# ACB_Jr.net
KiCad netlist of a schematic drawn in EAGLE
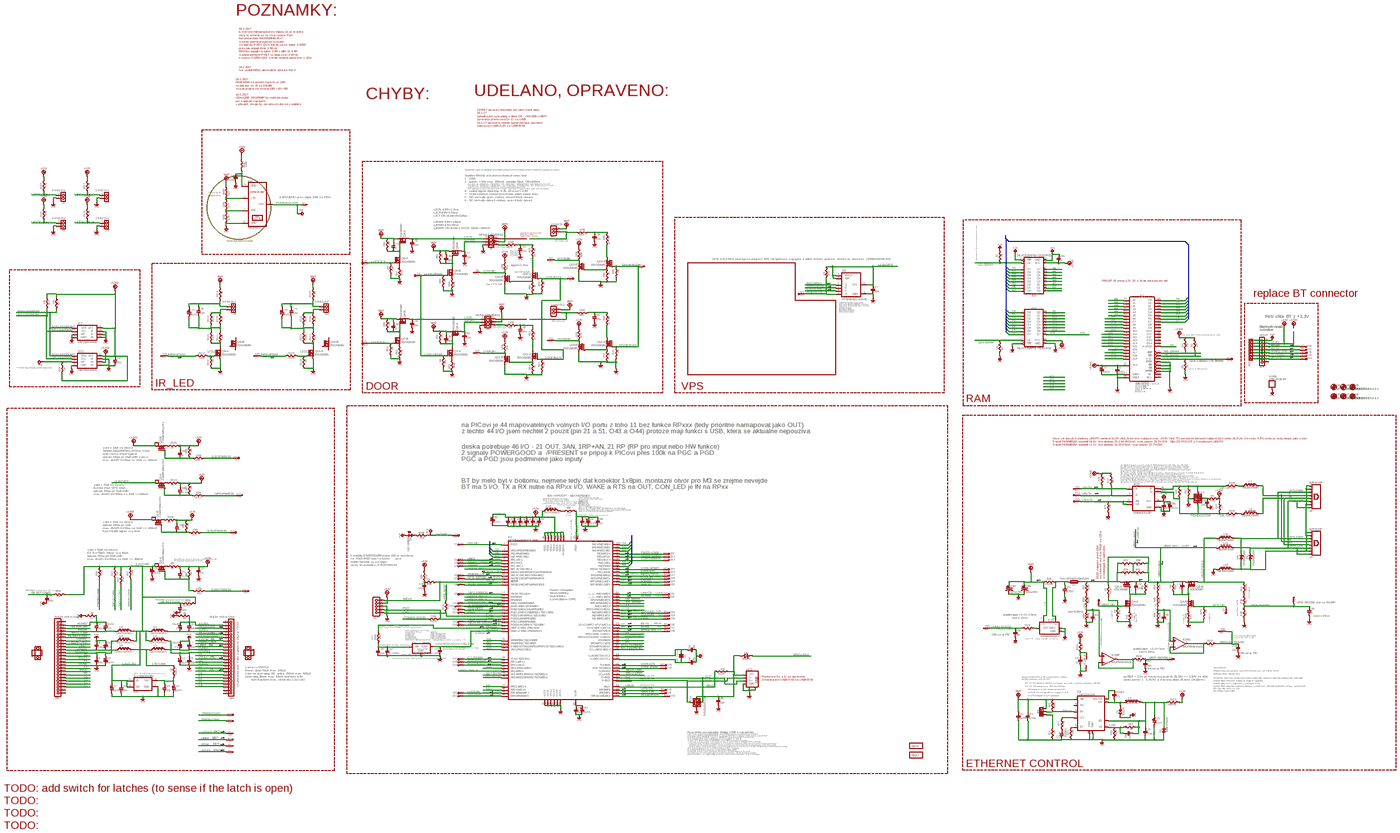
[diagram p0: schematic, sheet 1, overview]
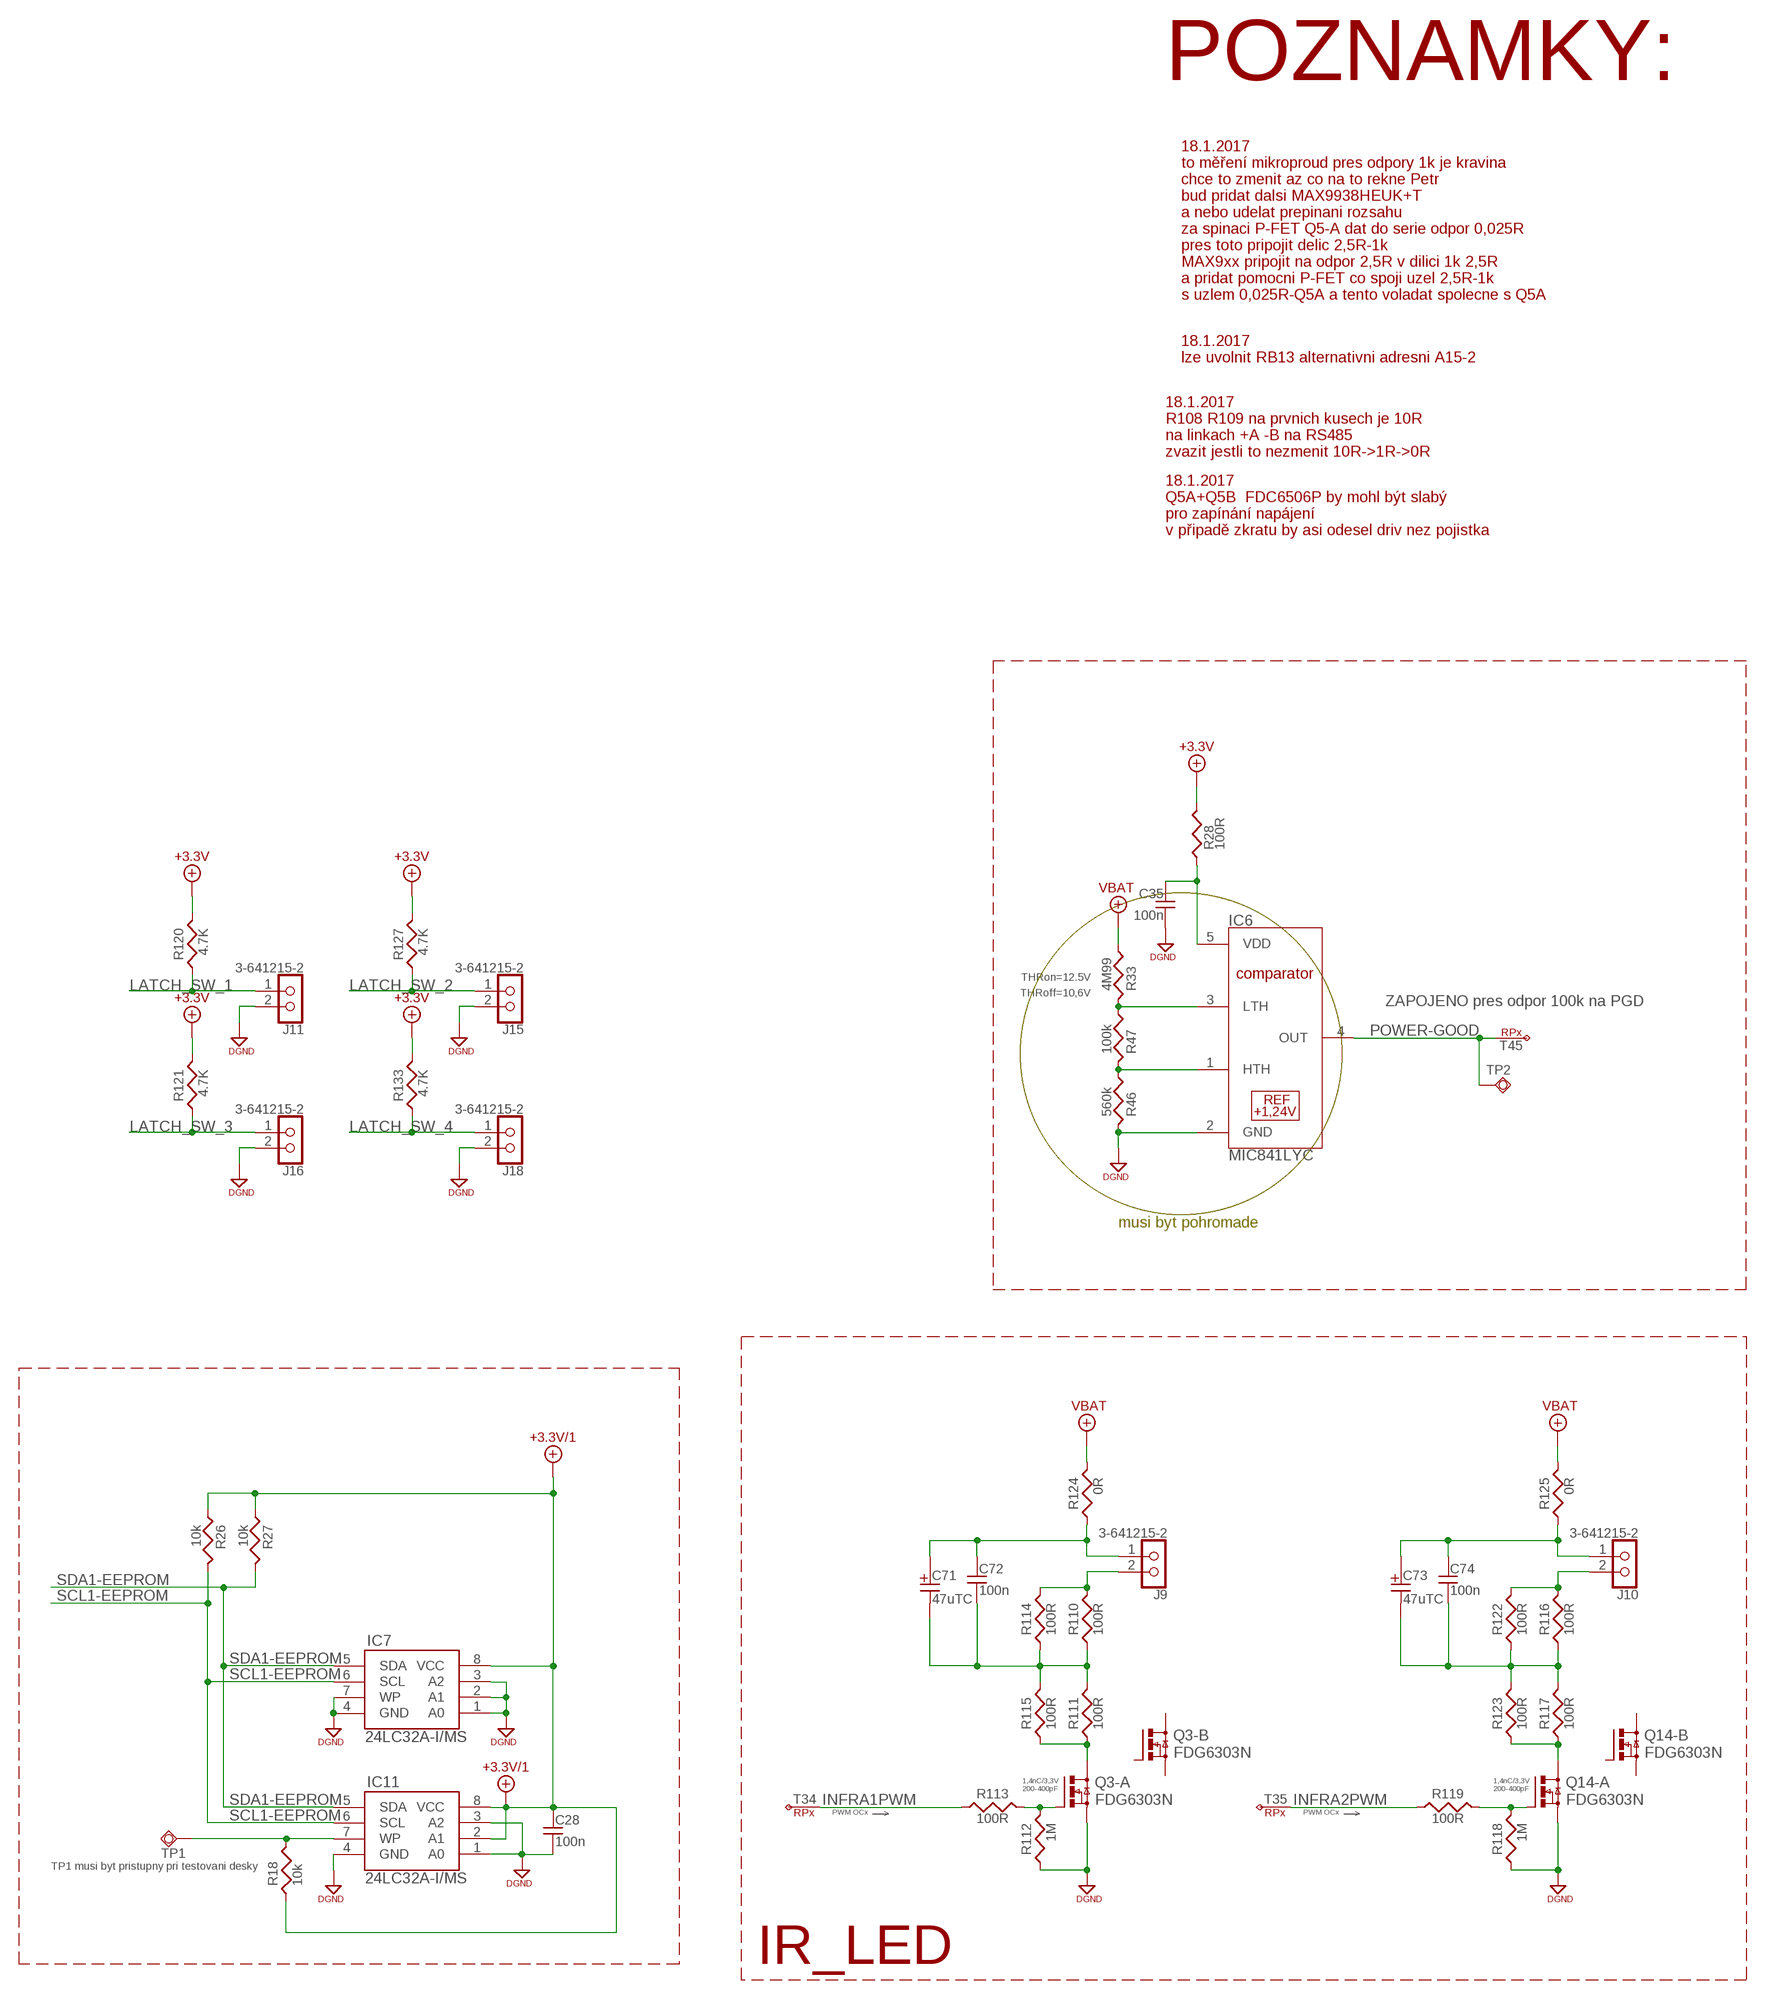
[diagram p1: schematic, sheet 1, part 1 of 5]
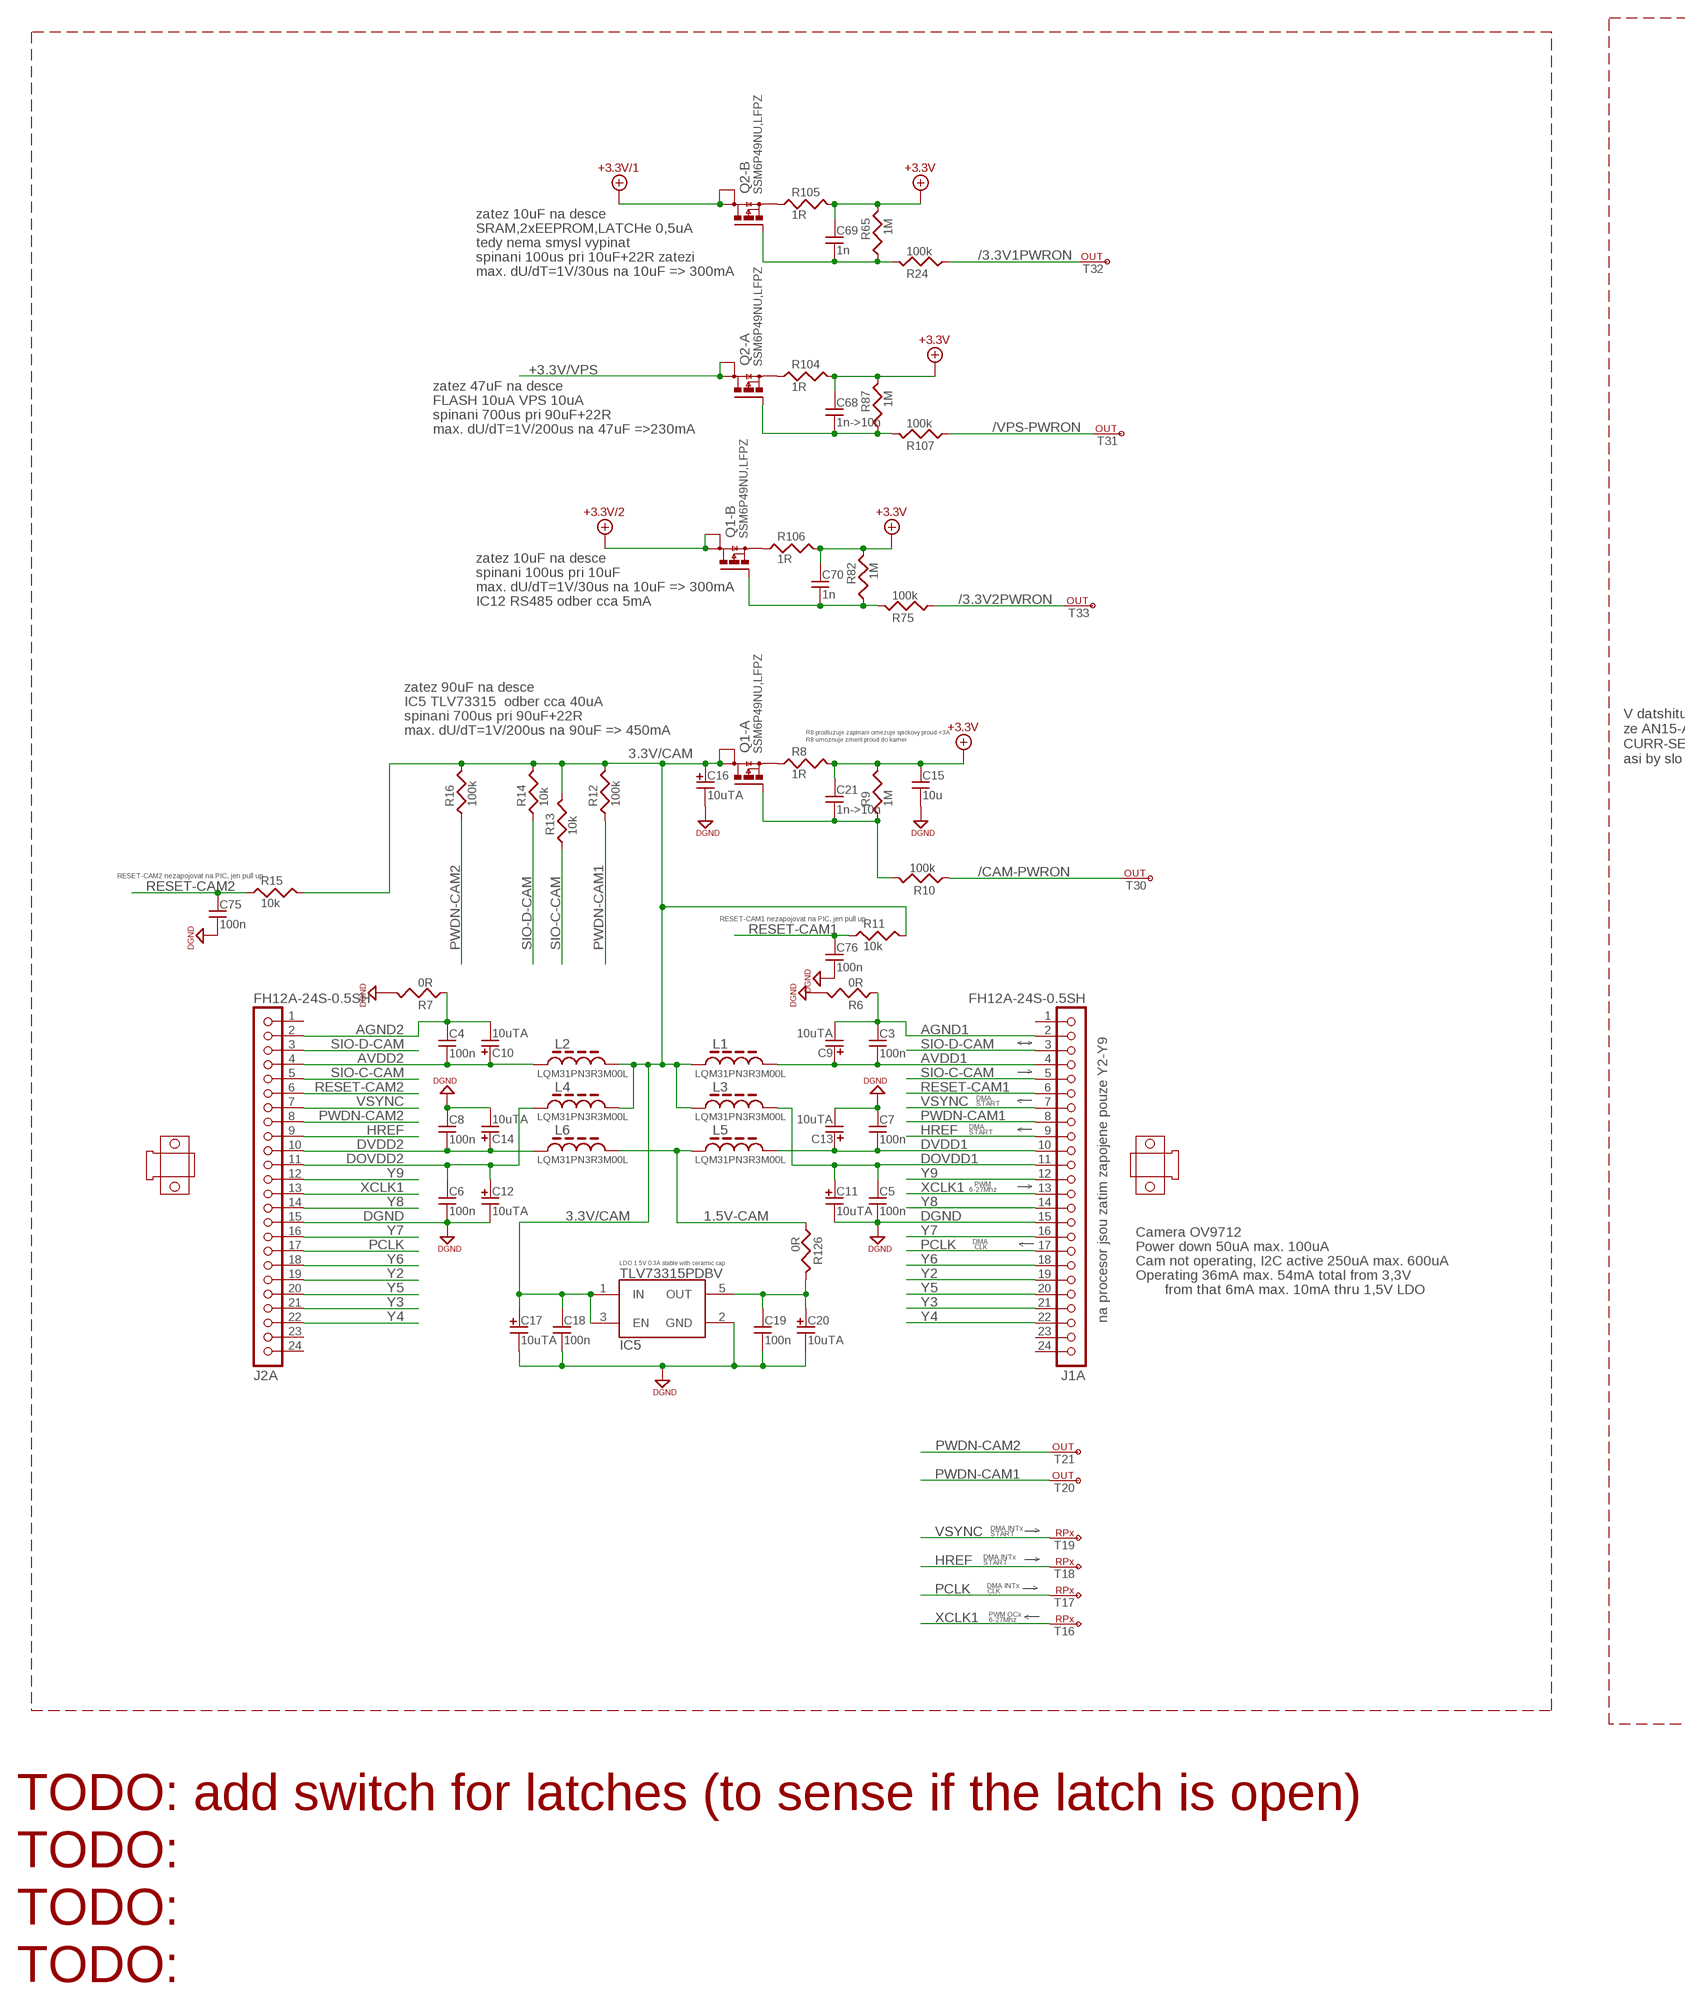
[diagram p2: schematic, sheet 1, part 2 of 5]
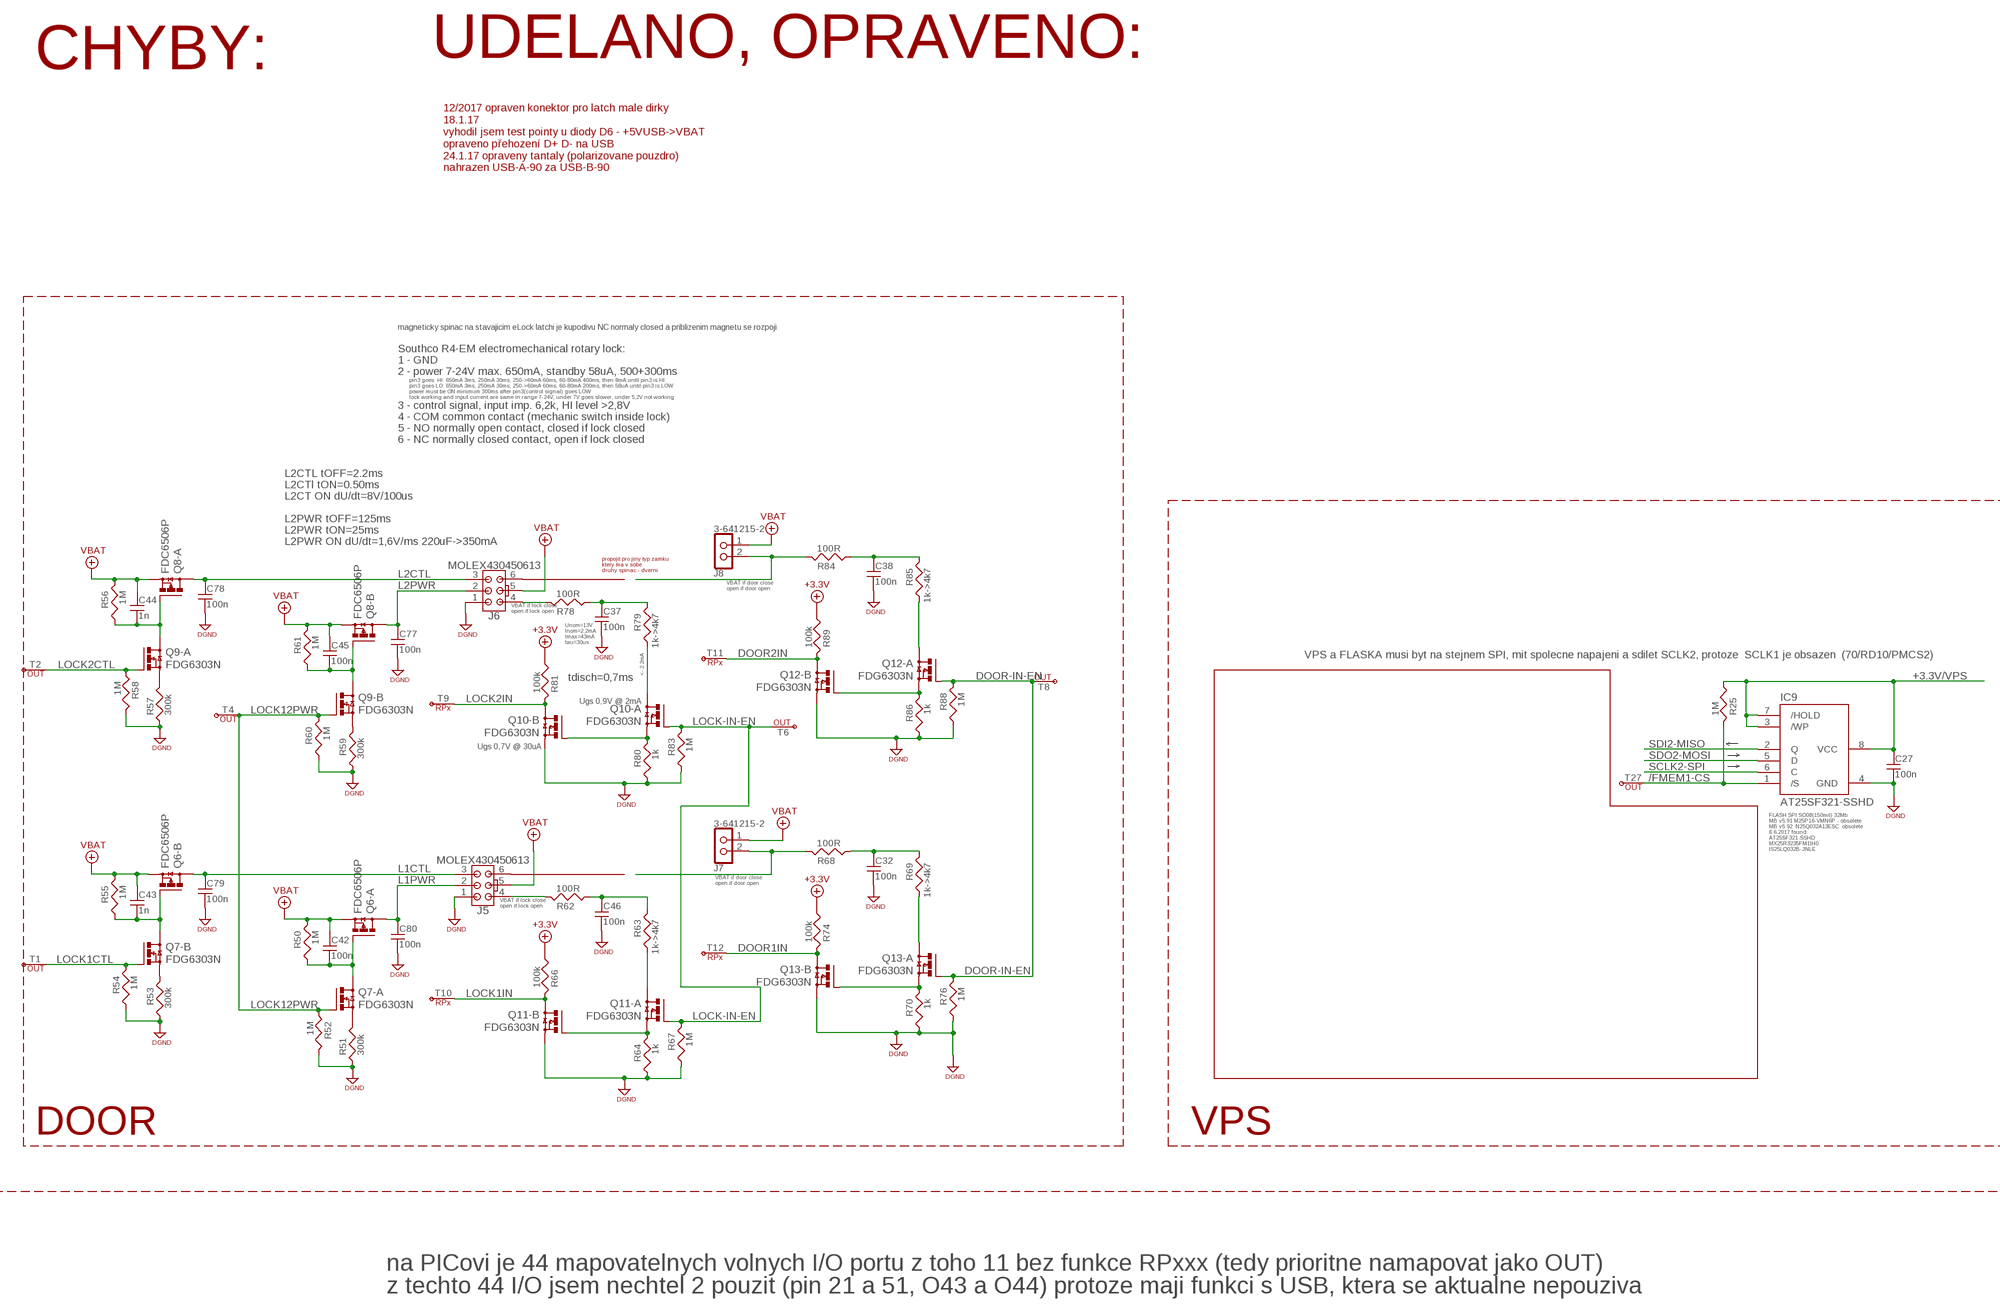
[diagram p3: schematic, sheet 1, part 3 of 5]
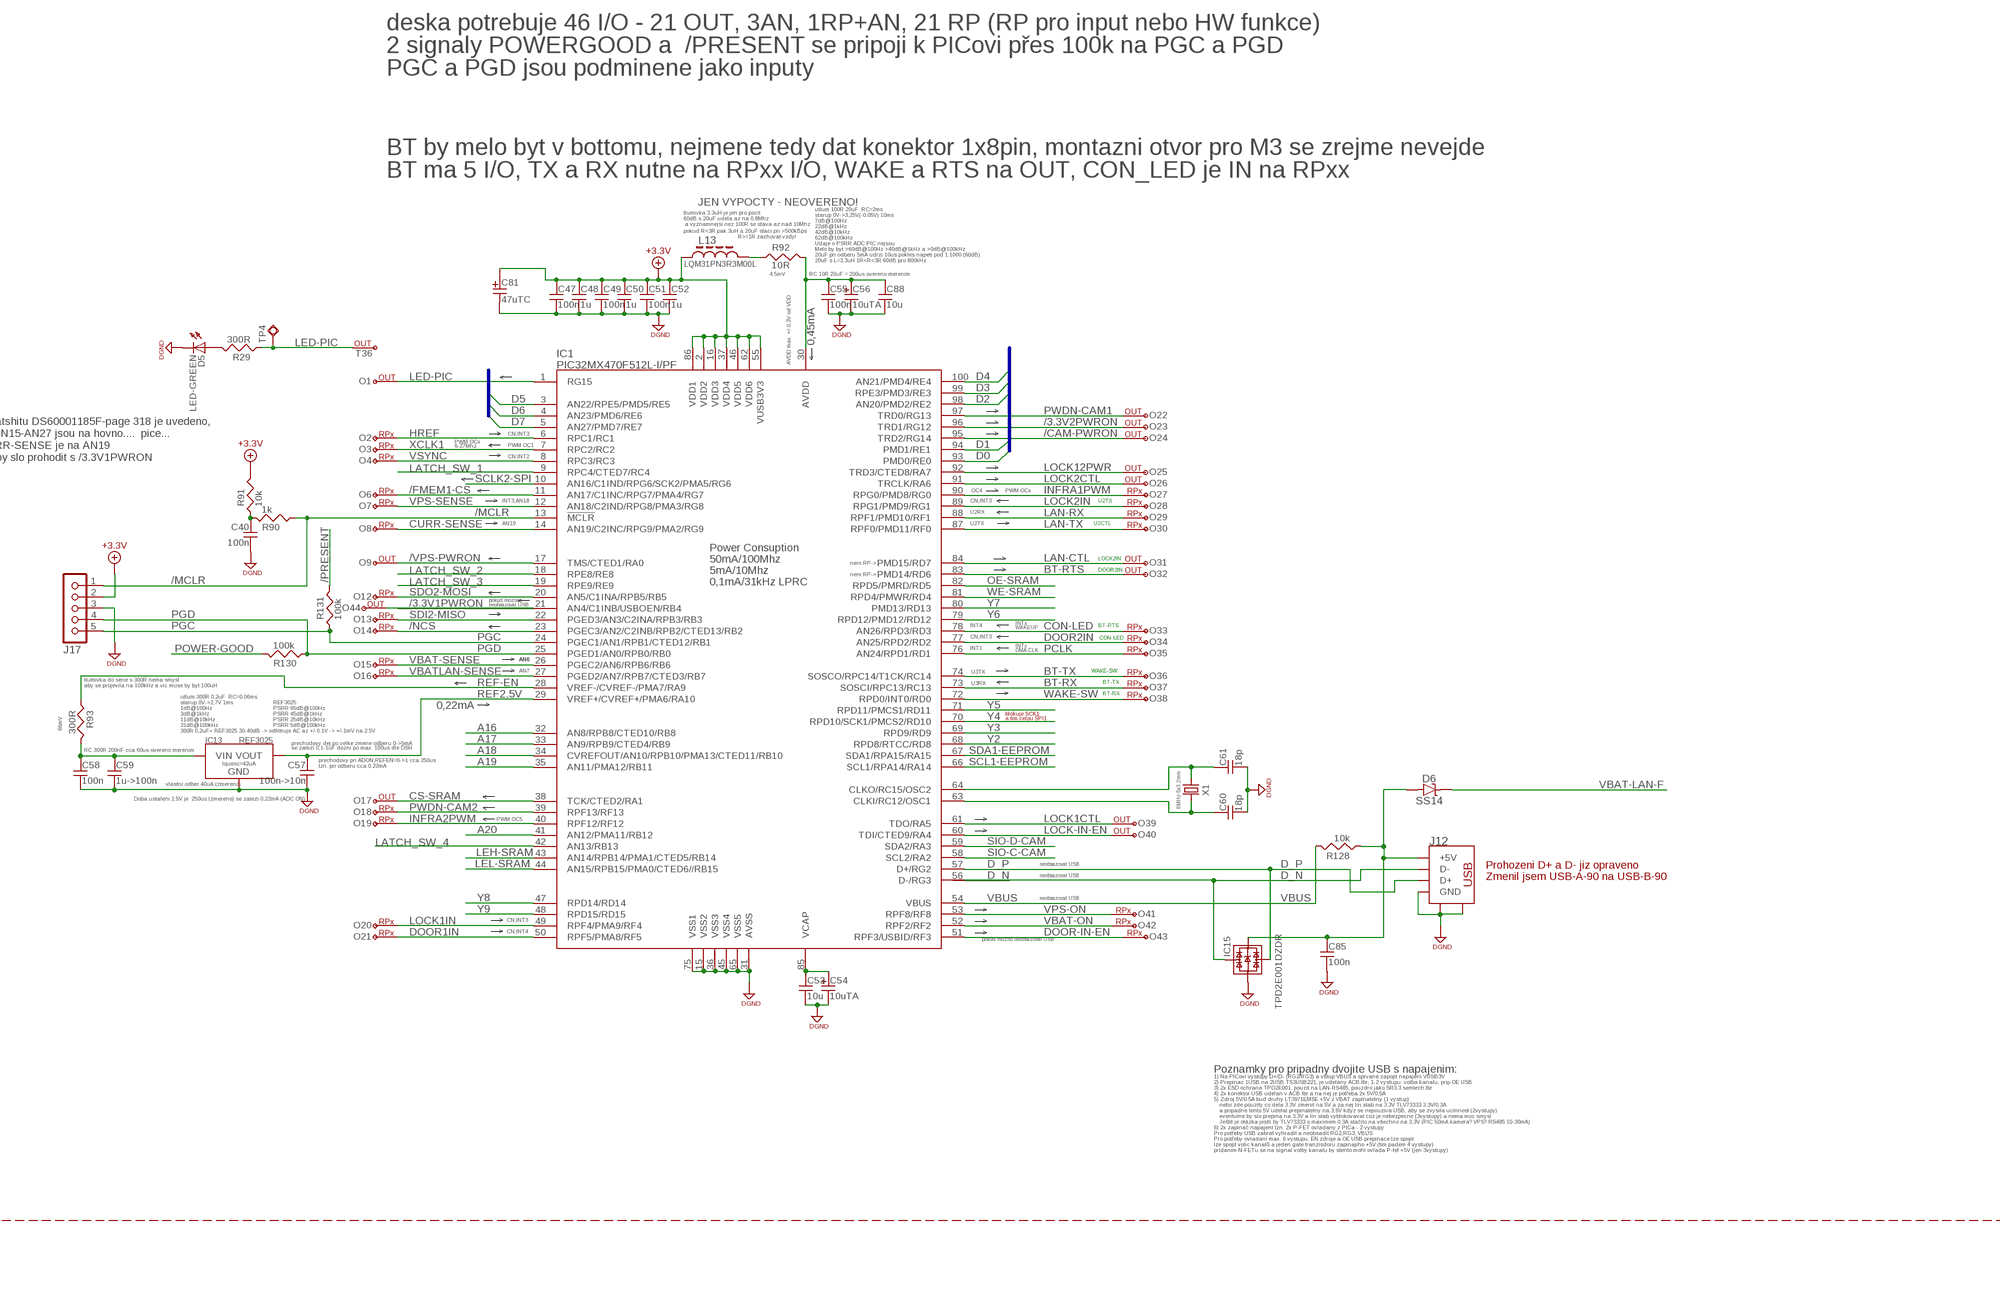
[diagram p4: schematic, sheet 1, part 4 of 5]
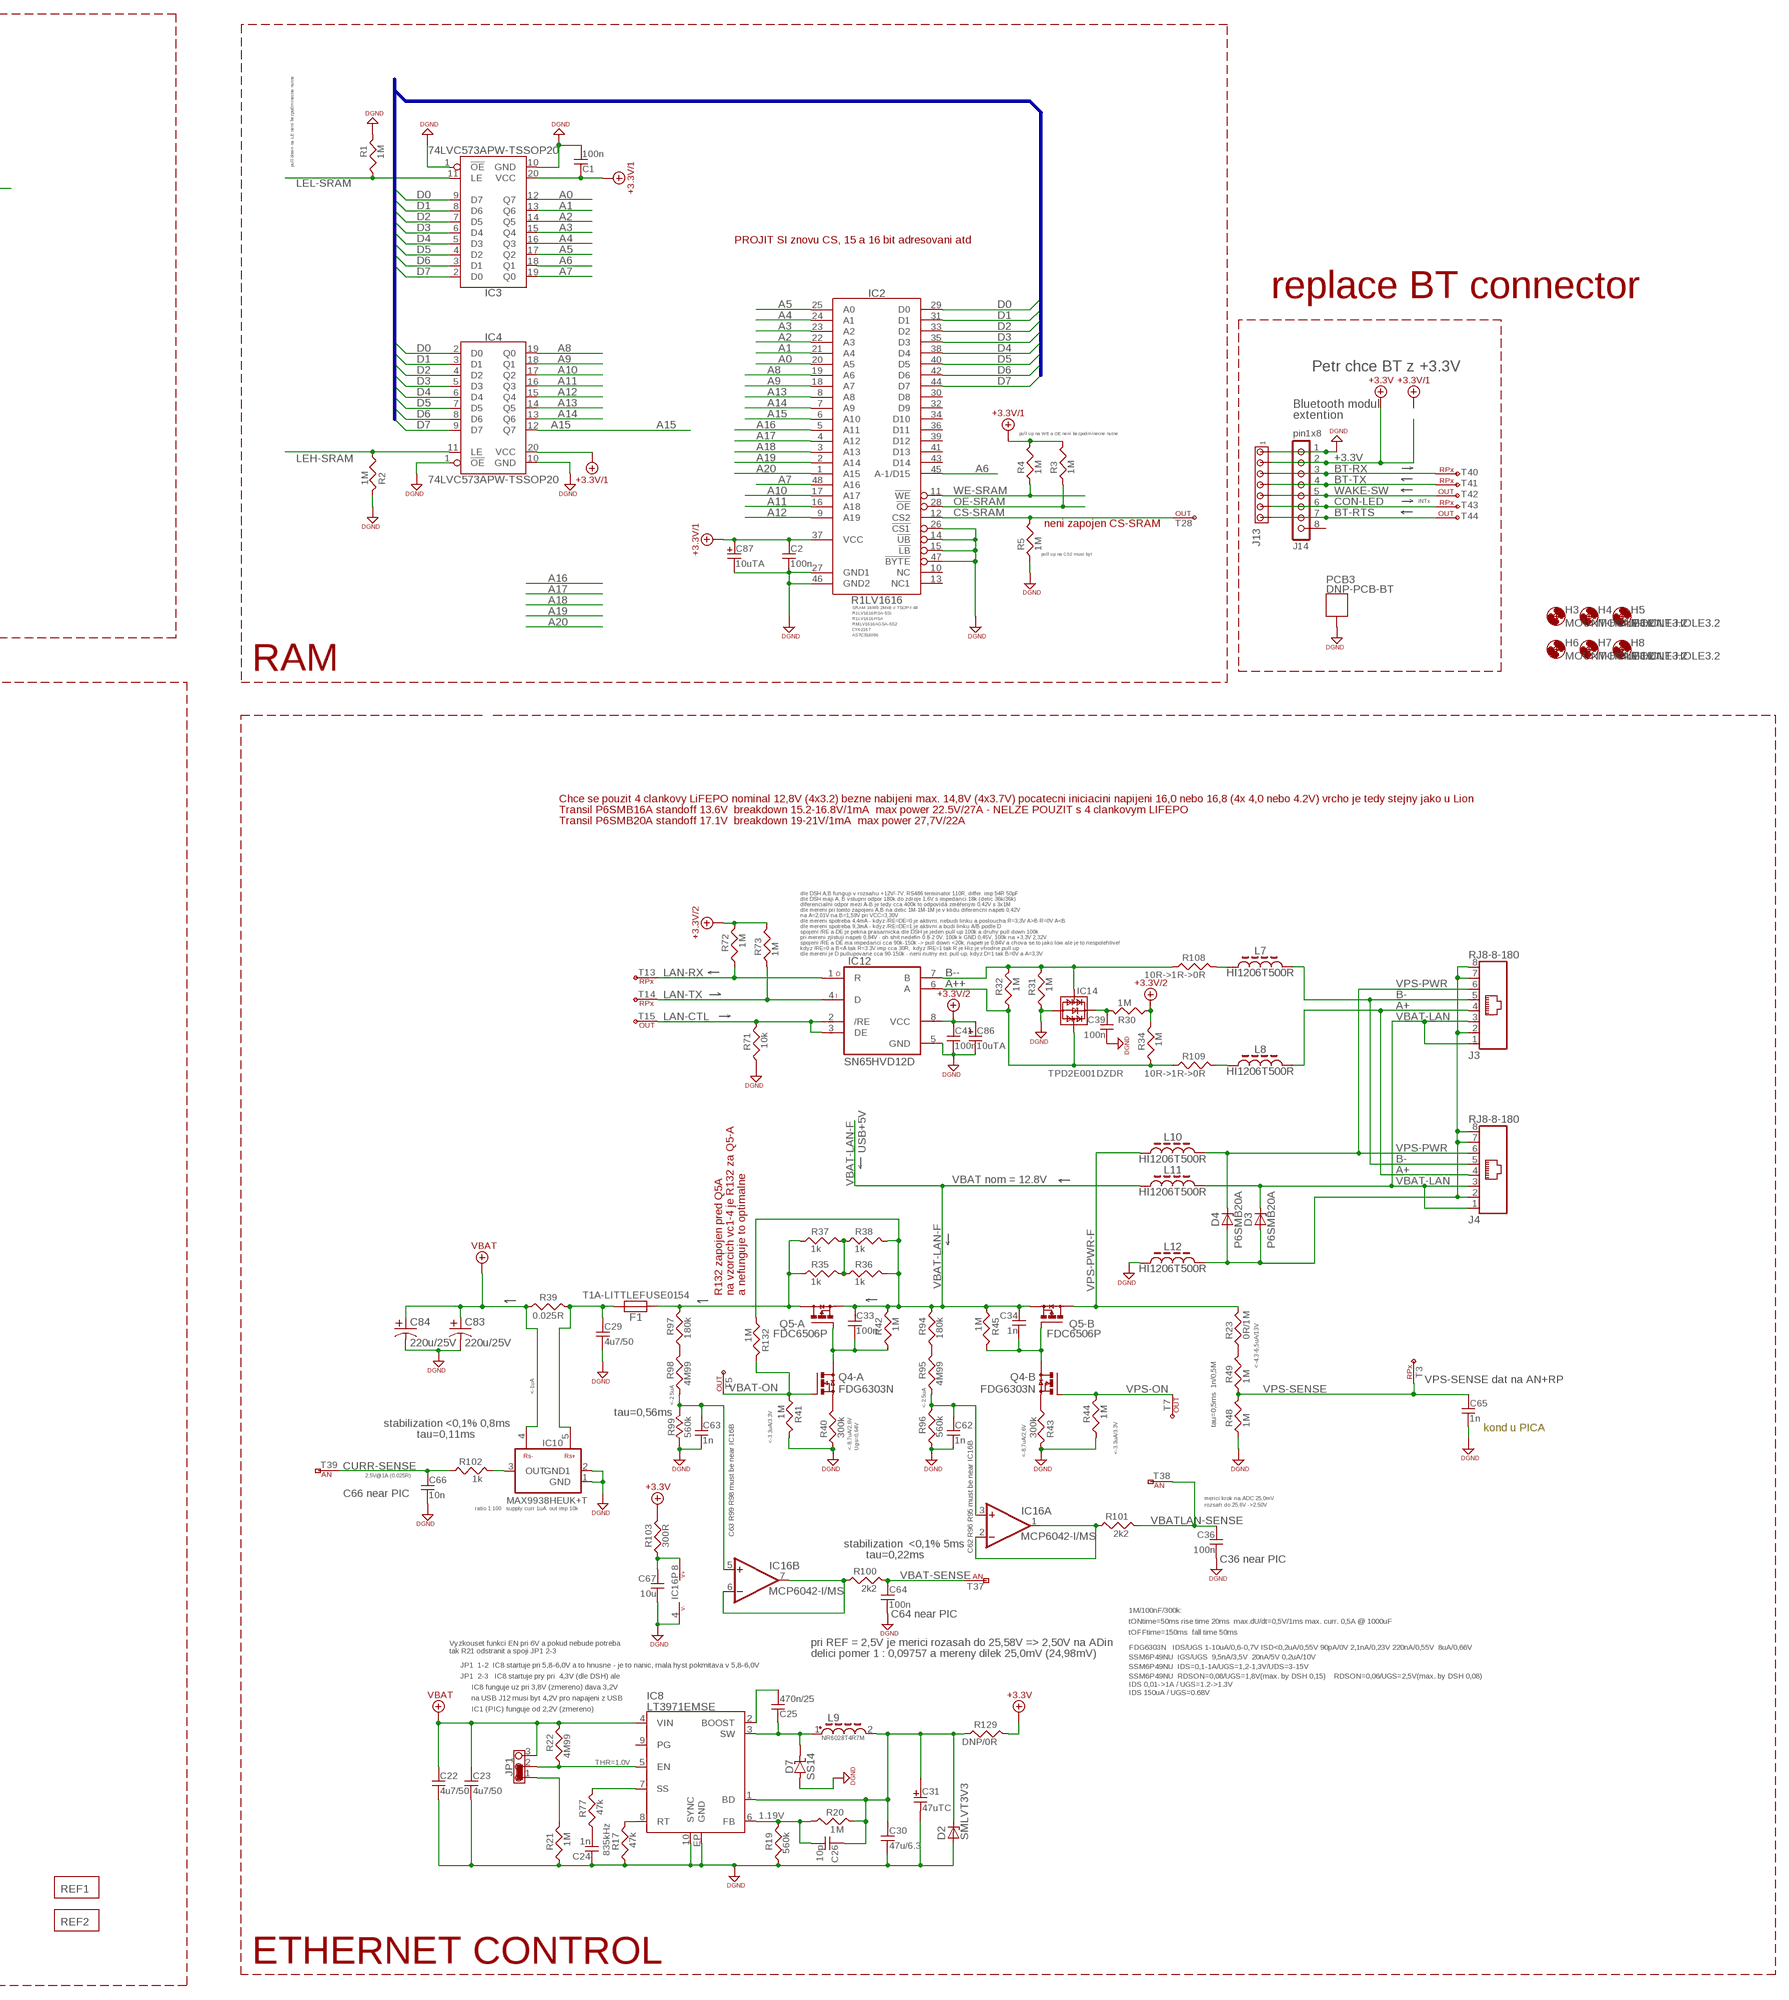
[diagram p5: schematic, sheet 1, part 5 of 5]

(export (version "E")
  (design (tool "Eeschema 10.0.6"))
  (components
    (comp (ref "C1")
      (value "100n")
      (footprint "eagle-import:0603")
      (libsource (lib "eagle-import") (part "C-0603"))
    )
    (comp (ref "C2")
      (value "100n")
      (footprint "eagle-import:0603")
      (libsource (lib "eagle-import") (part "DISCRETE_211_C-0603"))
    )
    (comp (ref "C3")
      (value "100n")
      (footprint "eagle-import:0603")
      (libsource (lib "eagle-import") (part "DISCRETE_211_C-0603"))
    )
    (comp (ref "C4")
      (value "100n")
      (footprint "eagle-import:0603")
      (libsource (lib "eagle-import") (part "DISCRETE_211_C-0603"))
    )
    (comp (ref "C5")
      (value "100n")
      (footprint "eagle-import:0603")
      (libsource (lib "eagle-import") (part "DISCRETE_211_C-0603"))
    )
    (comp (ref "C6")
      (value "100n")
      (footprint "eagle-import:0603")
      (libsource (lib "eagle-import") (part "DISCRETE_211_C-0603"))
    )
    (comp (ref "C7")
      (value "100n")
      (footprint "eagle-import:0603")
      (libsource (lib "eagle-import") (part "DISCRETE_211_C-0603"))
    )
    (comp (ref "C8")
      (value "100n")
      (footprint "eagle-import:0603")
      (libsource (lib "eagle-import") (part "DISCRETE_211_C-0603"))
    )
    (comp (ref "C9")
      (value "10uTA")
      (footprint "eagle-import:1206-POL-C")
      (libsource (lib "eagle-import") (part "CT-1206"))
    )
    (comp (ref "C10")
      (value "10uTA")
      (footprint "eagle-import:1206-POL-C")
      (libsource (lib "eagle-import") (part "CT-1206"))
    )
    (comp (ref "C11")
      (value "10uTA")
      (footprint "eagle-import:1206-POL-C")
      (libsource (lib "eagle-import") (part "CT-1206"))
    )
    (comp (ref "C12")
      (value "10uTA")
      (footprint "eagle-import:1206-POL-C")
      (libsource (lib "eagle-import") (part "CT-1206"))
    )
    (comp (ref "C13")
      (value "10uTA")
      (footprint "eagle-import:1206-POL-C")
      (libsource (lib "eagle-import") (part "CT-1206"))
    )
    (comp (ref "C14")
      (value "10uTA")
      (footprint "eagle-import:1206-POL-C")
      (libsource (lib "eagle-import") (part "CT-1206"))
    )
    (comp (ref "C15")
      (value "10u")
      (footprint "eagle-import:0603")
      (libsource (lib "eagle-import") (part "C-0603"))
    )
    (comp (ref "C16")
      (value "10uTA")
      (footprint "eagle-import:1206-POL-C")
      (libsource (lib "eagle-import") (part "CT-1206"))
    )
    (comp (ref "C17")
      (value "10uTA")
      (footprint "eagle-import:1206-POL-C")
      (libsource (lib "eagle-import") (part "CT-1206"))
    )
    (comp (ref "C18")
      (value "100n")
      (footprint "eagle-import:0603")
      (libsource (lib "eagle-import") (part "DISCRETE_211_C-0603"))
    )
    (comp (ref "C19")
      (value "100n")
      (footprint "eagle-import:0603")
      (libsource (lib "eagle-import") (part "DISCRETE_211_C-0603"))
    )
    (comp (ref "C20")
      (value "10uTA")
      (footprint "eagle-import:1206-POL-C")
      (libsource (lib "eagle-import") (part "CT-1206"))
    )
    (comp (ref "C21")
      (value "1n->10n")
      (footprint "eagle-import:0603")
      (libsource (lib "eagle-import") (part "DISCRETE_211_C-0603"))
    )
    (comp (ref "C22")
      (value "4u7/50")
      (footprint "eagle-import:1206")
      (libsource (lib "eagle-import") (part "C-1206"))
    )
    (comp (ref "C23")
      (value "4u7/50")
      (footprint "eagle-import:1206")
      (libsource (lib "eagle-import") (part "C-1206"))
    )
    (comp (ref "C24")
      (value "1n")
      (footprint "eagle-import:0603")
      (libsource (lib "eagle-import") (part "DISCRETE_211_C-0603"))
    )
    (comp (ref "C25")
      (value "470n/25")
      (footprint "eagle-import:0603")
      (libsource (lib "eagle-import") (part "DISCRETE_211_C-0603"))
    )
    (comp (ref "C26")
      (value "10p")
      (footprint "eagle-import:0603")
      (libsource (lib "eagle-import") (part "DISCRETE_211_C-0603"))
    )
    (comp (ref "C27")
      (value "100n")
      (footprint "eagle-import:0603")
      (libsource (lib "eagle-import") (part "DISCRETE_211_C-0603"))
    )
    (comp (ref "C28")
      (value "100n")
      (footprint "eagle-import:0603")
      (libsource (lib "eagle-import") (part "DISCRETE_211_C-0603"))
    )
    (comp (ref "C29")
      (value "4u7/50")
      (footprint "eagle-import:1206")
      (libsource (lib "eagle-import") (part "C-1206"))
    )
    (comp (ref "C30")
      (value "47u/6.3")
      (footprint "eagle-import:1206")
      (libsource (lib "eagle-import") (part "C-1206"))
    )
    (comp (ref "C31")
      (value "47uTC")
      (footprint "eagle-import:CT-C")
      (libsource (lib "eagle-import") (part "CT-C"))
    )
    (comp (ref "C32")
      (value "100n")
      (footprint "eagle-import:0603")
      (libsource (lib "eagle-import") (part "DISCRETE_211_C-0603"))
    )
    (comp (ref "C33")
      (value "100n")
      (footprint "eagle-import:0603")
      (libsource (lib "eagle-import") (part "DISCRETE_211_C-0603"))
    )
    (comp (ref "C34")
      (value "1n")
      (footprint "eagle-import:0603")
      (libsource (lib "eagle-import") (part "DISCRETE_211_C-0603"))
    )
    (comp (ref "C35")
      (value "100n")
      (footprint "eagle-import:0603")
      (libsource (lib "eagle-import") (part "DISCRETE_211_C-0603"))
    )
    (comp (ref "C36")
      (value "100n")
      (footprint "eagle-import:0603")
      (libsource (lib "eagle-import") (part "DISCRETE_211_C-0603"))
    )
    (comp (ref "C37")
      (value "100n")
      (footprint "eagle-import:0603")
      (libsource (lib "eagle-import") (part "DISCRETE_211_C-0603"))
    )
    (comp (ref "C38")
      (value "100n")
      (footprint "eagle-import:0603")
      (libsource (lib "eagle-import") (part "DISCRETE_211_C-0603"))
    )
    (comp (ref "C39")
      (value "100n")
      (footprint "eagle-import:0603")
      (libsource (lib "eagle-import") (part "DISCRETE_211_C-0603"))
    )
    (comp (ref "C40")
      (value "100n")
      (footprint "eagle-import:0603")
      (libsource (lib "eagle-import") (part "DISCRETE_211_C-0603"))
    )
    (comp (ref "C41")
      (value "100n")
      (footprint "eagle-import:0603")
      (libsource (lib "eagle-import") (part "DISCRETE_211_C-0603"))
    )
    (comp (ref "C42")
      (value "100n")
      (footprint "eagle-import:0603")
      (libsource (lib "eagle-import") (part "DISCRETE_211_C-0603"))
    )
    (comp (ref "C43")
      (value "1n")
      (footprint "eagle-import:0603")
      (libsource (lib "eagle-import") (part "DISCRETE_211_C-0603"))
    )
    (comp (ref "C44")
      (value "1n")
      (footprint "eagle-import:0603")
      (libsource (lib "eagle-import") (part "DISCRETE_211_C-0603"))
    )
    (comp (ref "C45")
      (value "100n")
      (footprint "eagle-import:0603")
      (libsource (lib "eagle-import") (part "DISCRETE_211_C-0603"))
    )
    (comp (ref "C46")
      (value "100n")
      (footprint "eagle-import:0603")
      (libsource (lib "eagle-import") (part "DISCRETE_211_C-0603"))
    )
    (comp (ref "C47")
      (value "100n")
      (footprint "eagle-import:0603")
      (libsource (lib "eagle-import") (part "DISCRETE_211_C-0603"))
    )
    (comp (ref "C48")
      (value "1u")
      (footprint "eagle-import:0603")
      (libsource (lib "eagle-import") (part "DISCRETE_211_C-0603"))
    )
    (comp (ref "C49")
      (value "100n")
      (footprint "eagle-import:0603")
      (libsource (lib "eagle-import") (part "DISCRETE_211_C-0603"))
    )
    (comp (ref "C50")
      (value "1u")
      (footprint "eagle-import:0603")
      (libsource (lib "eagle-import") (part "DISCRETE_211_C-0603"))
    )
    (comp (ref "C51")
      (value "100n")
      (footprint "eagle-import:0603")
      (libsource (lib "eagle-import") (part "DISCRETE_211_C-0603"))
    )
    (comp (ref "C52")
      (value "1u")
      (footprint "eagle-import:0603")
      (libsource (lib "eagle-import") (part "DISCRETE_211_C-0603"))
    )
    (comp (ref "C53")
      (value "10u")
      (footprint "eagle-import:0603")
      (libsource (lib "eagle-import") (part "DISCRETE_211_C-0603"))
    )
    (comp (ref "C54")
      (value "10uTA")
      (footprint "eagle-import:1206-POL-C")
      (libsource (lib "eagle-import") (part "CT-1206"))
    )
    (comp (ref "C55")
      (value "100n")
      (footprint "eagle-import:0603")
      (libsource (lib "eagle-import") (part "DISCRETE_211_C-0603"))
    )
    (comp (ref "C56")
      (value "10uTA")
      (footprint "eagle-import:1206-POL-C")
      (libsource (lib "eagle-import") (part "CT-1206"))
    )
    (comp (ref "C57")
      (value "100n->10n")
      (footprint "eagle-import:0603")
      (libsource (lib "eagle-import") (part "DISCRETE_211_C-0603"))
    )
    (comp (ref "C58")
      (value "100n")
      (footprint "eagle-import:0603")
      (libsource (lib "eagle-import") (part "DISCRETE_211_C-0603"))
    )
    (comp (ref "C59")
      (value "1u->100n")
      (footprint "eagle-import:0603")
      (libsource (lib "eagle-import") (part "DISCRETE_211_C-0603"))
    )
    (comp (ref "C60")
      (value "18p")
      (footprint "eagle-import:0603")
      (libsource (lib "eagle-import") (part "DISCRETE_211_C-0603"))
    )
    (comp (ref "C61")
      (value "18p")
      (footprint "eagle-import:0603")
      (libsource (lib "eagle-import") (part "DISCRETE_211_C-0603"))
    )
    (comp (ref "C62")
      (value "1n")
      (footprint "eagle-import:0603")
      (libsource (lib "eagle-import") (part "DISCRETE_211_C-0603"))
    )
    (comp (ref "C63")
      (value "1n")
      (footprint "eagle-import:0603")
      (libsource (lib "eagle-import") (part "DISCRETE_211_C-0603"))
    )
    (comp (ref "C64")
      (value "100n")
      (footprint "eagle-import:0603")
      (libsource (lib "eagle-import") (part "DISCRETE_211_C-0603"))
    )
    (comp (ref "C65")
      (value "1n")
      (footprint "eagle-import:0603")
      (libsource (lib "eagle-import") (part "DISCRETE_211_C-0603"))
    )
    (comp (ref "C66")
      (value "10n")
      (footprint "eagle-import:0603")
      (libsource (lib "eagle-import") (part "DISCRETE_211_C-0603"))
    )
    (comp (ref "C67")
      (value "10u")
      (footprint "eagle-import:0603")
      (libsource (lib "eagle-import") (part "DISCRETE_211_C-0603"))
    )
    (comp (ref "C68")
      (value "1n->10n")
      (footprint "eagle-import:0603")
      (libsource (lib "eagle-import") (part "DISCRETE_211_C-0603"))
    )
    (comp (ref "C69")
      (value "1n")
      (footprint "eagle-import:0603")
      (libsource (lib "eagle-import") (part "DISCRETE_211_C-0603"))
    )
    (comp (ref "C70")
      (value "1n")
      (footprint "eagle-import:0603")
      (libsource (lib "eagle-import") (part "DISCRETE_211_C-0603"))
    )
    (comp (ref "C71")
      (value "47uTC")
      (footprint "eagle-import:CT-C")
      (libsource (lib "eagle-import") (part "CT-C"))
    )
    (comp (ref "C72")
      (value "100n")
      (footprint "eagle-import:0603")
      (libsource (lib "eagle-import") (part "DISCRETE_211_C-0603"))
    )
    (comp (ref "C73")
      (value "47uTC")
      (footprint "eagle-import:CT-C")
      (libsource (lib "eagle-import") (part "CT-C"))
    )
    (comp (ref "C74")
      (value "100n")
      (footprint "eagle-import:0603")
      (libsource (lib "eagle-import") (part "DISCRETE_211_C-0603"))
    )
    (comp (ref "C75")
      (value "100n")
      (footprint "eagle-import:0603")
      (libsource (lib "eagle-import") (part "DISCRETE_211_C-0603"))
    )
    (comp (ref "C76")
      (value "100n")
      (footprint "eagle-import:0603")
      (libsource (lib "eagle-import") (part "DISCRETE_211_C-0603"))
    )
    (comp (ref "C77")
      (value "100n")
      (footprint "eagle-import:0603")
      (libsource (lib "eagle-import") (part "DISCRETE_211_C-0603"))
    )
    (comp (ref "C78")
      (value "100n")
      (footprint "eagle-import:0603")
      (libsource (lib "eagle-import") (part "DISCRETE_211_C-0603"))
    )
    (comp (ref "C79")
      (value "100n")
      (footprint "eagle-import:0603")
      (libsource (lib "eagle-import") (part "DISCRETE_211_C-0603"))
    )
    (comp (ref "C80")
      (value "100n")
      (footprint "eagle-import:0603")
      (libsource (lib "eagle-import") (part "DISCRETE_211_C-0603"))
    )
    (comp (ref "C81")
      (value "47uTC")
      (footprint "eagle-import:CT-C")
      (libsource (lib "eagle-import") (part "CT-C"))
    )
    (comp (ref "C83")
      (value "220u/25V")
      (footprint "eagle-import:CAP_8MM_DIA_SMT")
      (libsource (lib "eagle-import") (part "CAP-ELEC-SMD-8MM"))
    )
    (comp (ref "C84")
      (value "220u/25V")
      (footprint "eagle-import:CAP_8MM_DIA_SMT")
      (libsource (lib "eagle-import") (part "CAP-ELEC-SMD-8MM"))
    )
    (comp (ref "C85")
      (value "100n")
      (footprint "eagle-import:0603")
      (libsource (lib "eagle-import") (part "DISCRETE_211_C-0603"))
    )
    (comp (ref "C86")
      (value "10uTA")
      (footprint "eagle-import:1206-POL-C")
      (libsource (lib "eagle-import") (part "CT-1206"))
    )
    (comp (ref "C87")
      (value "10uTA")
      (footprint "eagle-import:1206-POL-C")
      (libsource (lib "eagle-import") (part "CT-1206"))
    )
    (comp (ref "C88")
      (value "10u")
      (footprint "eagle-import:0603")
      (libsource (lib "eagle-import") (part "DISCRETE_211_C-0603"))
    )
    (comp (ref "D2")
      (value "SMLVT3V3")
      (footprint "eagle-import:SMA")
      (libsource (lib "eagle-import") (part "SMLVT3V3"))
    )
    (comp (ref "D3")
      (value "P6SMB20A")
      (footprint "eagle-import:SMB")
      (libsource (lib "eagle-import") (part "P6SMB"))
    )
    (comp (ref "D4")
      (value "P6SMB20A")
      (footprint "eagle-import:SMB")
      (libsource (lib "eagle-import") (part "P6SMB"))
    )
    (comp (ref "D5")
      (value "LED-GREEN")
      (footprint "eagle-import:0805-POL-D")
      (libsource (lib "eagle-import") (part "LED-0805"))
    )
    (comp (ref "D6")
      (value "SS14")
      (footprint "eagle-import:SMA")
      (libsource (lib "eagle-import") (part "DS-SMA"))
    )
    (comp (ref "D7")
      (value "SS14")
      (footprint "eagle-import:SMA")
      (libsource (lib "eagle-import") (part "DS-SMA"))
    )
    (comp (ref "F1")
      (value "T1A-LITTLEFUSE0154")
      (footprint "eagle-import:LITTLEFUSE0154")
      (libsource (lib "eagle-import") (part "POJISTKA-LITTLEFUSE0154"))
    )
    (comp (ref "H1")
      (value "CAM-HOLDER")
      (footprint "eagle-import:CAM-HOLDER")
      (libsource (lib "eagle-import") (part "CAM-HOLDER"))
    )
    (comp (ref "H2")
      (value "CAM-HOLDER")
      (footprint "eagle-import:CAM-HOLDER")
      (libsource (lib "eagle-import") (part "CAM-HOLDER"))
    )
    (comp (ref "H3")
      (value "MOUNT-HOLE3.2")
      (footprint "eagle-import:3,2")
      (libsource (lib "eagle-import") (part "MOUNT-HOLE3.2"))
    )
    (comp (ref "H4")
      (value "MOUNT-HOLE3.2")
      (footprint "eagle-import:3,2")
      (libsource (lib "eagle-import") (part "MOUNT-HOLE3.2"))
    )
    (comp (ref "H5")
      (value "MOUNT-HOLE3.2")
      (footprint "eagle-import:3,2")
      (libsource (lib "eagle-import") (part "MOUNT-HOLE3.2"))
    )
    (comp (ref "H6")
      (value "MOUNT-HOLE3.2")
      (footprint "eagle-import:3,2")
      (libsource (lib "eagle-import") (part "MOUNT-HOLE3.2"))
    )
    (comp (ref "H7")
      (value "MOUNT-HOLE3.2")
      (footprint "eagle-import:3,2")
      (libsource (lib "eagle-import") (part "MOUNT-HOLE3.2"))
    )
    (comp (ref "H8")
      (value "MOUNT-HOLE3.2")
      (footprint "eagle-import:3,2")
      (libsource (lib "eagle-import") (part "MOUNT-HOLE3.2"))
    )
    (comp (ref "IC1")
      (value "PIC32MX470F512L-I/PF")
      (footprint "eagle-import:TQFP100_14X14_0,5MM")
      (libsource (lib "eagle-import") (part "PIC32MX470F512L-I/PF"))
    )
    (comp (ref "IC2")
      (value "R1LV1616")
      (footprint "eagle-import:48-TSOP-I")
      (libsource (lib "eagle-import") (part "R1LV1616HSA"))
    )
    (comp (ref "IC3")
      (value "74LVC573APW-TSSOP20")
      (footprint "eagle-import:TSSOP20")
      (libsource (lib "eagle-import") (part "74LVC573APW-TSSOP20"))
    )
    (comp (ref "IC4")
      (value "74LVC573APW-TSSOP20")
      (footprint "eagle-import:TSSOP20")
      (libsource (lib "eagle-import") (part "74LVC573APW-TSSOP20"))
    )
    (comp (ref "IC5")
      (value "TLV73315PDBV")
      (footprint "eagle-import:SOT23-5")
      (libsource (lib "eagle-import") (part "TLV73315PDBV"))
    )
    (comp (ref "IC6")
      (value "MIC841LYC")
      (footprint "eagle-import:SC-70-5")
      (libsource (lib "eagle-import") (part "MIC841LYC"))
    )
    (comp (ref "IC7")
      (value "24LC32A-I/MS")
      (footprint "eagle-import:MSOP-08")
      (libsource (lib "eagle-import") (part "24-I/MS"))
    )
    (comp (ref "IC8")
      (value "LT3971EMSE")
      (footprint "eagle-import:MSOP10EXP")
      (libsource (lib "eagle-import") (part "LT3971EMSE"))
    )
    (comp (ref "IC9")
      (value "AT25SF321-SSHD")
      (footprint "eagle-import:SO-08")
      (libsource (lib "eagle-import") (part "M25P16-VMN6P"))
    )
    (comp (ref "IC10")
      (value "MAX9938HEUK+T")
      (footprint "eagle-import:SOT23-5")
      (libsource (lib "eagle-import") (part "TSM9938HEUK+T"))
    )
    (comp (ref "IC11")
      (value "24LC32A-I/MS")
      (footprint "eagle-import:MSOP-08")
      (libsource (lib "eagle-import") (part "24-I/MS"))
    )
    (comp (ref "IC12")
      (value "SN65HVD12D")
      (footprint "eagle-import:SO08")
      (libsource (lib "eagle-import") (part "SN65HVD3082ED"))
    )
    (comp (ref "IC13")
      (value "REF3025")
      (footprint "eagle-import:SOT23")
      (libsource (lib "eagle-import") (part "REF3025"))
    )
    (comp (ref "IC14")
      (value "TPD2E001DZDR")
      (footprint "eagle-import:SOT-143")
      (libsource (lib "eagle-import") (part "SR05.TCT"))
    )
    (comp (ref "IC15")
      (value "TPD2E001DZDR")
      (footprint "eagle-import:SOT-143")
      (libsource (lib "eagle-import") (part "SR05.TCT"))
    )
    (comp (ref "IC16")
      (value "MCP6042-I/MS")
      (footprint "eagle-import:MSOP-08")
      (libsource (lib "eagle-import") (part "MCP6042-I/MS"))
    )
    (comp (ref "J1")
      (value "FH12A-24S-0.5SH")
      (footprint "eagle-import:FH12A-24S-05SH")
      (libsource (lib "eagle-import") (part "FH12A-24S-0.5SH"))
    )
    (comp (ref "J2")
      (value "FH12A-24S-0.5SH")
      (footprint "eagle-import:FH12A-24S-05SH")
      (libsource (lib "eagle-import") (part "FH12A-24S-0.5SH"))
    )
    (comp (ref "J3")
      (value "RJ8-8-180")
      (footprint "eagle-import:RJ8-8-180")
      (libsource (lib "eagle-import") (part "RJ8-8-180"))
    )
    (comp (ref "J4")
      (value "RJ8-8-180")
      (footprint "eagle-import:RJ8-8-180")
      (libsource (lib "eagle-import") (part "RJ8-8-180"))
    )
    (comp (ref "J5")
      (value "MOLEX430450613")
      (footprint "eagle-import:MOLEX430450613")
      (libsource (lib "eagle-import") (part "MOLEX430450613"))
    )
    (comp (ref "J6")
      (value "MOLEX430450613")
      (footprint "eagle-import:MOLEX430450613")
      (libsource (lib "eagle-import") (part "MOLEX430450613"))
    )
    (comp (ref "J7")
      (value "3-641215-2")
      (footprint "eagle-import:3-641215-2")
      (libsource (lib "eagle-import") (part "3-641215-2"))
    )
    (comp (ref "J8")
      (value "3-641215-2")
      (footprint "eagle-import:3-641215-2")
      (libsource (lib "eagle-import") (part "3-641215-2"))
    )
    (comp (ref "J9")
      (value "3-641215-2")
      (footprint "eagle-import:3-641215-2")
      (libsource (lib "eagle-import") (part "3-641215-2"))
    )
    (comp (ref "J10")
      (value "3-641215-2")
      (footprint "eagle-import:3-641215-2")
      (libsource (lib "eagle-import") (part "3-641215-2"))
    )
    (comp (ref "J11")
      (value "3-641215-2")
      (footprint "eagle-import:3-641215-2")
      (libsource (lib "eagle-import") (part "3-641215-2"))
    )
    (comp (ref "J12")
      (value "USB_A_180")
      (footprint "eagle-import:USB_B_180")
      (libsource (lib "eagle-import") (part "USB_B_180"))
    )
    (comp (ref "J13")
      (value "MTA07-156")
      (footprint "eagle-import:1X7MTA")
      (libsource (lib "eagle-import") (part "MTA07-156"))
    )
    (comp (ref "J14")
      (value "pin1x8")
      (footprint "eagle-import:MA08-1-MALE")
      (libsource (lib "eagle-import") (part "MA08-1-M"))
    )
    (comp (ref "J15")
      (value "3-641215-2")
      (footprint "eagle-import:3-641215-2")
      (libsource (lib "eagle-import") (part "3-641215-2"))
    )
    (comp (ref "J16")
      (value "3-641215-2")
      (footprint "eagle-import:3-641215-2")
      (libsource (lib "eagle-import") (part "3-641215-2"))
    )
    (comp (ref "J17")
      (value "DNP-open-hole")
      (footprint "eagle-import:MA05-1")
      (libsource (lib "eagle-import") (part "MA05-1"))
    )
    (comp (ref "J18")
      (value "3-641215-2")
      (footprint "eagle-import:3-641215-2")
      (libsource (lib "eagle-import") (part "3-641215-2"))
    )
    (comp (ref "JP1")
      (value "JP3CLOSE12")
      (footprint "eagle-import:JP3CLOSE12")
      (libsource (lib "eagle-import") (part "JP3CLOSE12"))
    )
    (comp (ref "L1")
      (value "LQM31PN3R3M00L")
      (footprint "eagle-import:1206@1")
      (libsource (lib "eagle-import") (part "L-1206"))
    )
    (comp (ref "L2")
      (value "LQM31PN3R3M00L")
      (footprint "eagle-import:1206@1")
      (libsource (lib "eagle-import") (part "L-1206"))
    )
    (comp (ref "L3")
      (value "LQM31PN3R3M00L")
      (footprint "eagle-import:1206@1")
      (libsource (lib "eagle-import") (part "L-1206"))
    )
    (comp (ref "L4")
      (value "LQM31PN3R3M00L")
      (footprint "eagle-import:1206@1")
      (libsource (lib "eagle-import") (part "L-1206"))
    )
    (comp (ref "L5")
      (value "LQM31PN3R3M00L")
      (footprint "eagle-import:1206@1")
      (libsource (lib "eagle-import") (part "L-1206"))
    )
    (comp (ref "L6")
      (value "LQM31PN3R3M00L")
      (footprint "eagle-import:1206@1")
      (libsource (lib "eagle-import") (part "L-1206"))
    )
    (comp (ref "L7")
      (value "HI1206T500R")
      (footprint "eagle-import:1206@1")
      (libsource (lib "eagle-import") (part "L-1206"))
    )
    (comp (ref "L8")
      (value "HI1206T500R")
      (footprint "eagle-import:1206@1")
      (libsource (lib "eagle-import") (part "L-1206"))
    )
    (comp (ref "L9")
      (value "NR6028T4R7M")
      (footprint "eagle-import:NR6028")
      (libsource (lib "eagle-import") (part "NR6028"))
    )
    (comp (ref "L10")
      (value "HI1206T500R")
      (footprint "eagle-import:1206@1")
      (libsource (lib "eagle-import") (part "L-1206"))
    )
    (comp (ref "L11")
      (value "HI1206T500R")
      (footprint "eagle-import:1206@1")
      (libsource (lib "eagle-import") (part "L-1206"))
    )
    (comp (ref "L12")
      (value "HI1206T500R")
      (footprint "eagle-import:1206@1")
      (libsource (lib "eagle-import") (part "L-1206"))
    )
    (comp (ref "L13")
      (value "LQM31PN3R3M00L")
      (footprint "eagle-import:1206@1")
      (libsource (lib "eagle-import") (part "L-1206"))
    )
    (comp (ref "O1")
      (value "PIC-OUT")
      (footprint "eagle-import:TEMP-PAD")
      (libsource (lib "eagle-import") (part "PIC-OUT"))
    )
    (comp (ref "O2")
      (value "PIC-RPX")
      (footprint "eagle-import:TEMP-PAD")
      (libsource (lib "eagle-import") (part "PIC-RPX"))
    )
    (comp (ref "O3")
      (value "PIC-RPX")
      (footprint "eagle-import:TEMP-PAD")
      (libsource (lib "eagle-import") (part "PIC-RPX"))
    )
    (comp (ref "O4")
      (value "PIC-RPX")
      (footprint "eagle-import:TEMP-PAD")
      (libsource (lib "eagle-import") (part "PIC-RPX"))
    )
    (comp (ref "O6")
      (value "PIC-RPX")
      (footprint "eagle-import:TEMP-PAD")
      (libsource (lib "eagle-import") (part "PIC-RPX"))
    )
    (comp (ref "O7")
      (value "PIC-RPX")
      (footprint "eagle-import:TEMP-PAD")
      (libsource (lib "eagle-import") (part "PIC-RPX"))
    )
    (comp (ref "O8")
      (value "PIC-RPX")
      (footprint "eagle-import:TEMP-PAD")
      (libsource (lib "eagle-import") (part "PIC-RPX"))
    )
    (comp (ref "O9")
      (value "PIC-OUT")
      (footprint "eagle-import:TEMP-PAD")
      (libsource (lib "eagle-import") (part "PIC-OUT"))
    )
    (comp (ref "O12")
      (value "PIC-RPX")
      (footprint "eagle-import:TEMP-PAD")
      (libsource (lib "eagle-import") (part "PIC-RPX"))
    )
    (comp (ref "O13")
      (value "PIC-RPX")
      (footprint "eagle-import:TEMP-PAD")
      (libsource (lib "eagle-import") (part "PIC-RPX"))
    )
    (comp (ref "O14")
      (value "PIC-RPX")
      (footprint "eagle-import:TEMP-PAD")
      (libsource (lib "eagle-import") (part "PIC-RPX"))
    )
    (comp (ref "O15")
      (value "PIC-RPX")
      (footprint "eagle-import:TEMP-PAD")
      (libsource (lib "eagle-import") (part "PIC-RPX"))
    )
    (comp (ref "O16")
      (value "PIC-RPX")
      (footprint "eagle-import:TEMP-PAD")
      (libsource (lib "eagle-import") (part "PIC-RPX"))
    )
    (comp (ref "O17")
      (value "PIC-OUT")
      (footprint "eagle-import:TEMP-PAD")
      (libsource (lib "eagle-import") (part "PIC-OUT"))
    )
    (comp (ref "O18")
      (value "PIC-RPX")
      (footprint "eagle-import:TEMP-PAD")
      (libsource (lib "eagle-import") (part "PIC-RPX"))
    )
    (comp (ref "O19")
      (value "PIC-RPX")
      (footprint "eagle-import:TEMP-PAD")
      (libsource (lib "eagle-import") (part "PIC-RPX"))
    )
    (comp (ref "O20")
      (value "PIC-RPX")
      (footprint "eagle-import:TEMP-PAD")
      (libsource (lib "eagle-import") (part "PIC-RPX"))
    )
    (comp (ref "O21")
      (value "PIC-RPX")
      (footprint "eagle-import:TEMP-PAD")
      (libsource (lib "eagle-import") (part "PIC-RPX"))
    )
    (comp (ref "O22")
      (value "PIC-OUT")
      (footprint "eagle-import:TEMP-PAD")
      (libsource (lib "eagle-import") (part "PIC-OUT"))
    )
    (comp (ref "O23")
      (value "PIC-OUT")
      (footprint "eagle-import:TEMP-PAD")
      (libsource (lib "eagle-import") (part "PIC-OUT"))
    )
    (comp (ref "O24")
      (value "PIC-OUT")
      (footprint "eagle-import:TEMP-PAD")
      (libsource (lib "eagle-import") (part "PIC-OUT"))
    )
    (comp (ref "O25")
      (value "PIC-OUT")
      (footprint "eagle-import:TEMP-PAD")
      (libsource (lib "eagle-import") (part "PIC-OUT"))
    )
    (comp (ref "O26")
      (value "PIC-OUT")
      (footprint "eagle-import:TEMP-PAD")
      (libsource (lib "eagle-import") (part "PIC-OUT"))
    )
    (comp (ref "O27")
      (value "PIC-RPX")
      (footprint "eagle-import:TEMP-PAD")
      (libsource (lib "eagle-import") (part "PIC-RPX"))
    )
    (comp (ref "O28")
      (value "PIC-RPX")
      (footprint "eagle-import:TEMP-PAD")
      (libsource (lib "eagle-import") (part "PIC-RPX"))
    )
    (comp (ref "O29")
      (value "PIC-RPX")
      (footprint "eagle-import:TEMP-PAD")
      (libsource (lib "eagle-import") (part "PIC-RPX"))
    )
    (comp (ref "O30")
      (value "PIC-RPX")
      (footprint "eagle-import:TEMP-PAD")
      (libsource (lib "eagle-import") (part "PIC-RPX"))
    )
    (comp (ref "O31")
      (value "PIC-OUT")
      (footprint "eagle-import:TEMP-PAD")
      (libsource (lib "eagle-import") (part "PIC-OUT"))
    )
    (comp (ref "O32")
      (value "PIC-OUT")
      (footprint "eagle-import:TEMP-PAD")
      (libsource (lib "eagle-import") (part "PIC-OUT"))
    )
    (comp (ref "O33")
      (value "PIC-RPX")
      (footprint "eagle-import:TEMP-PAD")
      (libsource (lib "eagle-import") (part "PIC-RPX"))
    )
    (comp (ref "O34")
      (value "PIC-RPX")
      (footprint "eagle-import:TEMP-PAD")
      (libsource (lib "eagle-import") (part "PIC-RPX"))
    )
    (comp (ref "O35")
      (value "PIC-RPX")
      (footprint "eagle-import:TEMP-PAD")
      (libsource (lib "eagle-import") (part "PIC-RPX"))
    )
    (comp (ref "O36")
      (value "PIC-RPX")
      (footprint "eagle-import:TEMP-PAD")
      (libsource (lib "eagle-import") (part "PIC-RPX"))
    )
    (comp (ref "O37")
      (value "PIC-RPX")
      (footprint "eagle-import:TEMP-PAD")
      (libsource (lib "eagle-import") (part "PIC-RPX"))
    )
    (comp (ref "O38")
      (value "PIC-RPX")
      (footprint "eagle-import:TEMP-PAD")
      (libsource (lib "eagle-import") (part "PIC-RPX"))
    )
    (comp (ref "O39")
      (value "PIC-OUT")
      (footprint "eagle-import:TEMP-PAD")
      (libsource (lib "eagle-import") (part "PIC-OUT"))
    )
    (comp (ref "O40")
      (value "PIC-OUT")
      (footprint "eagle-import:TEMP-PAD")
      (libsource (lib "eagle-import") (part "PIC-OUT"))
    )
    (comp (ref "O41")
      (value "PIC-RPX")
      (footprint "eagle-import:TEMP-PAD")
      (libsource (lib "eagle-import") (part "PIC-RPX"))
    )
    (comp (ref "O42")
      (value "PIC-RPX")
      (footprint "eagle-import:TEMP-PAD")
      (libsource (lib "eagle-import") (part "PIC-RPX"))
    )
    (comp (ref "O43")
      (value "PIC-RPX")
      (footprint "eagle-import:TEMP-PAD")
      (libsource (lib "eagle-import") (part "PIC-RPX"))
    )
    (comp (ref "O44")
      (value "PIC-OUT")
      (footprint "eagle-import:TEMP-PAD")
      (libsource (lib "eagle-import") (part "PIC-OUT"))
    )
    (comp (ref "PCB3")
      (value "DNP-PCB-BT")
      (footprint "eagle-import:BT_MODULE_BRD")
      (libsource (lib "eagle-import") (part "BT_PCBBRD"))
    )
    (comp (ref "Q1")
      (value "SSM6P49NU,LFPZ")
      (footprint "eagle-import:MICRO_FET")
      (libsource (lib "eagle-import") (part "SSM6P49PZNU,LF"))
    )
    (comp (ref "Q2")
      (value "SSM6P49NU,LFPZ")
      (footprint "eagle-import:MICRO_FET")
      (libsource (lib "eagle-import") (part "SSM6P49PZNU,LF"))
    )
    (comp (ref "Q3")
      (value "FDG6303N")
      (footprint "eagle-import:SC70-6")
      (libsource (lib "eagle-import") (part "FDG6303N"))
    )
    (comp (ref "Q4")
      (value "FDG6303N")
      (footprint "eagle-import:SC70-6")
      (libsource (lib "eagle-import") (part "FDG6303N"))
    )
    (comp (ref "Q5")
      (value "FDC6506P")
      (footprint "eagle-import:SSOT-6")
      (libsource (lib "eagle-import") (part "FDC6506D"))
    )
    (comp (ref "Q6")
      (value "FDC6506P")
      (footprint "eagle-import:SSOT-6")
      (libsource (lib "eagle-import") (part "FDC6506D"))
    )
    (comp (ref "Q7")
      (value "FDG6303N")
      (footprint "eagle-import:SC70-6")
      (libsource (lib "eagle-import") (part "FDG6303N"))
    )
    (comp (ref "Q8")
      (value "FDC6506P")
      (footprint "eagle-import:SSOT-6")
      (libsource (lib "eagle-import") (part "FDC6506D"))
    )
    (comp (ref "Q9")
      (value "FDG6303N")
      (footprint "eagle-import:SC70-6")
      (libsource (lib "eagle-import") (part "FDG6303N"))
    )
    (comp (ref "Q10")
      (value "FDG6303N")
      (footprint "eagle-import:SC70-6")
      (libsource (lib "eagle-import") (part "FDG6303N"))
    )
    (comp (ref "Q11")
      (value "FDG6303N")
      (footprint "eagle-import:SC70-6")
      (libsource (lib "eagle-import") (part "FDG6303N"))
    )
    (comp (ref "Q12")
      (value "FDG6303N")
      (footprint "eagle-import:SC70-6")
      (libsource (lib "eagle-import") (part "FDG6303N"))
    )
    (comp (ref "Q13")
      (value "FDG6303N")
      (footprint "eagle-import:SC70-6")
      (libsource (lib "eagle-import") (part "FDG6303N"))
    )
    (comp (ref "Q14")
      (value "FDG6303N")
      (footprint "eagle-import:SC70-6")
      (libsource (lib "eagle-import") (part "FDG6303N"))
    )
    (comp (ref "R1")
      (value "1M")
      (footprint "eagle-import:0603")
      (libsource (lib "eagle-import") (part "DISCRETE_211_R-0603"))
    )
    (comp (ref "R2")
      (value "1M")
      (footprint "eagle-import:0603")
      (libsource (lib "eagle-import") (part "DISCRETE_211_R-0603"))
    )
    (comp (ref "R3")
      (value "1M")
      (footprint "eagle-import:0603")
      (libsource (lib "eagle-import") (part "DISCRETE_211_R-0603"))
    )
    (comp (ref "R4")
      (value "1M")
      (footprint "eagle-import:0603")
      (libsource (lib "eagle-import") (part "DISCRETE_211_R-0603"))
    )
    (comp (ref "R5")
      (value "1M")
      (footprint "eagle-import:0603")
      (libsource (lib "eagle-import") (part "DISCRETE_211_R-0603"))
    )
    (comp (ref "R6")
      (value "0R")
      (footprint "eagle-import:0603")
      (libsource (lib "eagle-import") (part "DISCRETE_211_R-0603"))
    )
    (comp (ref "R7")
      (value "0R")
      (footprint "eagle-import:0603")
      (libsource (lib "eagle-import") (part "DISCRETE_211_R-0603"))
    )
    (comp (ref "R8")
      (value "1R")
      (footprint "eagle-import:0805")
      (libsource (lib "eagle-import") (part "R-0805"))
    )
    (comp (ref "R9")
      (value "1M")
      (footprint "eagle-import:0603")
      (libsource (lib "eagle-import") (part "DISCRETE_211_R-0603"))
    )
    (comp (ref "R10")
      (value "100k")
      (footprint "eagle-import:0603")
      (libsource (lib "eagle-import") (part "DISCRETE_211_R-0603"))
    )
    (comp (ref "R11")
      (value "10k")
      (footprint "eagle-import:0603")
      (libsource (lib "eagle-import") (part "DISCRETE_211_R-0603"))
    )
    (comp (ref "R12")
      (value "100k")
      (footprint "eagle-import:0603")
      (libsource (lib "eagle-import") (part "DISCRETE_211_R-0603"))
    )
    (comp (ref "R13")
      (value "10k")
      (footprint "eagle-import:0603")
      (libsource (lib "eagle-import") (part "DISCRETE_211_R-0603"))
    )
    (comp (ref "R14")
      (value "10k")
      (footprint "eagle-import:0603")
      (libsource (lib "eagle-import") (part "DISCRETE_211_R-0603"))
    )
    (comp (ref "R15")
      (value "10k")
      (footprint "eagle-import:0603")
      (libsource (lib "eagle-import") (part "DISCRETE_211_R-0603"))
    )
    (comp (ref "R16")
      (value "100k")
      (footprint "eagle-import:0603")
      (libsource (lib "eagle-import") (part "DISCRETE_211_R-0603"))
    )
    (comp (ref "R17")
      (value "47k")
      (footprint "eagle-import:0603")
      (libsource (lib "eagle-import") (part "DISCRETE_211_R-0603"))
    )
    (comp (ref "R18")
      (value "10k")
      (footprint "eagle-import:0603")
      (libsource (lib "eagle-import") (part "DISCRETE_211_R-0603"))
    )
    (comp (ref "R19")
      (value "560k")
      (footprint "eagle-import:0603")
      (libsource (lib "eagle-import") (part "DISCRETE_211_R-0603"))
    )
    (comp (ref "R20")
      (value "1M")
      (footprint "eagle-import:0603")
      (libsource (lib "eagle-import") (part "DISCRETE_211_R-0603"))
    )
    (comp (ref "R21")
      (value "1M")
      (footprint "eagle-import:0603")
      (libsource (lib "eagle-import") (part "DISCRETE_211_R-0603"))
    )
    (comp (ref "R22")
      (value "4M99")
      (footprint "eagle-import:0603")
      (libsource (lib "eagle-import") (part "DISCRETE_211_R-0603"))
    )
    (comp (ref "R23")
      (value "0R/1M")
      (footprint "eagle-import:0603")
      (libsource (lib "eagle-import") (part "DISCRETE_211_R-0603"))
    )
    (comp (ref "R24")
      (value "100k")
      (footprint "eagle-import:0603")
      (libsource (lib "eagle-import") (part "DISCRETE_211_R-0603"))
    )
    (comp (ref "R25")
      (value "1M")
      (footprint "eagle-import:0603")
      (libsource (lib "eagle-import") (part "DISCRETE_211_R-0603"))
    )
    (comp (ref "R26")
      (value "10k")
      (footprint "eagle-import:0603")
      (libsource (lib "eagle-import") (part "DISCRETE_211_R-0603"))
    )
    (comp (ref "R27")
      (value "10k")
      (footprint "eagle-import:0603")
      (libsource (lib "eagle-import") (part "DISCRETE_211_R-0603"))
    )
    (comp (ref "R28")
      (value "100R")
      (footprint "eagle-import:0603")
      (libsource (lib "eagle-import") (part "DISCRETE_211_R-0603"))
    )
    (comp (ref "R29")
      (value "300R")
      (footprint "eagle-import:0603")
      (libsource (lib "eagle-import") (part "DISCRETE_211_R-0603"))
    )
    (comp (ref "R30")
      (value "1M")
      (footprint "eagle-import:0603")
      (libsource (lib "eagle-import") (part "DISCRETE_211_R-0603"))
    )
    (comp (ref "R31")
      (value "1M")
      (footprint "eagle-import:0603")
      (libsource (lib "eagle-import") (part "DISCRETE_211_R-0603"))
    )
    (comp (ref "R32")
      (value "1M")
      (footprint "eagle-import:0603")
      (libsource (lib "eagle-import") (part "DISCRETE_211_R-0603"))
    )
    (comp (ref "R33")
      (value "4M99")
      (footprint "eagle-import:0603")
      (libsource (lib "eagle-import") (part "DISCRETE_211_R-0603"))
    )
    (comp (ref "R34")
      (value "1M")
      (footprint "eagle-import:0603")
      (libsource (lib "eagle-import") (part "DISCRETE_211_R-0603"))
    )
    (comp (ref "R35")
      (value "1k")
      (footprint "eagle-import:0805")
      (libsource (lib "eagle-import") (part "R-0805"))
    )
    (comp (ref "R36")
      (value "1k")
      (footprint "eagle-import:0805")
      (libsource (lib "eagle-import") (part "R-0805"))
    )
    (comp (ref "R37")
      (value "1k")
      (footprint "eagle-import:0805")
      (libsource (lib "eagle-import") (part "R-0805"))
    )
    (comp (ref "R38")
      (value "1k")
      (footprint "eagle-import:0805")
      (libsource (lib "eagle-import") (part "R-0805"))
    )
    (comp (ref "R39")
      (value "0.025R")
      (footprint "eagle-import:0805")
      (libsource (lib "eagle-import") (part "R-0805"))
    )
    (comp (ref "R40")
      (value "300k")
      (footprint "eagle-import:0603")
      (libsource (lib "eagle-import") (part "DISCRETE_211_R-0603"))
    )
    (comp (ref "R41")
      (value "1M")
      (footprint "eagle-import:0603")
      (libsource (lib "eagle-import") (part "DISCRETE_211_R-0603"))
    )
    (comp (ref "R42")
      (value "1M")
      (footprint "eagle-import:0603")
      (libsource (lib "eagle-import") (part "DISCRETE_211_R-0603"))
    )
    (comp (ref "R43")
      (value "300k")
      (footprint "eagle-import:0603")
      (libsource (lib "eagle-import") (part "DISCRETE_211_R-0603"))
    )
    (comp (ref "R44")
      (value "1M")
      (footprint "eagle-import:0603")
      (libsource (lib "eagle-import") (part "DISCRETE_211_R-0603"))
    )
    (comp (ref "R45")
      (value "1M")
      (footprint "eagle-import:0603")
      (libsource (lib "eagle-import") (part "DISCRETE_211_R-0603"))
    )
    (comp (ref "R46")
      (value "560k")
      (footprint "eagle-import:0603")
      (libsource (lib "eagle-import") (part "DISCRETE_211_R-0603"))
    )
    (comp (ref "R47")
      (value "100k")
      (footprint "eagle-import:0603")
      (libsource (lib "eagle-import") (part "DISCRETE_211_R-0603"))
    )
    (comp (ref "R48")
      (value "1M")
      (footprint "eagle-import:0603")
      (libsource (lib "eagle-import") (part "DISCRETE_211_R-0603"))
    )
    (comp (ref "R49")
      (value "1M")
      (footprint "eagle-import:0603")
      (libsource (lib "eagle-import") (part "DISCRETE_211_R-0603"))
    )
    (comp (ref "R50")
      (value "1M")
      (footprint "eagle-import:0603")
      (libsource (lib "eagle-import") (part "DISCRETE_211_R-0603"))
    )
    (comp (ref "R51")
      (value "300k")
      (footprint "eagle-import:0603")
      (libsource (lib "eagle-import") (part "DISCRETE_211_R-0603"))
    )
    (comp (ref "R52")
      (value "1M")
      (footprint "eagle-import:0603")
      (libsource (lib "eagle-import") (part "DISCRETE_211_R-0603"))
    )
    (comp (ref "R53")
      (value "300k")
      (footprint "eagle-import:0603")
      (libsource (lib "eagle-import") (part "DISCRETE_211_R-0603"))
    )
    (comp (ref "R54")
      (value "1M")
      (footprint "eagle-import:0603")
      (libsource (lib "eagle-import") (part "DISCRETE_211_R-0603"))
    )
    (comp (ref "R55")
      (value "1M")
      (footprint "eagle-import:0603")
      (libsource (lib "eagle-import") (part "DISCRETE_211_R-0603"))
    )
    (comp (ref "R56")
      (value "1M")
      (footprint "eagle-import:0603")
      (libsource (lib "eagle-import") (part "DISCRETE_211_R-0603"))
    )
    (comp (ref "R57")
      (value "300k")
      (footprint "eagle-import:0603")
      (libsource (lib "eagle-import") (part "DISCRETE_211_R-0603"))
    )
    (comp (ref "R58")
      (value "1M")
      (footprint "eagle-import:0603")
      (libsource (lib "eagle-import") (part "DISCRETE_211_R-0603"))
    )
    (comp (ref "R59")
      (value "300k")
      (footprint "eagle-import:0603")
      (libsource (lib "eagle-import") (part "DISCRETE_211_R-0603"))
    )
    (comp (ref "R60")
      (value "1M")
      (footprint "eagle-import:0603")
      (libsource (lib "eagle-import") (part "DISCRETE_211_R-0603"))
    )
    (comp (ref "R61")
      (value "1M")
      (footprint "eagle-import:0603")
      (libsource (lib "eagle-import") (part "DISCRETE_211_R-0603"))
    )
    (comp (ref "R62")
      (value "100R")
      (footprint "eagle-import:0603")
      (libsource (lib "eagle-import") (part "DISCRETE_211_R-0603"))
    )
    (comp (ref "R63")
      (value "1k->4k7")
      (footprint "eagle-import:0603")
      (libsource (lib "eagle-import") (part "DISCRETE_211_R-0603"))
    )
    (comp (ref "R64")
      (value "1k")
      (footprint "eagle-import:0603")
      (libsource (lib "eagle-import") (part "DISCRETE_211_R-0603"))
    )
    (comp (ref "R65")
      (value "1M")
      (footprint "eagle-import:0603")
      (libsource (lib "eagle-import") (part "DISCRETE_211_R-0603"))
    )
    (comp (ref "R66")
      (value "100k")
      (footprint "eagle-import:0603")
      (libsource (lib "eagle-import") (part "DISCRETE_211_R-0603"))
    )
    (comp (ref "R67")
      (value "1M")
      (footprint "eagle-import:0603")
      (libsource (lib "eagle-import") (part "DISCRETE_211_R-0603"))
    )
    (comp (ref "R68")
      (value "100R")
      (footprint "eagle-import:0603")
      (libsource (lib "eagle-import") (part "DISCRETE_211_R-0603"))
    )
    (comp (ref "R69")
      (value "1k->4k7")
      (footprint "eagle-import:0603")
      (libsource (lib "eagle-import") (part "DISCRETE_211_R-0603"))
    )
    (comp (ref "R70")
      (value "1k")
      (footprint "eagle-import:0603")
      (libsource (lib "eagle-import") (part "DISCRETE_211_R-0603"))
    )
    (comp (ref "R71")
      (value "10k")
      (footprint "eagle-import:0603")
      (libsource (lib "eagle-import") (part "DISCRETE_211_R-0603"))
    )
    (comp (ref "R72")
      (value "1M")
      (footprint "eagle-import:0603")
      (libsource (lib "eagle-import") (part "DISCRETE_211_R-0603"))
    )
    (comp (ref "R73")
      (value "1M")
      (footprint "eagle-import:0603")
      (libsource (lib "eagle-import") (part "DISCRETE_211_R-0603"))
    )
    (comp (ref "R74")
      (value "100k")
      (footprint "eagle-import:0603")
      (libsource (lib "eagle-import") (part "DISCRETE_211_R-0603"))
    )
    (comp (ref "R75")
      (value "100k")
      (footprint "eagle-import:0603")
      (libsource (lib "eagle-import") (part "DISCRETE_211_R-0603"))
    )
    (comp (ref "R76")
      (value "1M")
      (footprint "eagle-import:0603")
      (libsource (lib "eagle-import") (part "DISCRETE_211_R-0603"))
    )
    (comp (ref "R77")
      (value "47k")
      (footprint "eagle-import:0603")
      (libsource (lib "eagle-import") (part "DISCRETE_211_R-0603"))
    )
    (comp (ref "R78")
      (value "100R")
      (footprint "eagle-import:0603")
      (libsource (lib "eagle-import") (part "DISCRETE_211_R-0603"))
    )
    (comp (ref "R79")
      (value "1k->4k7")
      (footprint "eagle-import:0603")
      (libsource (lib "eagle-import") (part "DISCRETE_211_R-0603"))
    )
    (comp (ref "R80")
      (value "1k")
      (footprint "eagle-import:0603")
      (libsource (lib "eagle-import") (part "DISCRETE_211_R-0603"))
    )
    (comp (ref "R81")
      (value "100k")
      (footprint "eagle-import:0603")
      (libsource (lib "eagle-import") (part "DISCRETE_211_R-0603"))
    )
    (comp (ref "R82")
      (value "1M")
      (footprint "eagle-import:0603")
      (libsource (lib "eagle-import") (part "DISCRETE_211_R-0603"))
    )
    (comp (ref "R83")
      (value "1M")
      (footprint "eagle-import:0603")
      (libsource (lib "eagle-import") (part "DISCRETE_211_R-0603"))
    )
    (comp (ref "R84")
      (value "100R")
      (footprint "eagle-import:0603")
      (libsource (lib "eagle-import") (part "DISCRETE_211_R-0603"))
    )
    (comp (ref "R85")
      (value "1k->4k7")
      (footprint "eagle-import:0603")
      (libsource (lib "eagle-import") (part "DISCRETE_211_R-0603"))
    )
    (comp (ref "R86")
      (value "1k")
      (footprint "eagle-import:0603")
      (libsource (lib "eagle-import") (part "DISCRETE_211_R-0603"))
    )
    (comp (ref "R87")
      (value "1M")
      (footprint "eagle-import:0603")
      (libsource (lib "eagle-import") (part "DISCRETE_211_R-0603"))
    )
    (comp (ref "R88")
      (value "1M")
      (footprint "eagle-import:0603")
      (libsource (lib "eagle-import") (part "DISCRETE_211_R-0603"))
    )
    (comp (ref "R89")
      (value "100k")
      (footprint "eagle-import:0603")
      (libsource (lib "eagle-import") (part "DISCRETE_211_R-0603"))
    )
    (comp (ref "R90")
      (value "1k")
      (footprint "eagle-import:0603")
      (libsource (lib "eagle-import") (part "DISCRETE_211_R-0603"))
    )
    (comp (ref "R91")
      (value "10k")
      (footprint "eagle-import:0603")
      (libsource (lib "eagle-import") (part "DISCRETE_211_R-0603"))
    )
    (comp (ref "R92")
      (value "10R")
      (footprint "eagle-import:0603")
      (libsource (lib "eagle-import") (part "DISCRETE_211_R-0603"))
    )
    (comp (ref "R93")
      (value "300R")
      (footprint "eagle-import:0603")
      (libsource (lib "eagle-import") (part "DISCRETE_211_R-0603"))
    )
    (comp (ref "R94")
      (value "180k")
      (footprint "eagle-import:0603")
      (libsource (lib "eagle-import") (part "DISCRETE_211_R-0603"))
    )
    (comp (ref "R95")
      (value "4M99")
      (footprint "eagle-import:0603")
      (libsource (lib "eagle-import") (part "DISCRETE_211_R-0603"))
    )
    (comp (ref "R96")
      (value "560k")
      (footprint "eagle-import:0603")
      (libsource (lib "eagle-import") (part "DISCRETE_211_R-0603"))
    )
    (comp (ref "R97")
      (value "180k")
      (footprint "eagle-import:0603")
      (libsource (lib "eagle-import") (part "DISCRETE_211_R-0603"))
    )
    (comp (ref "R98")
      (value "4M99")
      (footprint "eagle-import:0603")
      (libsource (lib "eagle-import") (part "DISCRETE_211_R-0603"))
    )
    (comp (ref "R99")
      (value "560k")
      (footprint "eagle-import:0603")
      (libsource (lib "eagle-import") (part "R-0603"))
    )
    (comp (ref "R100")
      (value "2k2")
      (footprint "eagle-import:0603")
      (libsource (lib "eagle-import") (part "DISCRETE_211_R-0603"))
    )
    (comp (ref "R101")
      (value "2k2")
      (footprint "eagle-import:0603")
      (libsource (lib "eagle-import") (part "DISCRETE_211_R-0603"))
    )
    (comp (ref "R102")
      (value "1k")
      (footprint "eagle-import:0603")
      (libsource (lib "eagle-import") (part "DISCRETE_211_R-0603"))
    )
    (comp (ref "R103")
      (value "300R")
      (footprint "eagle-import:0603")
      (libsource (lib "eagle-import") (part "DISCRETE_211_R-0603"))
    )
    (comp (ref "R104")
      (value "1R")
      (footprint "eagle-import:0805")
      (libsource (lib "eagle-import") (part "R-0805"))
    )
    (comp (ref "R105")
      (value "1R")
      (footprint "eagle-import:0805")
      (libsource (lib "eagle-import") (part "R-0805"))
    )
    (comp (ref "R106")
      (value "1R")
      (footprint "eagle-import:0805")
      (libsource (lib "eagle-import") (part "R-0805"))
    )
    (comp (ref "R107")
      (value "100k")
      (footprint "eagle-import:0603")
      (libsource (lib "eagle-import") (part "DISCRETE_211_R-0603"))
    )
    (comp (ref "R108")
      (value "10R->1R->0R")
      (footprint "eagle-import:0603")
      (libsource (lib "eagle-import") (part "DISCRETE_211_R-0603"))
    )
    (comp (ref "R109")
      (value "10R->1R->0R")
      (footprint "eagle-import:0603")
      (libsource (lib "eagle-import") (part "DISCRETE_211_R-0603"))
    )
    (comp (ref "R110")
      (value "100R")
      (footprint "eagle-import:0603")
      (libsource (lib "eagle-import") (part "DISCRETE_211_R-0603"))
    )
    (comp (ref "R111")
      (value "100R")
      (footprint "eagle-import:0603")
      (libsource (lib "eagle-import") (part "DISCRETE_211_R-0603"))
    )
    (comp (ref "R112")
      (value "1M")
      (footprint "eagle-import:0603")
      (libsource (lib "eagle-import") (part "DISCRETE_211_R-0603"))
    )
    (comp (ref "R113")
      (value "100R")
      (footprint "eagle-import:0603")
      (libsource (lib "eagle-import") (part "DISCRETE_211_R-0603"))
    )
    (comp (ref "R114")
      (value "100R")
      (footprint "eagle-import:0603")
      (libsource (lib "eagle-import") (part "DISCRETE_211_R-0603"))
    )
    (comp (ref "R115")
      (value "100R")
      (footprint "eagle-import:0603")
      (libsource (lib "eagle-import") (part "DISCRETE_211_R-0603"))
    )
    (comp (ref "R116")
      (value "100R")
      (footprint "eagle-import:0603")
      (libsource (lib "eagle-import") (part "DISCRETE_211_R-0603"))
    )
    (comp (ref "R117")
      (value "100R")
      (footprint "eagle-import:0603")
      (libsource (lib "eagle-import") (part "DISCRETE_211_R-0603"))
    )
    (comp (ref "R118")
      (value "1M")
      (footprint "eagle-import:0603")
      (libsource (lib "eagle-import") (part "DISCRETE_211_R-0603"))
    )
    (comp (ref "R119")
      (value "100R")
      (footprint "eagle-import:0603")
      (libsource (lib "eagle-import") (part "DISCRETE_211_R-0603"))
    )
    (comp (ref "R120")
      (value "4.7K")
      (footprint "eagle-import:0603")
      (libsource (lib "eagle-import") (part "DISCRETE_211_R-0603"))
    )
    (comp (ref "R121")
      (value "4.7K")
      (footprint "eagle-import:0603")
      (libsource (lib "eagle-import") (part "DISCRETE_211_R-0603"))
    )
    (comp (ref "R122")
      (value "100R")
      (footprint "eagle-import:0603")
      (libsource (lib "eagle-import") (part "DISCRETE_211_R-0603"))
    )
    (comp (ref "R123")
      (value "100R")
      (footprint "eagle-import:0603")
      (libsource (lib "eagle-import") (part "DISCRETE_211_R-0603"))
    )
    (comp (ref "R124")
      (value "0R")
      (footprint "eagle-import:0603")
      (libsource (lib "eagle-import") (part "DISCRETE_211_R-0603"))
    )
    (comp (ref "R125")
      (value "0R")
      (footprint "eagle-import:0603")
      (libsource (lib "eagle-import") (part "DISCRETE_211_R-0603"))
    )
    (comp (ref "R126")
      (value "0R")
      (footprint "eagle-import:0603")
      (libsource (lib "eagle-import") (part "DISCRETE_211_R-0603"))
    )
    (comp (ref "R127")
      (value "4.7K")
      (footprint "eagle-import:0603")
      (libsource (lib "eagle-import") (part "DISCRETE_211_R-0603"))
    )
    (comp (ref "R128")
      (value "10k")
      (footprint "eagle-import:0603")
      (libsource (lib "eagle-import") (part "DISCRETE_211_R-0603"))
    )
    (comp (ref "R129")
      (value "DNP/0R")
      (footprint "eagle-import:0603")
      (libsource (lib "eagle-import") (part "DISCRETE_211_R-0603"))
    )
    (comp (ref "R130")
      (value "100k")
      (footprint "eagle-import:0603")
      (libsource (lib "eagle-import") (part "DISCRETE_211_R-0603"))
    )
    (comp (ref "R131")
      (value "100k")
      (footprint "eagle-import:0603")
      (libsource (lib "eagle-import") (part "DISCRETE_211_R-0603"))
    )
    (comp (ref "R132")
      (value "1M")
      (footprint "eagle-import:0603")
      (libsource (lib "eagle-import") (part "DISCRETE_211_R-0603"))
    )
    (comp (ref "R133")
      (value "4.7K")
      (footprint "eagle-import:0603")
      (libsource (lib "eagle-import") (part "DISCRETE_211_R-0603"))
    )
    (comp (ref "REF1")
      (value "REF")
      (footprint "eagle-import:REF")
      (libsource (lib "eagle-import") (part "REF"))
    )
    (comp (ref "REF2")
      (value "REF")
      (footprint "eagle-import:REF")
      (libsource (lib "eagle-import") (part "REF"))
    )
    (comp (ref "T1")
      (value "PIC-OUT")
      (footprint "eagle-import:TEMP-PAD")
      (libsource (lib "eagle-import") (part "PIC-OUT"))
    )
    (comp (ref "T2")
      (value "PIC-OUT")
      (footprint "eagle-import:TEMP-PAD")
      (libsource (lib "eagle-import") (part "PIC-OUT"))
    )
    (comp (ref "T3")
      (value "PIC-RPX")
      (footprint "eagle-import:TEMP-PAD")
      (libsource (lib "eagle-import") (part "PIC-RPX"))
    )
    (comp (ref "T4")
      (value "PIC-OUT")
      (footprint "eagle-import:TEMP-PAD")
      (libsource (lib "eagle-import") (part "PIC-OUT"))
    )
    (comp (ref "T5")
      (value "PIC-OUT")
      (footprint "eagle-import:TEMP-PAD")
      (libsource (lib "eagle-import") (part "PIC-OUT"))
    )
    (comp (ref "T6")
      (value "PIC-OUT")
      (footprint "eagle-import:TEMP-PAD")
      (libsource (lib "eagle-import") (part "PIC-OUT"))
    )
    (comp (ref "T7")
      (value "PIC-OUT")
      (footprint "eagle-import:TEMP-PAD")
      (libsource (lib "eagle-import") (part "PIC-OUT"))
    )
    (comp (ref "T8")
      (value "PIC-OUT")
      (footprint "eagle-import:TEMP-PAD")
      (libsource (lib "eagle-import") (part "PIC-OUT"))
    )
    (comp (ref "T9")
      (value "PIC-RPX")
      (footprint "eagle-import:TEMP-PAD")
      (libsource (lib "eagle-import") (part "PIC-RPX"))
    )
    (comp (ref "T10")
      (value "PIC-RPX")
      (footprint "eagle-import:TEMP-PAD")
      (libsource (lib "eagle-import") (part "PIC-RPX"))
    )
    (comp (ref "T11")
      (value "PIC-RPX")
      (footprint "eagle-import:TEMP-PAD")
      (libsource (lib "eagle-import") (part "PIC-RPX"))
    )
    (comp (ref "T12")
      (value "PIC-RPX")
      (footprint "eagle-import:TEMP-PAD")
      (libsource (lib "eagle-import") (part "PIC-RPX"))
    )
    (comp (ref "T13")
      (value "PIC-RPX")
      (footprint "eagle-import:TEMP-PAD")
      (libsource (lib "eagle-import") (part "PIC-RPX"))
    )
    (comp (ref "T14")
      (value "PIC-RPX")
      (footprint "eagle-import:TEMP-PAD")
      (libsource (lib "eagle-import") (part "PIC-RPX"))
    )
    (comp (ref "T15")
      (value "PIC-OUT")
      (footprint "eagle-import:TEMP-PAD")
      (libsource (lib "eagle-import") (part "PIC-OUT"))
    )
    (comp (ref "T16")
      (value "PIC-RPX")
      (footprint "eagle-import:TEMP-PAD")
      (libsource (lib "eagle-import") (part "PIC-RPX"))
    )
    (comp (ref "T17")
      (value "PIC-RPX")
      (footprint "eagle-import:TEMP-PAD")
      (libsource (lib "eagle-import") (part "PIC-RPX"))
    )
    (comp (ref "T18")
      (value "PIC-RPX")
      (footprint "eagle-import:TEMP-PAD")
      (libsource (lib "eagle-import") (part "PIC-RPX"))
    )
    (comp (ref "T19")
      (value "PIC-RPX")
      (footprint "eagle-import:TEMP-PAD")
      (libsource (lib "eagle-import") (part "PIC-RPX"))
    )
    (comp (ref "T20")
      (value "PIC-OUT")
      (footprint "eagle-import:TEMP-PAD")
      (libsource (lib "eagle-import") (part "PIC-OUT"))
    )
    (comp (ref "T21")
      (value "PIC-OUT")
      (footprint "eagle-import:TEMP-PAD")
      (libsource (lib "eagle-import") (part "PIC-OUT"))
    )
    (comp (ref "T27")
      (value "PIC-OUT")
      (footprint "eagle-import:TEMP-PAD")
      (libsource (lib "eagle-import") (part "PIC-OUT"))
    )
    (comp (ref "T28")
      (value "PIC-OUT")
      (footprint "eagle-import:TEMP-PAD")
      (libsource (lib "eagle-import") (part "PIC-OUT"))
    )
    (comp (ref "T30")
      (value "PIC-OUT")
      (footprint "eagle-import:TEMP-PAD")
      (libsource (lib "eagle-import") (part "PIC-OUT"))
    )
    (comp (ref "T31")
      (value "PIC-OUT")
      (footprint "eagle-import:TEMP-PAD")
      (libsource (lib "eagle-import") (part "PIC-OUT"))
    )
    (comp (ref "T32")
      (value "PIC-OUT")
      (footprint "eagle-import:TEMP-PAD")
      (libsource (lib "eagle-import") (part "PIC-OUT"))
    )
    (comp (ref "T33")
      (value "PIC-OUT")
      (footprint "eagle-import:TEMP-PAD")
      (libsource (lib "eagle-import") (part "PIC-OUT"))
    )
    (comp (ref "T34")
      (value "PIC-RPX")
      (footprint "eagle-import:TEMP-PAD")
      (libsource (lib "eagle-import") (part "PIC-RPX"))
    )
    (comp (ref "T35")
      (value "PIC-RPX")
      (footprint "eagle-import:TEMP-PAD")
      (libsource (lib "eagle-import") (part "PIC-RPX"))
    )
    (comp (ref "T36")
      (value "PIC-OUT")
      (footprint "eagle-import:TEMP-PAD")
      (libsource (lib "eagle-import") (part "PIC-OUT"))
    )
    (comp (ref "T37")
      (value "PIN-AN")
      (footprint "eagle-import:TEMP-PAD")
      (libsource (lib "eagle-import") (part "PIN-AN"))
    )
    (comp (ref "T38")
      (value "PIN-AN")
      (footprint "eagle-import:TEMP-PAD")
      (libsource (lib "eagle-import") (part "PIN-AN"))
    )
    (comp (ref "T39")
      (value "PIN-AN")
      (footprint "eagle-import:TEMP-PAD")
      (libsource (lib "eagle-import") (part "PIN-AN"))
    )
    (comp (ref "T40")
      (value "PIC-RPX")
      (footprint "eagle-import:TEMP-PAD")
      (libsource (lib "eagle-import") (part "PIC-RPX"))
    )
    (comp (ref "T41")
      (value "PIC-RPX")
      (footprint "eagle-import:TEMP-PAD")
      (libsource (lib "eagle-import") (part "PIC-RPX"))
    )
    (comp (ref "T42")
      (value "PIC-OUT")
      (footprint "eagle-import:TEMP-PAD")
      (libsource (lib "eagle-import") (part "PIC-OUT"))
    )
    (comp (ref "T43")
      (value "PIC-RPX")
      (footprint "eagle-import:TEMP-PAD")
      (libsource (lib "eagle-import") (part "PIC-RPX"))
    )
    (comp (ref "T44")
      (value "PIC-OUT")
      (footprint "eagle-import:TEMP-PAD")
      (libsource (lib "eagle-import") (part "PIC-OUT"))
    )
    (comp (ref "T45")
      (value "PIC-RPX")
      (footprint "eagle-import:TEMP-PAD")
      (libsource (lib "eagle-import") (part "PIC-RPX"))
    )
    (comp (ref "TP1")
      (value "DNP-TestPoint")
      (footprint "eagle-import:SMD_ROUND_1MM")
      (libsource (lib "eagle-import") (part "ROUND_SMD1MM"))
    )
    (comp (ref "TP2")
      (value "DNP-TestPoint")
      (footprint "eagle-import:TH_ROUND_14MM08MM")
      (libsource (lib "eagle-import") (part "ROUND_SMDTH1.4MM"))
    )
    (comp (ref "TP4")
      (value "DNP-TestPoint")
      (footprint "eagle-import:TH_ROUND_14MM08MM")
      (libsource (lib "eagle-import") (part "ROUND_SMDTH1.4MM"))
    )
    (comp (ref "X1")
      (value "8MHz-5x3.2mm")
      (footprint "eagle-import:7B")
      (libsource (lib "eagle-import") (part "XTAL-7B"))
    )
  )
  (nets
    (net (code "1") (name "+3.3V") (class "Default")
      (node (ref "C15") (pin "1") (pinfunction "1_1") (pintype "passive"))
      (node (ref "C21") (pin "1") (pinfunction "1_1") (pintype "passive"))
      (node (ref "C47") (pin "1") (pinfunction "1_1") (pintype "passive"))
      (node (ref "C48") (pin "1") (pinfunction "1_1") (pintype "passive"))
      (node (ref "C49") (pin "1") (pinfunction "1_1") (pintype "passive"))
      (node (ref "C50") (pin "1") (pinfunction "1_1") (pintype "passive"))
      (node (ref "C51") (pin "1") (pinfunction "1_1") (pintype "passive"))
      (node (ref "C52") (pin "1") (pinfunction "1_1") (pintype "passive"))
      (node (ref "C68") (pin "1") (pinfunction "1_1") (pintype "passive"))
      (node (ref "C69") (pin "1") (pinfunction "1_1") (pintype "passive"))
      (node (ref "C70") (pin "1") (pinfunction "1_1") (pintype "passive"))
      (node (ref "C81") (pin "+") (pinfunction "+_+") (pintype "passive"))
      (node (ref "IC1") (pin "16") (pinfunction "VDD3_16") (pintype "input"))
      (node (ref "IC1") (pin "2") (pinfunction "VDD2_2") (pintype "input"))
      (node (ref "IC1") (pin "37") (pinfunction "VDD4_37") (pintype "input"))
      (node (ref "IC1") (pin "46") (pinfunction "VDD5_46") (pintype "input"))
      (node (ref "IC1") (pin "55") (pinfunction "VUSB3V3_55") (pintype "input"))
      (node (ref "IC1") (pin "62") (pinfunction "VDD6_62") (pintype "input"))
      (node (ref "IC1") (pin "86") (pinfunction "VDD1_86") (pintype "input"))
      (node (ref "J13") (pin "2") (pinfunction "2_2") (pintype "passive"))
      (node (ref "J14") (pin "2") (pinfunction "2_2") (pintype "passive"))
      (node (ref "J17") (pin "2") (pinfunction "2_2") (pintype "passive"))
      (node (ref "L13") (pin "1") (pinfunction "1_1") (pintype "passive"))
      (node (ref "R103") (pin "2") (pinfunction "2_2") (pintype "passive"))
      (node (ref "R104") (pin "2") (pinfunction "2_2") (pintype "passive"))
      (node (ref "R105") (pin "2") (pinfunction "2_2") (pintype "passive"))
      (node (ref "R106") (pin "2") (pinfunction "2_2") (pintype "passive"))
      (node (ref "R120") (pin "1") (pinfunction "1_1") (pintype "passive"))
      (node (ref "R121") (pin "1") (pinfunction "1_1") (pintype "passive"))
      (node (ref "R127") (pin "1") (pinfunction "1_1") (pintype "passive"))
      (node (ref "R129") (pin "1") (pinfunction "1_1") (pintype "passive"))
      (node (ref "R133") (pin "1") (pinfunction "1_1") (pintype "passive"))
      (node (ref "R28") (pin "2") (pinfunction "2_2") (pintype "passive"))
      (node (ref "R65") (pin "1") (pinfunction "1_1") (pintype "passive"))
      (node (ref "R66") (pin "2") (pinfunction "2_2") (pintype "passive"))
      (node (ref "R74") (pin "2") (pinfunction "2_2") (pintype "passive"))
      (node (ref "R8") (pin "2") (pinfunction "2_2") (pintype "passive"))
      (node (ref "R81") (pin "2") (pinfunction "2_2") (pintype "passive"))
      (node (ref "R82") (pin "1") (pinfunction "1_1") (pintype "passive"))
      (node (ref "R87") (pin "1") (pinfunction "1_1") (pintype "passive"))
      (node (ref "R89") (pin "2") (pinfunction "2_2") (pintype "passive"))
      (node (ref "R9") (pin "2") (pinfunction "2_2") (pintype "passive"))
      (node (ref "R91") (pin "2") (pinfunction "2_2") (pintype "passive"))
    )
    (net (code "2") (name "+3.3V{slash}1") (class "Default")
      (node (ref "C1") (pin "1") (pinfunction "1_1") (pintype "passive"))
      (node (ref "C2") (pin "1") (pinfunction "1_1") (pintype "passive"))
      (node (ref "C28") (pin "1") (pinfunction "1_1") (pintype "passive"))
      (node (ref "C87") (pin "+") (pinfunction "+_+") (pintype "passive"))
      (node (ref "IC11") (pin "2") (pinfunction "A1_2") (pintype "input"))
      (node (ref "IC11") (pin "8") (pinfunction "VCC_8") (pintype "input"))
      (node (ref "IC2") (pin "37") (pinfunction "VCC_37") (pintype "input"))
      (node (ref "IC3") (pin "20") (pinfunction "VCC_20") (pintype "bidirectional"))
      (node (ref "IC4") (pin "20") (pinfunction "VCC_20") (pintype "bidirectional"))
      (node (ref "IC7") (pin "8") (pinfunction "VCC_8") (pintype "input"))
      (node (ref "Q2") (pin "3") (pinfunction "D_3") (pintype "passive"))
      (node (ref "Q2") (pin "P2") (pinfunction "D1_P2") (pintype "passive"))
      (node (ref "R18") (pin "1") (pinfunction "1_1") (pintype "passive"))
      (node (ref "R26") (pin "1") (pinfunction "1_1") (pintype "passive"))
      (node (ref "R27") (pin "1") (pinfunction "1_1") (pintype "passive"))
      (node (ref "R3") (pin "2") (pinfunction "2_2") (pintype "passive"))
      (node (ref "R4") (pin "2") (pinfunction "2_2") (pintype "passive"))
    )
    (net (code "3") (name "+3.3V{slash}2") (class "Default")
      (node (ref "C41") (pin "1") (pinfunction "1_1") (pintype "passive"))
      (node (ref "C86") (pin "+") (pinfunction "+_+") (pintype "passive"))
      (node (ref "IC12") (pin "8") (pinfunction "VCC_8") (pintype "input"))
      (node (ref "Q1") (pin "3") (pinfunction "D_3") (pintype "passive"))
      (node (ref "Q1") (pin "P2") (pinfunction "D1_P2") (pintype "passive"))
      (node (ref "R30") (pin "2") (pinfunction "2_2") (pintype "passive"))
      (node (ref "R34") (pin "1") (pinfunction "1_1") (pintype "passive"))
      (node (ref "R72") (pin "1") (pinfunction "1_1") (pintype "passive"))
      (node (ref "R73") (pin "2") (pinfunction "2_2") (pintype "passive"))
    )
    (net (code "4") (name "/+3.3V{slash}VPS") (class "Default")
      (node (ref "C27") (pin "1") (pinfunction "1_1") (pintype "passive"))
      (node (ref "IC9") (pin "3") (pinfunction "/WP_3") (pintype "input"))
      (node (ref "IC9") (pin "7") (pinfunction "/HOLD_7") (pintype "input"))
      (node (ref "IC9") (pin "8") (pinfunction "VCC_8") (pintype "input"))
      (node (ref "Q2") (pin "6") (pinfunction "D_6") (pintype "passive"))
      (node (ref "Q2") (pin "P1") (pinfunction "D1_P1") (pintype "passive"))
      (node (ref "R25") (pin "2") (pinfunction "2_2") (pintype "passive"))
    )
    (net (code "5") (name "/1.5V-CAM") (class "Default")
      (node (ref "L5") (pin "1") (pinfunction "1_1") (pintype "passive"))
      (node (ref "L6") (pin "2") (pinfunction "2_2") (pintype "passive"))
      (node (ref "R126") (pin "1") (pinfunction "1_1") (pintype "passive"))
    )
    (net (code "6") (name "/3.3V{slash}CAM") (class "Default")
      (node (ref "C16") (pin "+") (pinfunction "+_+") (pintype "passive"))
      (node (ref "C17") (pin "+") (pinfunction "+_+") (pintype "passive"))
      (node (ref "C18") (pin "1") (pinfunction "1_1") (pintype "passive"))
      (node (ref "IC5") (pin "1") (pinfunction "IN_1") (pintype "input"))
      (node (ref "IC5") (pin "3") (pinfunction "EN_3") (pintype "input"))
      (node (ref "L1") (pin "1") (pinfunction "1_1") (pintype "passive"))
      (node (ref "L2") (pin "2") (pinfunction "2_2") (pintype "passive"))
      (node (ref "L3") (pin "1") (pinfunction "1_1") (pintype "passive"))
      (node (ref "L4") (pin "2") (pinfunction "2_2") (pintype "passive"))
      (node (ref "Q1") (pin "6") (pinfunction "D_6") (pintype "passive"))
      (node (ref "Q1") (pin "P1") (pinfunction "D1_P1") (pintype "passive"))
      (node (ref "R11") (pin "2") (pinfunction "2_2") (pintype "passive"))
      (node (ref "R12") (pin "2") (pinfunction "2_2") (pintype "passive"))
      (node (ref "R13") (pin "2") (pinfunction "2_2") (pintype "passive"))
      (node (ref "R14") (pin "2") (pinfunction "2_2") (pintype "passive"))
      (node (ref "R15") (pin "2") (pinfunction "2_2") (pintype "passive"))
      (node (ref "R16") (pin "2") (pinfunction "2_2") (pintype "passive"))
    )
    (net (code "7") (name "/A+") (class "Default")
      (node (ref "J3") (pin "4") (pinfunction "4_4") (pintype "passive"))
      (node (ref "J4") (pin "4") (pinfunction "4_4") (pintype "passive"))
      (node (ref "L8") (pin "2") (pinfunction "2_2") (pintype "passive"))
    )
    (net (code "8") (name "/A++") (class "Default")
      (node (ref "IC12") (pin "6") (pinfunction "A_6") (pintype "bidirectional"))
      (node (ref "IC14") (pin "3") (pinfunction "3_3") (pintype "passive"))
      (node (ref "R109") (pin "2") (pinfunction "2_2") (pintype "passive"))
      (node (ref "R32") (pin "2") (pinfunction "2_2") (pintype "passive"))
      (node (ref "R34") (pin "2") (pinfunction "2_2") (pintype "passive"))
    )
    (net (code "9") (name "/A0") (class "Default")
      (node (ref "IC2") (pin "20") (pinfunction "A5_20") (pintype "input"))
      (node (ref "IC3") (pin "12") (pinfunction "Q7_12") (pintype "tri_state"))
    )
    (net (code "10") (name "/A1") (class "Default")
      (node (ref "IC2") (pin "21") (pinfunction "A4_21") (pintype "input"))
      (node (ref "IC3") (pin "13") (pinfunction "Q6_13") (pintype "tri_state"))
    )
    (net (code "11") (name "/A2") (class "Default")
      (node (ref "IC2") (pin "22") (pinfunction "A3_22") (pintype "input"))
      (node (ref "IC3") (pin "14") (pinfunction "Q5_14") (pintype "tri_state"))
    )
    (net (code "12") (name "/A3") (class "Default")
      (node (ref "IC2") (pin "23") (pinfunction "A2_23") (pintype "input"))
      (node (ref "IC3") (pin "15") (pinfunction "Q4_15") (pintype "tri_state"))
    )
    (net (code "13") (name "/A4") (class "Default")
      (node (ref "IC2") (pin "24") (pinfunction "A1_24") (pintype "input"))
      (node (ref "IC3") (pin "16") (pinfunction "Q3_16") (pintype "tri_state"))
    )
    (net (code "14") (name "/A5") (class "Default")
      (node (ref "IC2") (pin "25") (pinfunction "A0_25") (pintype "input"))
      (node (ref "IC3") (pin "17") (pinfunction "Q2_17") (pintype "tri_state"))
    )
    (net (code "15") (name "/A6") (class "Default")
      (node (ref "IC2") (pin "45") (pinfunction "A-1/D15_45") (pintype "tri_state"))
      (node (ref "IC3") (pin "18") (pinfunction "Q1_18") (pintype "tri_state"))
    )
    (net (code "16") (name "/A7") (class "Default")
      (node (ref "IC2") (pin "48") (pinfunction "A16_48") (pintype "input"))
      (node (ref "IC3") (pin "19") (pinfunction "Q0_19") (pintype "tri_state"))
    )
    (net (code "17") (name "/A8") (class "Default")
      (node (ref "IC2") (pin "19") (pinfunction "A6_19") (pintype "input"))
      (node (ref "IC4") (pin "19") (pinfunction "Q0_19") (pintype "tri_state"))
    )
    (net (code "18") (name "/A9") (class "Default")
      (node (ref "IC2") (pin "18") (pinfunction "A7_18") (pintype "input"))
      (node (ref "IC4") (pin "18") (pinfunction "Q1_18") (pintype "tri_state"))
    )
    (net (code "19") (name "/A10") (class "Default")
      (node (ref "IC2") (pin "17") (pinfunction "A17_17") (pintype "input"))
      (node (ref "IC4") (pin "17") (pinfunction "Q2_17") (pintype "tri_state"))
    )
    (net (code "20") (name "/A11") (class "Default")
      (node (ref "IC2") (pin "16") (pinfunction "A18_16") (pintype "input"))
      (node (ref "IC4") (pin "16") (pinfunction "Q3_16") (pintype "tri_state"))
    )
    (net (code "21") (name "/A12") (class "Default")
      (node (ref "IC2") (pin "9") (pinfunction "A19_9") (pintype "input"))
      (node (ref "IC4") (pin "15") (pinfunction "Q4_15") (pintype "tri_state"))
    )
    (net (code "22") (name "/A13") (class "Default")
      (node (ref "IC2") (pin "8") (pinfunction "A8_8") (pintype "input"))
      (node (ref "IC4") (pin "14") (pinfunction "Q5_14") (pintype "tri_state"))
    )
    (net (code "23") (name "/A14") (class "Default")
      (node (ref "IC2") (pin "7") (pinfunction "A9_7") (pintype "input"))
      (node (ref "IC4") (pin "13") (pinfunction "Q6_13") (pintype "tri_state"))
    )
    (net (code "24") (name "/A15") (class "Default")
      (node (ref "IC2") (pin "6") (pinfunction "A10_6") (pintype "input"))
      (node (ref "IC4") (pin "12") (pinfunction "Q7_12") (pintype "tri_state"))
    )
    (net (code "25") (name "/A16") (class "Default")
      (node (ref "IC1") (pin "32") (pinfunction "AN8/RPB8/CTED10/RB8_32") (pintype "bidirectional"))
      (node (ref "IC2") (pin "5") (pinfunction "A11_5") (pintype "input"))
    )
    (net (code "26") (name "/A17") (class "Default")
      (node (ref "IC1") (pin "33") (pinfunction "AN9/RPB9/CTED4/RB9_33") (pintype "bidirectional"))
      (node (ref "IC2") (pin "4") (pinfunction "A12_4") (pintype "input"))
    )
    (net (code "27") (name "/A18") (class "Default")
      (node (ref "IC1") (pin "34") (pinfunction "CVREFOUT/AN10/RPB10/PMA13/CTED11/RB10_34") (pintype "bidirectional"))
      (node (ref "IC2") (pin "3") (pinfunction "A13_3") (pintype "input"))
    )
    (net (code "28") (name "/A19") (class "Default")
      (node (ref "IC1") (pin "35") (pinfunction "AN11/PMA12/RB11_35") (pintype "bidirectional"))
      (node (ref "IC2") (pin "2") (pinfunction "A14_2") (pintype "input"))
    )
    (net (code "29") (name "/A20") (class "Default")
      (node (ref "IC1") (pin "41") (pinfunction "AN12/PMA11/RB12_41") (pintype "bidirectional"))
      (node (ref "IC2") (pin "1") (pinfunction "A15_1") (pintype "input"))
    )
    (net (code "30") (name "/AGND1") (class "Default")
      (node (ref "C3") (pin "1") (pinfunction "1_1") (pintype "passive"))
      (node (ref "C9") (pin "-") (pinfunction "-_-") (pintype "passive"))
      (node (ref "J1") (pin "2") (pinfunction "2_2") (pintype "passive"))
      (node (ref "R6") (pin "1") (pinfunction "1_1") (pintype "passive"))
    )
    (net (code "31") (name "/AGND2") (class "Default")
      (node (ref "C10") (pin "-") (pinfunction "-_-") (pintype "passive"))
      (node (ref "C4") (pin "1") (pinfunction "1_1") (pintype "passive"))
      (node (ref "J2") (pin "2") (pinfunction "2_2") (pintype "passive"))
      (node (ref "R7") (pin "1") (pinfunction "1_1") (pintype "passive"))
    )
    (net (code "32") (name "/AVDD1") (class "Default")
      (node (ref "C3") (pin "2") (pinfunction "2_2") (pintype "passive"))
      (node (ref "C9") (pin "+") (pinfunction "+_+") (pintype "passive"))
      (node (ref "J1") (pin "4") (pinfunction "4_4") (pintype "passive"))
      (node (ref "L1") (pin "2") (pinfunction "2_2") (pintype "passive"))
    )
    (net (code "33") (name "/AVDD2") (class "Default")
      (node (ref "C10") (pin "+") (pinfunction "+_+") (pintype "passive"))
      (node (ref "C4") (pin "2") (pinfunction "2_2") (pintype "passive"))
      (node (ref "J2") (pin "4") (pinfunction "4_4") (pintype "passive"))
      (node (ref "L2") (pin "1") (pinfunction "1_1") (pintype "passive"))
    )
    (net (code "34") (name "/B-") (class "Default")
      (node (ref "J3") (pin "5") (pinfunction "5_5") (pintype "passive"))
      (node (ref "J4") (pin "5") (pinfunction "5_5") (pintype "passive"))
      (node (ref "L7") (pin "2") (pinfunction "2_2") (pintype "passive"))
    )
    (net (code "35") (name "/B--") (class "Default")
      (node (ref "IC12") (pin "7") (pinfunction "B_7") (pintype "bidirectional"))
      (node (ref "IC14") (pin "2") (pinfunction "2_2") (pintype "passive"))
      (node (ref "R108") (pin "2") (pinfunction "2_2") (pintype "passive"))
      (node (ref "R31") (pin "1") (pinfunction "1_1") (pintype "passive"))
      (node (ref "R32") (pin "1") (pinfunction "1_1") (pintype "passive"))
    )
    (net (code "36") (name "/BT-RTS") (class "Default")
      (node (ref "IC1") (pin "83") (pinfunction "PMD14/RD6_83") (pintype "bidirectional"))
      (node (ref "J13") (pin "7") (pinfunction "7_7") (pintype "passive"))
      (node (ref "J14") (pin "7") (pinfunction "7_7") (pintype "passive"))
      (node (ref "O32") (pin "P$1") (pinfunction "TP_P$1") (pintype "passive"))
      (node (ref "T44") (pin "P$1") (pinfunction "TP_P$1") (pintype "passive"))
    )
    (net (code "37") (name "/BT-RX") (class "Default")
      (node (ref "IC1") (pin "73") (pinfunction "SOSCI/RPC13/RC13_73") (pintype "bidirectional"))
      (node (ref "J13") (pin "3") (pinfunction "3_3") (pintype "passive"))
      (node (ref "J14") (pin "3") (pinfunction "3_3") (pintype "passive"))
      (node (ref "O37") (pin "P$1") (pinfunction "TP_P$1") (pintype "passive"))
      (node (ref "T40") (pin "P$1") (pinfunction "TP_P$1") (pintype "passive"))
    )
    (net (code "38") (name "/BT-TX") (class "Default")
      (node (ref "IC1") (pin "74") (pinfunction "SOSCO/RPC14/T1CK/RC14_74") (pintype "bidirectional"))
      (node (ref "J13") (pin "4") (pinfunction "4_4") (pintype "passive"))
      (node (ref "J14") (pin "4") (pinfunction "4_4") (pintype "passive"))
      (node (ref "O36") (pin "P$1") (pinfunction "TP_P$1") (pintype "passive"))
      (node (ref "T41") (pin "P$1") (pinfunction "TP_P$1") (pintype "passive"))
    )
    (net (code "39") (name "/CON-LED") (class "Default")
      (node (ref "IC1") (pin "78") (pinfunction "AN26/RPD3/RD3_78") (pintype "bidirectional"))
      (node (ref "J13") (pin "6") (pinfunction "6_6") (pintype "passive"))
      (node (ref "J14") (pin "6") (pinfunction "6_6") (pintype "passive"))
      (node (ref "O33") (pin "P$1") (pinfunction "TP_P$1") (pintype "passive"))
      (node (ref "T43") (pin "P$1") (pinfunction "TP_P$1") (pintype "passive"))
    )
    (net (code "40") (name "/CS-SRAM") (class "Default")
      (node (ref "IC1") (pin "38") (pinfunction "TCK/CTED2/RA1_38") (pintype "bidirectional"))
      (node (ref "IC2") (pin "12") (pinfunction "CS2_12") (pintype "input"))
      (node (ref "O17") (pin "P$1") (pinfunction "TP_P$1") (pintype "passive"))
      (node (ref "R5") (pin "2") (pinfunction "2_2") (pintype "passive"))
      (node (ref "T28") (pin "P$1") (pinfunction "TP_P$1") (pintype "passive"))
    )
    (net (code "41") (name "/CURR-SENSE") (class "Default")
      (node (ref "C66") (pin "1") (pinfunction "1_1") (pintype "passive"))
      (node (ref "IC1") (pin "14") (pinfunction "AN19/C2INC/RPG9/PMA2/RG9_14") (pintype "bidirectional"))
      (node (ref "O8") (pin "P$1") (pinfunction "TP_P$1") (pintype "passive"))
      (node (ref "R102") (pin "2") (pinfunction "2_2") (pintype "passive"))
      (node (ref "T39") (pin "P$1") (pinfunction "TP_P$1") (pintype "passive"))
    )
    (net (code "42") (name "/D0") (class "Default")
      (node (ref "IC1") (pin "93") (pinfunction "PMD0/RE0_93") (pintype "bidirectional"))
      (node (ref "IC2") (pin "29") (pinfunction "D0_29") (pintype "tri_state"))
      (node (ref "IC3") (pin "9") (pinfunction "D7_9") (pintype "input"))
      (node (ref "IC4") (pin "2") (pinfunction "D0_2") (pintype "input"))
    )
    (net (code "43") (name "/D1") (class "Default")
      (node (ref "IC1") (pin "94") (pinfunction "PMD1/RE1_94") (pintype "bidirectional"))
      (node (ref "IC2") (pin "31") (pinfunction "D1_31") (pintype "tri_state"))
      (node (ref "IC3") (pin "8") (pinfunction "D6_8") (pintype "input"))
      (node (ref "IC4") (pin "3") (pinfunction "D1_3") (pintype "input"))
    )
    (net (code "44") (name "/D2") (class "Default")
      (node (ref "IC1") (pin "98") (pinfunction "AN20/PMD2/RE2_98") (pintype "bidirectional"))
      (node (ref "IC2") (pin "33") (pinfunction "D2_33") (pintype "tri_state"))
      (node (ref "IC3") (pin "7") (pinfunction "D5_7") (pintype "input"))
      (node (ref "IC4") (pin "4") (pinfunction "D2_4") (pintype "input"))
    )
    (net (code "45") (name "/D3") (class "Default")
      (node (ref "IC1") (pin "99") (pinfunction "RPE3/PMD3/RE3_99") (pintype "bidirectional"))
      (node (ref "IC2") (pin "35") (pinfunction "D3_35") (pintype "tri_state"))
      (node (ref "IC3") (pin "6") (pinfunction "D4_6") (pintype "input"))
      (node (ref "IC4") (pin "5") (pinfunction "D3_5") (pintype "input"))
    )
    (net (code "46") (name "/D4") (class "Default")
      (node (ref "IC1") (pin "100") (pinfunction "AN21/PMD4/RE4_100") (pintype "bidirectional"))
      (node (ref "IC2") (pin "38") (pinfunction "D4_38") (pintype "tri_state"))
      (node (ref "IC3") (pin "5") (pinfunction "D3_5") (pintype "input"))
      (node (ref "IC4") (pin "6") (pinfunction "D4_6") (pintype "input"))
    )
    (net (code "47") (name "/D5") (class "Default")
      (node (ref "IC1") (pin "3") (pinfunction "AN22/RPE5/PMD5/RE5_3") (pintype "bidirectional"))
      (node (ref "IC2") (pin "40") (pinfunction "D5_40") (pintype "tri_state"))
      (node (ref "IC3") (pin "4") (pinfunction "D2_4") (pintype "input"))
      (node (ref "IC4") (pin "7") (pinfunction "D5_7") (pintype "input"))
    )
    (net (code "48") (name "/D6") (class "Default")
      (node (ref "IC1") (pin "4") (pinfunction "AN23/PMD6/RE6_4") (pintype "bidirectional"))
      (node (ref "IC2") (pin "42") (pinfunction "D6_42") (pintype "tri_state"))
      (node (ref "IC3") (pin "3") (pinfunction "D1_3") (pintype "input"))
      (node (ref "IC4") (pin "8") (pinfunction "D6_8") (pintype "input"))
    )
    (net (code "49") (name "/D7") (class "Default")
      (node (ref "IC1") (pin "5") (pinfunction "AN27/PMD7/RE7_5") (pintype "bidirectional"))
      (node (ref "IC2") (pin "44") (pinfunction "D7_44") (pintype "tri_state"))
      (node (ref "IC3") (pin "2") (pinfunction "D0_2") (pintype "input"))
      (node (ref "IC4") (pin "9") (pinfunction "D7_9") (pintype "input"))
    )
    (net (code "50") (name "/DOOR-IN-EN") (class "Default")
      (node (ref "IC1") (pin "51") (pinfunction "RPF3/USBID/RF3_51") (pintype "bidirectional"))
      (node (ref "O43") (pin "P$1") (pinfunction "TP_P$1") (pintype "passive"))
      (node (ref "Q12") (pin "2") (pinfunction "G_2") (pintype "passive"))
      (node (ref "Q13") (pin "2") (pinfunction "G_2") (pintype "passive"))
      (node (ref "R76") (pin "1") (pinfunction "1_1") (pintype "passive"))
      (node (ref "R88") (pin "1") (pinfunction "1_1") (pintype "passive"))
      (node (ref "T8") (pin "P$1") (pinfunction "TP_P$1") (pintype "passive"))
    )
    (net (code "51") (name "/DOOR1IN") (class "Default")
      (node (ref "IC1") (pin "50") (pinfunction "RPF5/PMA8/RF5_50") (pintype "bidirectional"))
      (node (ref "O21") (pin "P$1") (pinfunction "TP_P$1") (pintype "passive"))
      (node (ref "Q13") (pin "3") (pinfunction "D_3") (pintype "passive"))
      (node (ref "R74") (pin "1") (pinfunction "1_1") (pintype "passive"))
      (node (ref "T12") (pin "P$1") (pinfunction "TP_P$1") (pintype "passive"))
    )
    (net (code "52") (name "/DOOR2IN") (class "Default")
      (node (ref "IC1") (pin "77") (pinfunction "AN25/RPD2/RD2_77") (pintype "bidirectional"))
      (node (ref "O34") (pin "P$1") (pinfunction "TP_P$1") (pintype "passive"))
      (node (ref "Q12") (pin "3") (pinfunction "D_3") (pintype "passive"))
      (node (ref "R89") (pin "1") (pinfunction "1_1") (pintype "passive"))
      (node (ref "T11") (pin "P$1") (pinfunction "TP_P$1") (pintype "passive"))
    )
    (net (code "53") (name "/DOVDD1") (class "Default")
      (node (ref "C11") (pin "+") (pinfunction "+_+") (pintype "passive"))
      (node (ref "C5") (pin "1") (pinfunction "1_1") (pintype "passive"))
      (node (ref "J1") (pin "11") (pinfunction "11_11") (pintype "passive"))
      (node (ref "L3") (pin "2") (pinfunction "2_2") (pintype "passive"))
    )
    (net (code "54") (name "/DOVDD2") (class "Default")
      (node (ref "C12") (pin "+") (pinfunction "+_+") (pintype "passive"))
      (node (ref "C6") (pin "1") (pinfunction "1_1") (pintype "passive"))
      (node (ref "J2") (pin "11") (pinfunction "11_11") (pintype "passive"))
      (node (ref "L4") (pin "1") (pinfunction "1_1") (pintype "passive"))
    )
    (net (code "55") (name "/DVDD1") (class "Default")
      (node (ref "C13") (pin "+") (pinfunction "+_+") (pintype "passive"))
      (node (ref "C7") (pin "2") (pinfunction "2_2") (pintype "passive"))
      (node (ref "J1") (pin "10") (pinfunction "10_10") (pintype "passive"))
      (node (ref "L5") (pin "2") (pinfunction "2_2") (pintype "passive"))
    )
    (net (code "56") (name "/DVDD2") (class "Default")
      (node (ref "C14") (pin "+") (pinfunction "+_+") (pintype "passive"))
      (node (ref "C8") (pin "2") (pinfunction "2_2") (pintype "passive"))
      (node (ref "J2") (pin "10") (pinfunction "10_10") (pintype "passive"))
      (node (ref "L6") (pin "1") (pinfunction "1_1") (pintype "passive"))
    )
    (net (code "57") (name "/D_N") (class "Default")
      (node (ref "IC1") (pin "56") (pinfunction "D-/RG3_56") (pintype "bidirectional"))
      (node (ref "IC15") (pin "2") (pinfunction "2_2") (pintype "passive"))
      (node (ref "J12") (pin "2_D-") (pinfunction "D-_2_D-") (pintype "bidirectional"))
    )
    (net (code "58") (name "/D_P") (class "Default")
      (node (ref "IC1") (pin "57") (pinfunction "D+/RG2_57") (pintype "bidirectional"))
      (node (ref "IC15") (pin "3") (pinfunction "3_3") (pintype "passive"))
      (node (ref "J12") (pin "3_D+") (pinfunction "D+_3_D+") (pintype "bidirectional"))
    )
    (net (code "59") (name "/HREF") (class "Default")
      (node (ref "IC1") (pin "6") (pinfunction "RPC1/RC1_6") (pintype "bidirectional"))
      (node (ref "J1") (pin "9") (pinfunction "9_9") (pintype "passive"))
      (node (ref "J2") (pin "9") (pinfunction "9_9") (pintype "passive"))
      (node (ref "O2") (pin "P$1") (pinfunction "TP_P$1") (pintype "passive"))
      (node (ref "T18") (pin "P$1") (pinfunction "TP_P$1") (pintype "passive"))
    )
    (net (code "60") (name "/INFRA1PWM") (class "Default")
      (node (ref "IC1") (pin "90") (pinfunction "RPG0/PMD8/RG0_90") (pintype "bidirectional"))
      (node (ref "O27") (pin "P$1") (pinfunction "TP_P$1") (pintype "passive"))
      (node (ref "R113") (pin "2") (pinfunction "2_2") (pintype "passive"))
      (node (ref "T34") (pin "P$1") (pinfunction "TP_P$1") (pintype "passive"))
    )
    (net (code "61") (name "/INFRA2PWM") (class "Default")
      (node (ref "IC1") (pin "40") (pinfunction "RPF12/RF12_40") (pintype "bidirectional"))
      (node (ref "O19") (pin "P$1") (pinfunction "TP_P$1") (pintype "passive"))
      (node (ref "R119") (pin "2") (pinfunction "2_2") (pintype "passive"))
      (node (ref "T35") (pin "P$1") (pinfunction "TP_P$1") (pintype "passive"))
    )
    (net (code "62") (name "/L1CTL") (class "Default")
      (node (ref "C79") (pin "1") (pinfunction "1_1") (pintype "passive"))
      (node (ref "J5") (pin "3") (pinfunction "3_3") (pintype "bidirectional"))
      (node (ref "Q6") (pin "4") (pinfunction "D_4") (pintype "passive"))
    )
    (net (code "63") (name "/L1PWR") (class "Default")
      (node (ref "C80") (pin "1") (pinfunction "1_1") (pintype "passive"))
      (node (ref "J5") (pin "2") (pinfunction "2_2") (pintype "bidirectional"))
      (node (ref "Q6") (pin "6") (pinfunction "D_6") (pintype "passive"))
    )
    (net (code "64") (name "/L2CTL") (class "Default")
      (node (ref "C78") (pin "1") (pinfunction "1_1") (pintype "passive"))
      (node (ref "J6") (pin "3") (pinfunction "3_3") (pintype "bidirectional"))
      (node (ref "Q8") (pin "6") (pinfunction "D_6") (pintype "passive"))
    )
    (net (code "65") (name "/L2PWR") (class "Default")
      (node (ref "C77") (pin "1") (pinfunction "1_1") (pintype "passive"))
      (node (ref "J6") (pin "2") (pinfunction "2_2") (pintype "bidirectional"))
      (node (ref "Q8") (pin "4") (pinfunction "D_4") (pintype "passive"))
    )
    (net (code "66") (name "/LAN-CTL") (class "Default")
      (node (ref "IC1") (pin "84") (pinfunction "PMD15/RD7_84") (pintype "bidirectional"))
      (node (ref "IC12") (pin "2") (pinfunction "/RE_2") (pintype "input"))
      (node (ref "IC12") (pin "3") (pinfunction "DE_3") (pintype "input"))
      (node (ref "O31") (pin "P$1") (pinfunction "TP_P$1") (pintype "passive"))
      (node (ref "R71") (pin "1") (pinfunction "1_1") (pintype "passive"))
      (node (ref "T15") (pin "P$1") (pinfunction "TP_P$1") (pintype "passive"))
    )
    (net (code "67") (name "/LAN-RX") (class "Default")
      (node (ref "IC1") (pin "88") (pinfunction "RPF1/PMD10/RF1_88") (pintype "bidirectional"))
      (node (ref "IC12") (pin "1") (pinfunction "R_1") (pintype "output"))
      (node (ref "O29") (pin "P$1") (pinfunction "TP_P$1") (pintype "passive"))
      (node (ref "R72") (pin "2") (pinfunction "2_2") (pintype "passive"))
      (node (ref "T13") (pin "P$1") (pinfunction "TP_P$1") (pintype "passive"))
    )
    (net (code "68") (name "/LAN-TX") (class "Default")
      (node (ref "IC1") (pin "87") (pinfunction "RPF0/PMD11/RF0_87") (pintype "bidirectional"))
      (node (ref "IC12") (pin "4") (pinfunction "D_4") (pintype "input"))
      (node (ref "O30") (pin "P$1") (pinfunction "TP_P$1") (pintype "passive"))
      (node (ref "R73") (pin "1") (pinfunction "1_1") (pintype "passive"))
      (node (ref "T14") (pin "P$1") (pinfunction "TP_P$1") (pintype "passive"))
    )
    (net (code "69") (name "/LATCH_SW_1") (class "Default")
      (node (ref "IC1") (pin "9") (pinfunction "RPC4/CTED7/RC4_9") (pintype "bidirectional"))
      (node (ref "J11") (pin "1") (pinfunction "1_1") (pintype "passive"))
      (node (ref "R120") (pin "2") (pinfunction "2_2") (pintype "passive"))
    )
    (net (code "70") (name "/LATCH_SW_2") (class "Default")
      (node (ref "IC1") (pin "18") (pinfunction "RPE8/RE8_18") (pintype "bidirectional"))
      (node (ref "J15") (pin "1") (pinfunction "1_1") (pintype "passive"))
      (node (ref "R127") (pin "2") (pinfunction "2_2") (pintype "passive"))
    )
    (net (code "71") (name "/LATCH_SW_3") (class "Default")
      (node (ref "IC1") (pin "19") (pinfunction "RPE9/RE9_19") (pintype "bidirectional"))
      (node (ref "J16") (pin "1") (pinfunction "1_1") (pintype "passive"))
      (node (ref "R121") (pin "2") (pinfunction "2_2") (pintype "passive"))
    )
    (net (code "72") (name "/LATCH_SW_4") (class "Default")
      (node (ref "IC1") (pin "42") (pinfunction "AN13/RB13_42") (pintype "bidirectional"))
      (node (ref "J18") (pin "1") (pinfunction "1_1") (pintype "passive"))
      (node (ref "R133") (pin "2") (pinfunction "2_2") (pintype "passive"))
    )
    (net (code "73") (name "/LED-PIC") (class "Default")
      (node (ref "IC1") (pin "1") (pinfunction "RG15_1") (pintype "bidirectional"))
      (node (ref "O1") (pin "P$1") (pinfunction "TP_P$1") (pintype "passive"))
      (node (ref "R29") (pin "1") (pinfunction "1_1") (pintype "passive"))
      (node (ref "T36") (pin "P$1") (pinfunction "TP_P$1") (pintype "passive"))
      (node (ref "TP4") (pin "P$1") (pinfunction "TP_P$1") (pintype "passive"))
    )
    (net (code "74") (name "/LEH-SRAM") (class "Default")
      (node (ref "IC1") (pin "43") (pinfunction "AN14/RPB14/PMA1/CTED5/RB14_43") (pintype "bidirectional"))
      (node (ref "IC4") (pin "11") (pinfunction "LE_11") (pintype "input"))
      (node (ref "R2") (pin "2") (pinfunction "2_2") (pintype "passive"))
    )
    (net (code "75") (name "/LEL-SRAM") (class "Default")
      (node (ref "IC1") (pin "44") (pinfunction "AN15/RPB15/PMA0/CTED6//RB15_44") (pintype "bidirectional"))
      (node (ref "IC3") (pin "11") (pinfunction "LE_11") (pintype "input"))
      (node (ref "R1") (pin "2") (pinfunction "2_2") (pintype "passive"))
    )
    (net (code "76") (name "/LOCK-IN-EN") (class "Default")
      (node (ref "IC1") (pin "60") (pinfunction "TDI/CTED9/RA4_60") (pintype "bidirectional"))
      (node (ref "O40") (pin "P$1") (pinfunction "TP_P$1") (pintype "passive"))
      (node (ref "Q10") (pin "2") (pinfunction "G_2") (pintype "passive"))
      (node (ref "Q11") (pin "2") (pinfunction "G_2") (pintype "passive"))
      (node (ref "R67") (pin "1") (pinfunction "1_1") (pintype "passive"))
      (node (ref "R83") (pin "1") (pinfunction "1_1") (pintype "passive"))
      (node (ref "T6") (pin "P$1") (pinfunction "TP_P$1") (pintype "passive"))
    )
    (net (code "77") (name "/LOCK1CTL") (class "Default")
      (node (ref "IC1") (pin "61") (pinfunction "TDO/RA5_61") (pintype "bidirectional"))
      (node (ref "O39") (pin "P$1") (pinfunction "TP_P$1") (pintype "passive"))
      (node (ref "Q7") (pin "5") (pinfunction "G_5") (pintype "passive"))
      (node (ref "R54") (pin "1") (pinfunction "1_1") (pintype "passive"))
      (node (ref "T1") (pin "P$1") (pinfunction "TP_P$1") (pintype "passive"))
    )
    (net (code "78") (name "/LOCK1IN") (class "Default")
      (node (ref "IC1") (pin "49") (pinfunction "RPF4/PMA9/RF4_49") (pintype "bidirectional"))
      (node (ref "O20") (pin "P$1") (pinfunction "TP_P$1") (pintype "passive"))
      (node (ref "Q11") (pin "3") (pinfunction "D_3") (pintype "passive"))
      (node (ref "R66") (pin "1") (pinfunction "1_1") (pintype "passive"))
      (node (ref "T10") (pin "P$1") (pinfunction "TP_P$1") (pintype "passive"))
    )
    (net (code "79") (name "/LOCK2CTL") (class "Default")
      (node (ref "IC1") (pin "91") (pinfunction "TRCLK/RA6_91") (pintype "bidirectional"))
      (node (ref "O26") (pin "P$1") (pinfunction "TP_P$1") (pintype "passive"))
      (node (ref "Q9") (pin "2") (pinfunction "G_2") (pintype "passive"))
      (node (ref "R58") (pin "1") (pinfunction "1_1") (pintype "passive"))
      (node (ref "T2") (pin "P$1") (pinfunction "TP_P$1") (pintype "passive"))
    )
    (net (code "80") (name "/LOCK2IN") (class "Default")
      (node (ref "IC1") (pin "89") (pinfunction "RPG1/PMD9/RG1_89") (pintype "bidirectional"))
      (node (ref "O28") (pin "P$1") (pinfunction "TP_P$1") (pintype "passive"))
      (node (ref "Q10") (pin "3") (pinfunction "D_3") (pintype "passive"))
      (node (ref "R81") (pin "1") (pinfunction "1_1") (pintype "passive"))
      (node (ref "T9") (pin "P$1") (pinfunction "TP_P$1") (pintype "passive"))
    )
    (net (code "81") (name "/LOCK12PWR") (class "Default")
      (node (ref "IC1") (pin "92") (pinfunction "TRD3/CTED8/RA7_92") (pintype "bidirectional"))
      (node (ref "O25") (pin "P$1") (pinfunction "TP_P$1") (pintype "passive"))
      (node (ref "Q7") (pin "2") (pinfunction "G_2") (pintype "passive"))
      (node (ref "Q9") (pin "5") (pinfunction "G_5") (pintype "passive"))
      (node (ref "R52") (pin "1") (pinfunction "1_1") (pintype "passive"))
      (node (ref "R60") (pin "1") (pinfunction "1_1") (pintype "passive"))
      (node (ref "T4") (pin "P$1") (pinfunction "TP_P$1") (pintype "passive"))
    )
    (net (code "82") (name "/OE-SRAM") (class "Default")
      (node (ref "IC1") (pin "82") (pinfunction "RPD5/PMRD/RD5_82") (pintype "bidirectional"))
      (node (ref "IC2") (pin "28") (pinfunction "~{OE}_28") (pintype "input"))
      (node (ref "R3") (pin "1") (pinfunction "1_1") (pintype "passive"))
    )
    (net (code "83") (name "/PCLK") (class "Default")
      (node (ref "IC1") (pin "76") (pinfunction "AN24/RPD1/RD1_76") (pintype "bidirectional"))
      (node (ref "J1") (pin "17") (pinfunction "17_17") (pintype "passive"))
      (node (ref "J2") (pin "17") (pinfunction "17_17") (pintype "passive"))
      (node (ref "O35") (pin "P$1") (pinfunction "TP_P$1") (pintype "passive"))
      (node (ref "T17") (pin "P$1") (pinfunction "TP_P$1") (pintype "passive"))
    )
    (net (code "84") (name "/PGC") (class "Default")
      (node (ref "IC1") (pin "24") (pinfunction "PGEC1/AN1/RPB1/CTED12/RB1_24") (pintype "bidirectional"))
      (node (ref "J17") (pin "5") (pinfunction "5_5") (pintype "passive"))
      (node (ref "R131") (pin "1") (pinfunction "1_1") (pintype "passive"))
    )
    (net (code "85") (name "/PGD") (class "Default")
      (node (ref "IC1") (pin "25") (pinfunction "PGED1/AN0/RPB0/RB0_25") (pintype "bidirectional"))
      (node (ref "J17") (pin "4") (pinfunction "4_4") (pintype "passive"))
      (node (ref "R130") (pin "2") (pinfunction "2_2") (pintype "passive"))
    )
    (net (code "86") (name "/POWER-GOOD") (class "Default")
      (node (ref "IC6") (pin "4") (pinfunction "OUT_4") (pintype "output"))
      (node (ref "R130") (pin "1") (pinfunction "1_1") (pintype "passive"))
      (node (ref "T45") (pin "P$1") (pinfunction "TP_P$1") (pintype "passive"))
      (node (ref "TP2") (pin "P$1") (pinfunction "TP_P$1") (pintype "passive"))
    )
    (net (code "87") (name "/PWDN-CAM1") (class "Default")
      (node (ref "IC1") (pin "97") (pinfunction "TRD0/RG13_97") (pintype "bidirectional"))
      (node (ref "J1") (pin "8") (pinfunction "8_8") (pintype "passive"))
      (node (ref "O22") (pin "P$1") (pinfunction "TP_P$1") (pintype "passive"))
      (node (ref "R12") (pin "1") (pinfunction "1_1") (pintype "passive"))
      (node (ref "T20") (pin "P$1") (pinfunction "TP_P$1") (pintype "passive"))
    )
    (net (code "88") (name "/PWDN-CAM2") (class "Default")
      (node (ref "IC1") (pin "39") (pinfunction "RPF13/RF13_39") (pintype "bidirectional"))
      (node (ref "J2") (pin "8") (pinfunction "8_8") (pintype "passive"))
      (node (ref "O18") (pin "P$1") (pinfunction "TP_P$1") (pintype "passive"))
      (node (ref "R16") (pin "1") (pinfunction "1_1") (pintype "passive"))
      (node (ref "T21") (pin "P$1") (pinfunction "TP_P$1") (pintype "passive"))
    )
    (net (code "89") (name "/REF-EN") (class "Default")
      (node (ref "IC1") (pin "28") (pinfunction "VREF-/CVREF-/PMA7/RA9_28") (pintype "bidirectional"))
      (node (ref "R93") (pin "1") (pinfunction "1_1") (pintype "passive"))
    )
    (net (code "90") (name "/REF2,5V") (class "Default")
      (node (ref "C57") (pin "1") (pinfunction "1_1") (pintype "passive"))
      (node (ref "IC1") (pin "29") (pinfunction "VREF+/CVREF+/PMA6/RA10_29") (pintype "bidirectional"))
      (node (ref "IC13") (pin "2") (pinfunction "VOUT_2") (pintype "bidirectional"))
    )
    (net (code "91") (name "/RESET-CAM1") (class "Default")
      (node (ref "C76") (pin "1") (pinfunction "1_1") (pintype "passive"))
      (node (ref "J1") (pin "6") (pinfunction "6_6") (pintype "passive"))
      (node (ref "R11") (pin "1") (pinfunction "1_1") (pintype "passive"))
    )
    (net (code "92") (name "/RESET-CAM2") (class "Default")
      (node (ref "C75") (pin "1") (pinfunction "1_1") (pintype "passive"))
      (node (ref "J2") (pin "6") (pinfunction "6_6") (pintype "passive"))
      (node (ref "R15") (pin "1") (pinfunction "1_1") (pintype "passive"))
    )
    (net (code "93") (name "/SCL1-EEPROM") (class "Default")
      (node (ref "IC1") (pin "66") (pinfunction "SCL1/RPA14/RA14_66") (pintype "bidirectional"))
      (node (ref "IC11") (pin "6") (pinfunction "SCL_6") (pintype "input"))
      (node (ref "IC7") (pin "6") (pinfunction "SCL_6") (pintype "input"))
      (node (ref "R26") (pin "2") (pinfunction "2_2") (pintype "passive"))
    )
    (net (code "94") (name "/SCLK2-SPI") (class "Default")
      (node (ref "IC1") (pin "10") (pinfunction "AN16/C1IND/RPG6/SCK2/PMA5/RG6_10") (pintype "bidirectional"))
      (node (ref "IC9") (pin "6") (pinfunction "C_6") (pintype "input"))
    )
    (net (code "95") (name "/SDA1-EEPROM") (class "Default")
      (node (ref "IC1") (pin "67") (pinfunction "SDA1/RPA15/RA15_67") (pintype "bidirectional"))
      (node (ref "IC11") (pin "5") (pinfunction "SDA_5") (pintype "bidirectional"))
      (node (ref "IC7") (pin "5") (pinfunction "SDA_5") (pintype "bidirectional"))
      (node (ref "R27") (pin "2") (pinfunction "2_2") (pintype "passive"))
    )
    (net (code "96") (name "/SDI2-MISO") (class "Default")
      (node (ref "IC1") (pin "22") (pinfunction "PGED3/AN3/C2INA/RPB3/RB3_22") (pintype "bidirectional"))
      (node (ref "IC9") (pin "2") (pinfunction "Q_2") (pintype "bidirectional"))
      (node (ref "O13") (pin "P$1") (pinfunction "TP_P$1") (pintype "passive"))
    )
    (net (code "97") (name "/SDO2-MOSI") (class "Default")
      (node (ref "IC1") (pin "20") (pinfunction "AN5/C1INA/RPB5/RB5_20") (pintype "bidirectional"))
      (node (ref "IC9") (pin "5") (pinfunction "D_5") (pintype "input"))
      (node (ref "O12") (pin "P$1") (pinfunction "TP_P$1") (pintype "passive"))
    )
    (net (code "98") (name "/SIO-C-CAM") (class "Default")
      (node (ref "IC1") (pin "58") (pinfunction "SCL2/RA2_58") (pintype "bidirectional"))
      (node (ref "J1") (pin "5") (pinfunction "5_5") (pintype "passive"))
      (node (ref "J2") (pin "5") (pinfunction "5_5") (pintype "passive"))
      (node (ref "R13") (pin "1") (pinfunction "1_1") (pintype "passive"))
    )
    (net (code "99") (name "/SIO-D-CAM") (class "Default")
      (node (ref "IC1") (pin "59") (pinfunction "SDA2/RA3_59") (pintype "bidirectional"))
      (node (ref "J1") (pin "3") (pinfunction "3_3") (pintype "passive"))
      (node (ref "J2") (pin "3") (pinfunction "3_3") (pintype "passive"))
      (node (ref "R14") (pin "1") (pinfunction "1_1") (pintype "passive"))
    )
    (net (code "100") (name "/VBAT-LAN") (class "Default")
      (node (ref "D3") (pin "C") (pinfunction "C_C") (pintype "passive"))
      (node (ref "J3") (pin "1") (pinfunction "1_1") (pintype "passive"))
      (node (ref "J3") (pin "3") (pinfunction "3_3") (pintype "passive"))
      (node (ref "J4") (pin "1") (pinfunction "1_1") (pintype "passive"))
      (node (ref "J4") (pin "3") (pinfunction "3_3") (pintype "passive"))
      (node (ref "L11") (pin "2") (pinfunction "2_2") (pintype "passive"))
    )
    (net (code "101") (name "/VBAT-LAN-F") (class "Default")
      (node (ref "C33") (pin "1") (pinfunction "1_1") (pintype "passive"))
      (node (ref "C34") (pin "1") (pinfunction "1_1") (pintype "passive"))
      (node (ref "D6") (pin "K") (pinfunction "K_K") (pintype "passive"))
      (node (ref "L11") (pin "1") (pinfunction "1_1") (pintype "passive"))
      (node (ref "Q5") (pin "2") (pinfunction "S_2") (pintype "passive"))
      (node (ref "Q5") (pin "5") (pinfunction "S_5") (pintype "passive"))
      (node (ref "R132") (pin "1") (pinfunction "1_1") (pintype "passive"))
      (node (ref "R36") (pin "2") (pinfunction "2_2") (pintype "passive"))
      (node (ref "R38") (pin "2") (pinfunction "2_2") (pintype "passive"))
      (node (ref "R42") (pin "1") (pinfunction "1_1") (pintype "passive"))
      (node (ref "R45") (pin "1") (pinfunction "1_1") (pintype "passive"))
      (node (ref "R94") (pin "1") (pinfunction "1_1") (pintype "passive"))
    )
    (net (code "102") (name "/VBAT-ON") (class "Default")
      (node (ref "IC1") (pin "52") (pinfunction "RPF2/RF2_52") (pintype "bidirectional"))
      (node (ref "O42") (pin "P$1") (pinfunction "TP_P$1") (pintype "passive"))
      (node (ref "Q4") (pin "2") (pinfunction "G_2") (pintype "passive"))
      (node (ref "R132") (pin "2") (pinfunction "2_2") (pintype "passive"))
      (node (ref "R41") (pin "1") (pinfunction "1_1") (pintype "passive"))
      (node (ref "T5") (pin "P$1") (pinfunction "TP_P$1") (pintype "passive"))
    )
    (net (code "103") (name "/VBAT-SENSE") (class "Default")
      (node (ref "C64") (pin "1") (pinfunction "1_1") (pintype "passive"))
      (node (ref "IC1") (pin "26") (pinfunction "PGEC2/AN6/RPB6/RB6_26") (pintype "bidirectional"))
      (node (ref "O15") (pin "P$1") (pinfunction "TP_P$1") (pintype "passive"))
      (node (ref "R100") (pin "1") (pinfunction "1_1") (pintype "passive"))
      (node (ref "T37") (pin "P$1") (pinfunction "TP_P$1") (pintype "passive"))
    )
    (net (code "104") (name "/VBATLAN-SENSE") (class "Default")
      (node (ref "C36") (pin "1") (pinfunction "1_1") (pintype "passive"))
      (node (ref "IC1") (pin "27") (pinfunction "PGED2/AN7/RPB7/CTED3/RB7_27") (pintype "bidirectional"))
      (node (ref "O16") (pin "P$1") (pinfunction "TP_P$1") (pintype "passive"))
      (node (ref "R101") (pin "1") (pinfunction "1_1") (pintype "passive"))
      (node (ref "T38") (pin "P$1") (pinfunction "TP_P$1") (pintype "passive"))
    )
    (net (code "105") (name "/VBUS") (class "Default")
      (node (ref "IC1") (pin "54") (pinfunction "VBUS_54") (pintype "input"))
      (node (ref "R128") (pin "2") (pinfunction "2_2") (pintype "passive"))
    )
    (net (code "106") (name "/VPS-ON") (class "Default")
      (node (ref "IC1") (pin "53") (pinfunction "RPF8/RF8_53") (pintype "bidirectional"))
      (node (ref "O41") (pin "P$1") (pinfunction "TP_P$1") (pintype "passive"))
      (node (ref "Q4") (pin "5") (pinfunction "G_5") (pintype "passive"))
      (node (ref "R44") (pin "1") (pinfunction "1_1") (pintype "passive"))
      (node (ref "T7") (pin "P$1") (pinfunction "TP_P$1") (pintype "passive"))
    )
    (net (code "107") (name "/VPS-PWR") (class "Default")
      (node (ref "D4") (pin "C") (pinfunction "C_C") (pintype "passive"))
      (node (ref "J3") (pin "6") (pinfunction "6_6") (pintype "passive"))
      (node (ref "J4") (pin "6") (pinfunction "6_6") (pintype "passive"))
      (node (ref "L10") (pin "2") (pinfunction "2_2") (pintype "passive"))
    )
    (net (code "108") (name "/VPS-PWR-F") (class "Default")
      (node (ref "L10") (pin "1") (pinfunction "1_1") (pintype "passive"))
      (node (ref "Q5") (pin "4") (pinfunction "D_4") (pintype "passive"))
      (node (ref "R23") (pin "2") (pinfunction "2_2") (pintype "passive"))
    )
    (net (code "109") (name "/VPS-SENSE") (class "Default")
      (node (ref "C65") (pin "1") (pinfunction "1_1") (pintype "passive"))
      (node (ref "IC1") (pin "12") (pinfunction "AN18/C2IND/RPG8/PMA3/RG8_12") (pintype "bidirectional"))
      (node (ref "O7") (pin "P$1") (pinfunction "TP_P$1") (pintype "passive"))
      (node (ref "R48") (pin "2") (pinfunction "2_2") (pintype "passive"))
      (node (ref "R49") (pin "1") (pinfunction "1_1") (pintype "passive"))
      (node (ref "T3") (pin "P$1") (pinfunction "TP_P$1") (pintype "passive"))
    )
    (net (code "110") (name "/VSYNC") (class "Default")
      (node (ref "IC1") (pin "8") (pinfunction "RPC3/RC3_8") (pintype "bidirectional"))
      (node (ref "J1") (pin "7") (pinfunction "7_7") (pintype "passive"))
      (node (ref "J2") (pin "7") (pinfunction "7_7") (pintype "passive"))
      (node (ref "O4") (pin "P$1") (pinfunction "TP_P$1") (pintype "passive"))
      (node (ref "T19") (pin "P$1") (pinfunction "TP_P$1") (pintype "passive"))
    )
    (net (code "111") (name "/WAKE-SW") (class "Default")
      (node (ref "IC1") (pin "72") (pinfunction "RPD0/INT0/RD0_72") (pintype "bidirectional"))
      (node (ref "J13") (pin "5") (pinfunction "5_5") (pintype "passive"))
      (node (ref "J14") (pin "5") (pinfunction "5_5") (pintype "passive"))
      (node (ref "O38") (pin "P$1") (pinfunction "TP_P$1") (pintype "passive"))
      (node (ref "T42") (pin "P$1") (pinfunction "TP_P$1") (pintype "passive"))
    )
    (net (code "112") (name "/WE-SRAM") (class "Default")
      (node (ref "IC1") (pin "81") (pinfunction "RPD4/PMWR/RD4_81") (pintype "bidirectional"))
      (node (ref "IC2") (pin "11") (pinfunction "~{WE}_11") (pintype "input"))
      (node (ref "R4") (pin "1") (pinfunction "1_1") (pintype "passive"))
    )
    (net (code "113") (name "/XCLK1") (class "Default")
      (node (ref "IC1") (pin "7") (pinfunction "RPC2/RC2_7") (pintype "bidirectional"))
      (node (ref "J1") (pin "13") (pinfunction "13_13") (pintype "passive"))
      (node (ref "J2") (pin "13") (pinfunction "13_13") (pintype "passive"))
      (node (ref "O3") (pin "P$1") (pinfunction "TP_P$1") (pintype "passive"))
      (node (ref "T16") (pin "P$1") (pinfunction "TP_P$1") (pintype "passive"))
    )
    (net (code "114") (name "/Y2") (class "Default")
      (node (ref "IC1") (pin "68") (pinfunction "RPD8/RTCC/RD8_68") (pintype "bidirectional"))
      (node (ref "J1") (pin "19") (pinfunction "19_19") (pintype "passive"))
      (node (ref "J2") (pin "19") (pinfunction "19_19") (pintype "passive"))
    )
    (net (code "115") (name "/Y3") (class "Default")
      (node (ref "IC1") (pin "69") (pinfunction "RPD9/RD9_69") (pintype "bidirectional"))
      (node (ref "J1") (pin "21") (pinfunction "21_21") (pintype "passive"))
      (node (ref "J2") (pin "21") (pinfunction "21_21") (pintype "passive"))
    )
    (net (code "116") (name "/Y4") (class "Default")
      (node (ref "IC1") (pin "70") (pinfunction "RPD10/SCK1/PMCS2/RD10_70") (pintype "bidirectional"))
      (node (ref "J1") (pin "22") (pinfunction "22_22") (pintype "passive"))
      (node (ref "J2") (pin "22") (pinfunction "22_22") (pintype "passive"))
    )
    (net (code "117") (name "/Y5") (class "Default")
      (node (ref "IC1") (pin "71") (pinfunction "RPD11/PMCS1/RD11_71") (pintype "bidirectional"))
      (node (ref "J1") (pin "20") (pinfunction "20_20") (pintype "passive"))
      (node (ref "J2") (pin "20") (pinfunction "20_20") (pintype "passive"))
    )
    (net (code "118") (name "/Y6") (class "Default")
      (node (ref "IC1") (pin "79") (pinfunction "RPD12/PMD12/RD12_79") (pintype "bidirectional"))
      (node (ref "J1") (pin "18") (pinfunction "18_18") (pintype "passive"))
      (node (ref "J2") (pin "18") (pinfunction "18_18") (pintype "passive"))
    )
    (net (code "119") (name "/Y7") (class "Default")
      (node (ref "IC1") (pin "80") (pinfunction "PMD13/RD13_80") (pintype "bidirectional"))
      (node (ref "J1") (pin "16") (pinfunction "16_16") (pintype "passive"))
      (node (ref "J2") (pin "16") (pinfunction "16_16") (pintype "passive"))
    )
    (net (code "120") (name "/Y8") (class "Default")
      (node (ref "IC1") (pin "47") (pinfunction "RPD14/RD14_47") (pintype "bidirectional"))
      (node (ref "J1") (pin "14") (pinfunction "14_14") (pintype "passive"))
      (node (ref "J2") (pin "14") (pinfunction "14_14") (pintype "passive"))
    )
    (net (code "121") (name "/Y9") (class "Default")
      (node (ref "IC1") (pin "48") (pinfunction "RPD15/RD15_48") (pintype "bidirectional"))
      (node (ref "J1") (pin "12") (pinfunction "12_12") (pintype "passive"))
      (node (ref "J2") (pin "12") (pinfunction "12_12") (pintype "passive"))
    )
    (net (code "122") (name "/{slash}3.3V1PWRON") (class "Default")
      (node (ref "IC1") (pin "21") (pinfunction "AN4/C1INB/USBOEN/RB4_21") (pintype "bidirectional"))
      (node (ref "O44") (pin "P$1") (pinfunction "TP_P$1") (pintype "passive"))
      (node (ref "R24") (pin "2") (pinfunction "2_2") (pintype "passive"))
      (node (ref "T32") (pin "P$1") (pinfunction "TP_P$1") (pintype "passive"))
    )
    (net (code "123") (name "/{slash}3.3V2PWRON") (class "Default")
      (node (ref "IC1") (pin "96") (pinfunction "TRD1/RG12_96") (pintype "bidirectional"))
      (node (ref "O23") (pin "P$1") (pinfunction "TP_P$1") (pintype "passive"))
      (node (ref "R75") (pin "2") (pinfunction "2_2") (pintype "passive"))
      (node (ref "T33") (pin "P$1") (pinfunction "TP_P$1") (pintype "passive"))
    )
    (net (code "124") (name "/{slash}CAM-PWRON") (class "Default")
      (node (ref "IC1") (pin "95") (pinfunction "TRD2/RG14_95") (pintype "bidirectional"))
      (node (ref "O24") (pin "P$1") (pinfunction "TP_P$1") (pintype "passive"))
      (node (ref "R10") (pin "1") (pinfunction "1_1") (pintype "passive"))
      (node (ref "T30") (pin "P$1") (pinfunction "TP_P$1") (pintype "passive"))
    )
    (net (code "125") (name "/{slash}FMEM1-CS") (class "Default")
      (node (ref "IC1") (pin "11") (pinfunction "AN17/C1INC/RPG7/PMA4/RG7_11") (pintype "bidirectional"))
      (node (ref "IC9") (pin "1") (pinfunction "/S_1") (pintype "input"))
      (node (ref "O6") (pin "P$1") (pinfunction "TP_P$1") (pintype "passive"))
      (node (ref "R25") (pin "1") (pinfunction "1_1") (pintype "passive"))
      (node (ref "T27") (pin "P$1") (pinfunction "TP_P$1") (pintype "passive"))
    )
    (net (code "126") (name "/{slash}MCLR") (class "Default")
      (node (ref "IC1") (pin "13") (pinfunction "~{MCLR}_13") (pintype "input"))
      (node (ref "J17") (pin "1") (pinfunction "1_1") (pintype "passive"))
      (node (ref "R90") (pin "2") (pinfunction "2_2") (pintype "passive"))
    )
    (net (code "127") (name "/{slash}NCS") (class "Default")
      (node (ref "IC1") (pin "23") (pinfunction "PGEC3/AN2/C2INB/RPB2/CTED13/RB2_23") (pintype "bidirectional"))
      (node (ref "O14") (pin "P$1") (pinfunction "TP_P$1") (pintype "passive"))
    )
    (net (code "128") (name "/{slash}PRESENT") (class "Default")
      (node (ref "R131") (pin "2") (pinfunction "2_2") (pintype "passive"))
    )
    (net (code "129") (name "/{slash}VPS-PWRON") (class "Default")
      (node (ref "IC1") (pin "17") (pinfunction "TMS/CTED1/RA0_17") (pintype "bidirectional"))
      (node (ref "O9") (pin "P$1") (pinfunction "TP_P$1") (pintype "passive"))
      (node (ref "R107") (pin "2") (pinfunction "2_2") (pintype "passive"))
      (node (ref "T31") (pin "P$1") (pinfunction "TP_P$1") (pintype "passive"))
    )
    (net (code "130") (name "DGND") (class "Default")
      (node (ref "C1") (pin "2") (pinfunction "2_2") (pintype "passive"))
      (node (ref "C11") (pin "-") (pinfunction "-_-") (pintype "passive"))
      (node (ref "C12") (pin "-") (pinfunction "-_-") (pintype "passive"))
      (node (ref "C13") (pin "-") (pinfunction "-_-") (pintype "passive"))
      (node (ref "C14") (pin "-") (pinfunction "-_-") (pintype "passive"))
      (node (ref "C15") (pin "2") (pinfunction "2_2") (pintype "passive"))
      (node (ref "C16") (pin "-") (pinfunction "-_-") (pintype "passive"))
      (node (ref "C17") (pin "-") (pinfunction "-_-") (pintype "passive"))
      (node (ref "C18") (pin "2") (pinfunction "2_2") (pintype "passive"))
      (node (ref "C19") (pin "2") (pinfunction "2_2") (pintype "passive"))
      (node (ref "C2") (pin "2") (pinfunction "2_2") (pintype "passive"))
      (node (ref "C20") (pin "-") (pinfunction "-_-") (pintype "passive"))
      (node (ref "C22") (pin "2") (pinfunction "2_2") (pintype "passive"))
      (node (ref "C23") (pin "2") (pinfunction "2_2") (pintype "passive"))
      (node (ref "C24") (pin "1") (pinfunction "1_1") (pintype "passive"))
      (node (ref "C27") (pin "2") (pinfunction "2_2") (pintype "passive"))
      (node (ref "C28") (pin "2") (pinfunction "2_2") (pintype "passive"))
      (node (ref "C29") (pin "2") (pinfunction "2_2") (pintype "passive"))
      (node (ref "C30") (pin "2") (pinfunction "2_2") (pintype "passive"))
      (node (ref "C31") (pin "-") (pinfunction "-_-") (pintype "passive"))
      (node (ref "C32") (pin "2") (pinfunction "2_2") (pintype "passive"))
      (node (ref "C35") (pin "2") (pinfunction "2_2") (pintype "passive"))
      (node (ref "C36") (pin "2") (pinfunction "2_2") (pintype "passive"))
      (node (ref "C37") (pin "2") (pinfunction "2_2") (pintype "passive"))
      (node (ref "C38") (pin "2") (pinfunction "2_2") (pintype "passive"))
      (node (ref "C39") (pin "2") (pinfunction "2_2") (pintype "passive"))
      (node (ref "C40") (pin "2") (pinfunction "2_2") (pintype "passive"))
      (node (ref "C41") (pin "2") (pinfunction "2_2") (pintype "passive"))
      (node (ref "C46") (pin "2") (pinfunction "2_2") (pintype "passive"))
      (node (ref "C47") (pin "2") (pinfunction "2_2") (pintype "passive"))
      (node (ref "C48") (pin "2") (pinfunction "2_2") (pintype "passive"))
      (node (ref "C49") (pin "2") (pinfunction "2_2") (pintype "passive"))
      (node (ref "C5") (pin "2") (pinfunction "2_2") (pintype "passive"))
      (node (ref "C50") (pin "2") (pinfunction "2_2") (pintype "passive"))
      (node (ref "C51") (pin "2") (pinfunction "2_2") (pintype "passive"))
      (node (ref "C52") (pin "2") (pinfunction "2_2") (pintype "passive"))
      (node (ref "C53") (pin "2") (pinfunction "2_2") (pintype "passive"))
      (node (ref "C54") (pin "-") (pinfunction "-_-") (pintype "passive"))
      (node (ref "C55") (pin "2") (pinfunction "2_2") (pintype "passive"))
      (node (ref "C56") (pin "-") (pinfunction "-_-") (pintype "passive"))
      (node (ref "C57") (pin "2") (pinfunction "2_2") (pintype "passive"))
      (node (ref "C58") (pin "2") (pinfunction "2_2") (pintype "passive"))
      (node (ref "C59") (pin "2") (pinfunction "2_2") (pintype "passive"))
      (node (ref "C6") (pin "2") (pinfunction "2_2") (pintype "passive"))
      (node (ref "C60") (pin "2") (pinfunction "2_2") (pintype "passive"))
      (node (ref "C61") (pin "2") (pinfunction "2_2") (pintype "passive"))
      (node (ref "C62") (pin "2") (pinfunction "2_2") (pintype "passive"))
      (node (ref "C63") (pin "2") (pinfunction "2_2") (pintype "passive"))
      (node (ref "C64") (pin "2") (pinfunction "2_2") (pintype "passive"))
      (node (ref "C65") (pin "2") (pinfunction "2_2") (pintype "passive"))
      (node (ref "C66") (pin "2") (pinfunction "2_2") (pintype "passive"))
      (node (ref "C67") (pin "2") (pinfunction "2_2") (pintype "passive"))
      (node (ref "C7") (pin "1") (pinfunction "1_1") (pintype "passive"))
      (node (ref "C75") (pin "2") (pinfunction "2_2") (pintype "passive"))
      (node (ref "C76") (pin "2") (pinfunction "2_2") (pintype "passive"))
      (node (ref "C77") (pin "2") (pinfunction "2_2") (pintype "passive"))
      (node (ref "C78") (pin "2") (pinfunction "2_2") (pintype "passive"))
      (node (ref "C79") (pin "2") (pinfunction "2_2") (pintype "passive"))
      (node (ref "C8") (pin "1") (pinfunction "1_1") (pintype "passive"))
      (node (ref "C80") (pin "2") (pinfunction "2_2") (pintype "passive"))
      (node (ref "C81") (pin "-") (pinfunction "-_-") (pintype "passive"))
      (node (ref "C83") (pin "2") (pinfunction "2_2") (pintype "passive"))
      (node (ref "C84") (pin "2") (pinfunction "2_2") (pintype "passive"))
      (node (ref "C85") (pin "2") (pinfunction "2_2") (pintype "passive"))
      (node (ref "C86") (pin "-") (pinfunction "-_-") (pintype "passive"))
      (node (ref "C87") (pin "-") (pinfunction "-_-") (pintype "passive"))
      (node (ref "C88") (pin "2") (pinfunction "2_2") (pintype "passive"))
      (node (ref "D2") (pin "-") (pinfunction "A_-") (pintype "passive"))
      (node (ref "D5") (pin "K") (pinfunction "K_K") (pintype "passive"))
      (node (ref "D7") (pin "A") (pinfunction "A_A") (pintype "passive"))
      (node (ref "IC1") (pin "15") (pinfunction "VSS2_15") (pintype "input"))
      (node (ref "IC1") (pin "31") (pinfunction "AVSS_31") (pintype "input"))
      (node (ref "IC1") (pin "36") (pinfunction "VSS3_36") (pintype "input"))
      (node (ref "IC1") (pin "45") (pinfunction "VSS4_45") (pintype "input"))
      (node (ref "IC1") (pin "65") (pinfunction "VSS5_65") (pintype "input"))
      (node (ref "IC1") (pin "75") (pinfunction "VSS1_75") (pintype "input"))
      (node (ref "IC10") (pin "1") (pinfunction "GND_1") (pintype "input"))
      (node (ref "IC10") (pin "2") (pinfunction "GND1_2") (pintype "input"))
      (node (ref "IC11") (pin "1") (pinfunction "A0_1") (pintype "input"))
      (node (ref "IC11") (pin "3") (pinfunction "A2_3") (pintype "input"))
      (node (ref "IC11") (pin "4") (pinfunction "GND_4") (pintype "input"))
      (node (ref "IC12") (pin "5") (pinfunction "GND_5") (pintype "input"))
      (node (ref "IC13") (pin "3") (pinfunction "GND_3") (pintype "bidirectional"))
      (node (ref "IC14") (pin "1") (pinfunction "1_1") (pintype "input"))
      (node (ref "IC15") (pin "1") (pinfunction "1_1") (pintype "input"))
      (node (ref "IC16") (pin "4") (pinfunction "V-_4") (pintype "input"))
      (node (ref "IC2") (pin "14") (pinfunction "~{UB}_14") (pintype "input"))
      (node (ref "IC2") (pin "15") (pinfunction "~{LB}_15") (pintype "input"))
      (node (ref "IC2") (pin "26") (pinfunction "~{CS1}_26") (pintype "input"))
      (node (ref "IC2") (pin "27") (pinfunction "GND1_27") (pintype "bidirectional"))
      (node (ref "IC2") (pin "46") (pinfunction "GND2_46") (pintype "bidirectional"))
      (node (ref "IC2") (pin "47") (pinfunction "~{BYTE}_47") (pintype "input"))
      (node (ref "IC3") (pin "1") (pinfunction "~{OE}_1") (pintype "input"))
      (node (ref "IC3") (pin "10") (pinfunction "GND_10") (pintype "bidirectional"))
      (node (ref "IC4") (pin "1") (pinfunction "~{OE}_1") (pintype "input"))
      (node (ref "IC4") (pin "10") (pinfunction "GND_10") (pintype "bidirectional"))
      (node (ref "IC5") (pin "2") (pinfunction "GND_2") (pintype "input"))
      (node (ref "IC6") (pin "2") (pinfunction "GND_2") (pintype "input"))
      (node (ref "IC7") (pin "1") (pinfunction "A0_1") (pintype "input"))
      (node (ref "IC7") (pin "2") (pinfunction "A1_2") (pintype "input"))
      (node (ref "IC7") (pin "3") (pinfunction "A2_3") (pintype "input"))
      (node (ref "IC7") (pin "4") (pinfunction "GND_4") (pintype "input"))
      (node (ref "IC7") (pin "7") (pinfunction "WP_7") (pintype "input"))
      (node (ref "IC8") (pin "10") (pinfunction "SYNC_10") (pintype "bidirectional"))
      (node (ref "IC8") (pin "EP") (pinfunction "GND_EP") (pintype "bidirectional"))
      (node (ref "IC9") (pin "4") (pinfunction "GND_4") (pintype "input"))
      (node (ref "J1") (pin "15") (pinfunction "15_15") (pintype "passive"))
      (node (ref "J11") (pin "2") (pinfunction "2_2") (pintype "passive"))
      (node (ref "J12") (pin "4_GND") (pinfunction "GND_4_GND") (pintype "bidirectional"))
      (node (ref "J12") (pin "SH1") (pinfunction "GND_SH1_SH1") (pintype "bidirectional"))
      (node (ref "J12") (pin "SH2") (pinfunction "GND_SH2_SH2") (pintype "bidirectional"))
      (node (ref "J13") (pin "1") (pinfunction "1_1") (pintype "passive"))
      (node (ref "J14") (pin "1") (pinfunction "1_1") (pintype "passive"))
      (node (ref "J15") (pin "2") (pinfunction "2_2") (pintype "passive"))
      (node (ref "J16") (pin "2") (pinfunction "2_2") (pintype "passive"))
      (node (ref "J17") (pin "3") (pinfunction "3_3") (pintype "passive"))
      (node (ref "J18") (pin "2") (pinfunction "2_2") (pintype "passive"))
      (node (ref "J2") (pin "15") (pinfunction "15_15") (pintype "passive"))
      (node (ref "J5") (pin "1") (pinfunction "1_1") (pintype "bidirectional"))
      (node (ref "J6") (pin "1") (pinfunction "1_1") (pintype "bidirectional"))
      (node (ref "L12") (pin "1") (pinfunction "1_1") (pintype "passive"))
      (node (ref "PCB3") (pin "1") (pinfunction "P$1_1") (pintype "bidirectional"))
      (node (ref "Q10") (pin "4") (pinfunction "S_4") (pintype "passive"))
      (node (ref "Q11") (pin "4") (pinfunction "S_4") (pintype "passive"))
      (node (ref "Q12") (pin "4") (pinfunction "S_4") (pintype "passive"))
      (node (ref "Q13") (pin "4") (pinfunction "S_4") (pintype "passive"))
      (node (ref "Q14") (pin "1") (pinfunction "S_1") (pintype "passive"))
      (node (ref "Q3") (pin "1") (pinfunction "S_1") (pintype "passive"))
      (node (ref "R1") (pin "1") (pinfunction "1_1") (pintype "passive"))
      (node (ref "R112") (pin "2") (pinfunction "2_2") (pintype "passive"))
      (node (ref "R118") (pin "2") (pinfunction "2_2") (pintype "passive"))
      (node (ref "R17") (pin "2") (pinfunction "2_2") (pintype "passive"))
      (node (ref "R19") (pin "2") (pinfunction "2_2") (pintype "passive"))
      (node (ref "R2") (pin "1") (pinfunction "1_1") (pintype "passive"))
      (node (ref "R21") (pin "2") (pinfunction "2_2") (pintype "passive"))
      (node (ref "R31") (pin "2") (pinfunction "2_2") (pintype "passive"))
      (node (ref "R40") (pin "1") (pinfunction "1_1") (pintype "passive"))
      (node (ref "R41") (pin "2") (pinfunction "2_2") (pintype "passive"))
      (node (ref "R43") (pin "1") (pinfunction "1_1") (pintype "passive"))
      (node (ref "R44") (pin "2") (pinfunction "2_2") (pintype "passive"))
      (node (ref "R46") (pin "1") (pinfunction "1_1") (pintype "passive"))
      (node (ref "R48") (pin "1") (pinfunction "1_1") (pintype "passive"))
      (node (ref "R5") (pin "1") (pinfunction "1_1") (pintype "passive"))
      (node (ref "R51") (pin "1") (pinfunction "1_1") (pintype "passive"))
      (node (ref "R52") (pin "2") (pinfunction "2_2") (pintype "passive"))
      (node (ref "R53") (pin "2") (pinfunction "2_2") (pintype "passive"))
      (node (ref "R54") (pin "2") (pinfunction "2_2") (pintype "passive"))
      (node (ref "R57") (pin "1") (pinfunction "1_1") (pintype "passive"))
      (node (ref "R58") (pin "2") (pinfunction "2_2") (pintype "passive"))
      (node (ref "R59") (pin "2") (pinfunction "2_2") (pintype "passive"))
      (node (ref "R6") (pin "2") (pinfunction "2_2") (pintype "passive"))
      (node (ref "R60") (pin "2") (pinfunction "2_2") (pintype "passive"))
      (node (ref "R64") (pin "2") (pinfunction "2_2") (pintype "passive"))
      (node (ref "R67") (pin "2") (pinfunction "2_2") (pintype "passive"))
      (node (ref "R7") (pin "2") (pinfunction "2_2") (pintype "passive"))
      (node (ref "R70") (pin "2") (pinfunction "2_2") (pintype "passive"))
      (node (ref "R71") (pin "2") (pinfunction "2_2") (pintype "passive"))
      (node (ref "R76") (pin "2") (pinfunction "2_2") (pintype "passive"))
      (node (ref "R80") (pin "2") (pinfunction "2_2") (pintype "passive"))
      (node (ref "R83") (pin "2") (pinfunction "2_2") (pintype "passive"))
      (node (ref "R86") (pin "2") (pinfunction "2_2") (pintype "passive"))
      (node (ref "R88") (pin "2") (pinfunction "2_2") (pintype "passive"))
      (node (ref "R96") (pin "2") (pinfunction "2_2") (pintype "passive"))
      (node (ref "R99") (pin "2") (pinfunction "2_2") (pintype "passive"))
    )
    (net (code "131") (name "Net-(C24-Pad2)") (class "Default")
      (node (ref "C24") (pin "2") (pinfunction "2_2") (pintype "passive"))
      (node (ref "R77") (pin "2") (pinfunction "2_2") (pintype "passive"))
    )
    (net (code "132") (name "Net-(C32-Pad1)") (class "Default")
      (node (ref "C32") (pin "1") (pinfunction "1_1") (pintype "passive"))
      (node (ref "R68") (pin "2") (pinfunction "2_2") (pintype "passive"))
      (node (ref "R69") (pin "1") (pinfunction "1_1") (pintype "passive"))
    )
    (net (code "133") (name "Net-(C37-Pad1)") (class "Default")
      (node (ref "C37") (pin "1") (pinfunction "1_1") (pintype "passive"))
      (node (ref "R78") (pin "2") (pinfunction "2_2") (pintype "passive"))
      (node (ref "R79") (pin "1") (pinfunction "1_1") (pintype "passive"))
    )
    (net (code "134") (name "Net-(C38-Pad1)") (class "Default")
      (node (ref "C38") (pin "1") (pinfunction "1_1") (pintype "passive"))
      (node (ref "R84") (pin "2") (pinfunction "2_2") (pintype "passive"))
      (node (ref "R85") (pin "1") (pinfunction "1_1") (pintype "passive"))
    )
    (net (code "135") (name "Net-(C39-Pad1)") (class "Default")
      (node (ref "C39") (pin "1") (pinfunction "1_1") (pintype "passive"))
      (node (ref "IC14") (pin "4") (pinfunction "4_4") (pintype "input"))
      (node (ref "R30") (pin "1") (pinfunction "1_1") (pintype "passive"))
    )
    (net (code "136") (name "Net-(C40-Pad1)") (class "Default")
      (node (ref "C40") (pin "1") (pinfunction "1_1") (pintype "passive"))
      (node (ref "R90") (pin "1") (pinfunction "1_1") (pintype "passive"))
      (node (ref "R91") (pin "1") (pinfunction "1_1") (pintype "passive"))
    )
    (net (code "137") (name "Net-(C46-Pad1)") (class "Default")
      (node (ref "C46") (pin "1") (pinfunction "1_1") (pintype "passive"))
      (node (ref "R62") (pin "2") (pinfunction "2_2") (pintype "passive"))
      (node (ref "R63") (pin "1") (pinfunction "1_1") (pintype "passive"))
    )
    (net (code "138") (name "Net-(C71-Pad+)") (class "Default")
      (node (ref "C71") (pin "+") (pinfunction "+_+") (pintype "passive"))
      (node (ref "C72") (pin "1") (pinfunction "1_1") (pintype "passive"))
      (node (ref "J9") (pin "1") (pinfunction "1_1") (pintype "passive"))
      (node (ref "R124") (pin "2") (pinfunction "2_2") (pintype "passive"))
    )
    (net (code "139") (name "Net-(C71-Pad-)") (class "Default")
      (node (ref "C71") (pin "-") (pinfunction "-_-") (pintype "passive"))
      (node (ref "C72") (pin "2") (pinfunction "2_2") (pintype "passive"))
      (node (ref "R110") (pin "2") (pinfunction "2_2") (pintype "passive"))
      (node (ref "R111") (pin "1") (pinfunction "1_1") (pintype "passive"))
      (node (ref "R114") (pin "2") (pinfunction "2_2") (pintype "passive"))
      (node (ref "R115") (pin "1") (pinfunction "1_1") (pintype "passive"))
    )
    (net (code "140") (name "Net-(C73-Pad+)") (class "Default")
      (node (ref "C73") (pin "+") (pinfunction "+_+") (pintype "passive"))
      (node (ref "C74") (pin "1") (pinfunction "1_1") (pintype "passive"))
      (node (ref "J10") (pin "1") (pinfunction "1_1") (pintype "passive"))
      (node (ref "R125") (pin "2") (pinfunction "2_2") (pintype "passive"))
    )
    (net (code "141") (name "Net-(C73-Pad-)") (class "Default")
      (node (ref "C73") (pin "-") (pinfunction "-_-") (pintype "passive"))
      (node (ref "C74") (pin "2") (pinfunction "2_2") (pintype "passive"))
      (node (ref "R116") (pin "2") (pinfunction "2_2") (pintype "passive"))
      (node (ref "R117") (pin "1") (pinfunction "1_1") (pintype "passive"))
      (node (ref "R122") (pin "2") (pinfunction "2_2") (pintype "passive"))
      (node (ref "R123") (pin "1") (pinfunction "1_1") (pintype "passive"))
    )
    (net (code "142") (name "Net-(D2-C)") (class "Default")
      (node (ref "C26") (pin "1") (pinfunction "1_1") (pintype "passive"))
      (node (ref "C30") (pin "1") (pinfunction "1_1") (pintype "passive"))
      (node (ref "C31") (pin "+") (pinfunction "+_+") (pintype "passive"))
      (node (ref "D2") (pin "+") (pinfunction "C_+") (pintype "passive"))
      (node (ref "IC8") (pin "1") (pinfunction "BD_1") (pintype "bidirectional"))
      (node (ref "L9") (pin "2") (pinfunction "2_2") (pintype "passive"))
      (node (ref "R129") (pin "2") (pinfunction "2_2") (pintype "passive"))
      (node (ref "R20") (pin "1") (pinfunction "1_1") (pintype "passive"))
    )
    (net (code "143") (name "Net-(D3-PadA)") (class "Default")
      (node (ref "D3") (pin "A") (pinfunction "A_A") (pintype "passive"))
      (node (ref "D4") (pin "A") (pinfunction "A_A") (pintype "passive"))
      (node (ref "J3") (pin "2") (pinfunction "2_2") (pintype "passive"))
      (node (ref "J3") (pin "7") (pinfunction "7_7") (pintype "passive"))
      (node (ref "J3") (pin "8") (pinfunction "8_8") (pintype "passive"))
      (node (ref "J4") (pin "2") (pinfunction "2_2") (pintype "passive"))
      (node (ref "J4") (pin "7") (pinfunction "7_7") (pintype "passive"))
      (node (ref "J4") (pin "8") (pinfunction "8_8") (pintype "passive"))
      (node (ref "L12") (pin "2") (pinfunction "2_2") (pintype "passive"))
    )
    (net (code "144") (name "Net-(D5-PadA)") (class "Default")
      (node (ref "D5") (pin "A") (pinfunction "A_A") (pintype "passive"))
      (node (ref "R29") (pin "2") (pinfunction "2_2") (pintype "passive"))
    )
    (net (code "145") (name "Net-(IC1-AVDD)") (class "Default")
      (node (ref "C55") (pin "1") (pinfunction "1_1") (pintype "passive"))
      (node (ref "C56") (pin "+") (pinfunction "+_+") (pintype "passive"))
      (node (ref "C88") (pin "1") (pinfunction "1_1") (pintype "passive"))
      (node (ref "IC1") (pin "30") (pinfunction "AVDD_30") (pintype "input"))
      (node (ref "R92") (pin "2") (pinfunction "2_2") (pintype "passive"))
    )
    (net (code "146") (name "Net-(IC1-CLKI{slash}RC12{slash}OSC1)") (class "Default")
      (node (ref "C60") (pin "1") (pinfunction "1_1") (pintype "passive"))
      (node (ref "IC1") (pin "63") (pinfunction "CLKI/RC12/OSC1_63") (pintype "bidirectional"))
      (node (ref "X1") (pin "3") (pinfunction "2_3") (pintype "passive"))
    )
    (net (code "147") (name "Net-(IC1-CLKO{slash}RC15{slash}OSC2)") (class "Default")
      (node (ref "C61") (pin "1") (pinfunction "1_1") (pintype "passive"))
      (node (ref "IC1") (pin "64") (pinfunction "CLKO/RC15/OSC2_64") (pintype "bidirectional"))
      (node (ref "X1") (pin "1") (pinfunction "1_1") (pintype "passive"))
    )
    (net (code "148") (name "Net-(IC1-VCAP)") (class "Default")
      (node (ref "C53") (pin "1") (pinfunction "1_1") (pintype "passive"))
      (node (ref "C54") (pin "+") (pinfunction "+_+") (pintype "passive"))
      (node (ref "IC1") (pin "85") (pinfunction "VCAP_85") (pintype "input"))
    )
    (net (code "149") (name "Net-(IC5-OUT)") (class "Default")
      (node (ref "C19") (pin "1") (pinfunction "1_1") (pintype "passive"))
      (node (ref "C20") (pin "+") (pinfunction "+_+") (pintype "passive"))
      (node (ref "IC5") (pin "5") (pinfunction "OUT_5") (pintype "output"))
      (node (ref "R126") (pin "2") (pinfunction "2_2") (pintype "passive"))
    )
    (net (code "150") (name "Net-(IC6-HTH)") (class "Default")
      (node (ref "IC6") (pin "1") (pinfunction "HTH_1") (pintype "input"))
      (node (ref "R46") (pin "2") (pinfunction "2_2") (pintype "passive"))
      (node (ref "R47") (pin "1") (pinfunction "1_1") (pintype "passive"))
    )
    (net (code "151") (name "Net-(IC6-LTH)") (class "Default")
      (node (ref "IC6") (pin "3") (pinfunction "LTH_3") (pintype "input"))
      (node (ref "R33") (pin "1") (pinfunction "1_1") (pintype "passive"))
      (node (ref "R47") (pin "2") (pinfunction "2_2") (pintype "passive"))
    )
    (net (code "152") (name "Net-(IC6-VDD)") (class "Default")
      (node (ref "C35") (pin "1") (pinfunction "1_1") (pintype "passive"))
      (node (ref "IC6") (pin "5") (pinfunction "VDD_5") (pintype "input"))
      (node (ref "R28") (pin "1") (pinfunction "1_1") (pintype "passive"))
    )
    (net (code "153") (name "Net-(IC8-BOOST)") (class "Default")
      (node (ref "C25") (pin "2") (pinfunction "2_2") (pintype "passive"))
      (node (ref "IC8") (pin "2") (pinfunction "BOOST_2") (pintype "bidirectional"))
    )
    (net (code "154") (name "Net-(IC8-EN)") (class "Default")
      (node (ref "IC8") (pin "5") (pinfunction "EN_5") (pintype "bidirectional"))
      (node (ref "JP1") (pin "2") (pinfunction "2_2") (pintype "bidirectional"))
      (node (ref "R22") (pin "2") (pinfunction "2_2") (pintype "passive"))
    )
    (net (code "155") (name "Net-(IC8-FB)") (class "Default")
      (node (ref "C26") (pin "2") (pinfunction "2_2") (pintype "passive"))
      (node (ref "IC8") (pin "6") (pinfunction "FB_6") (pintype "bidirectional"))
      (node (ref "R19") (pin "1") (pinfunction "1_1") (pintype "passive"))
      (node (ref "R20") (pin "2") (pinfunction "2_2") (pintype "passive"))
    )
    (net (code "156") (name "Net-(IC8-RT)") (class "Default")
      (node (ref "IC8") (pin "8") (pinfunction "RT_8") (pintype "bidirectional"))
      (node (ref "R17") (pin "1") (pinfunction "1_1") (pintype "passive"))
    )
    (net (code "157") (name "Net-(IC8-SS)") (class "Default")
      (node (ref "IC8") (pin "7") (pinfunction "SS_7") (pintype "bidirectional"))
      (node (ref "R77") (pin "1") (pinfunction "1_1") (pintype "passive"))
    )
    (net (code "158") (name "Net-(IC8-SW)") (class "Default")
      (node (ref "C25") (pin "1") (pinfunction "1_1") (pintype "passive"))
      (node (ref "D7") (pin "K") (pinfunction "K_K") (pintype "passive"))
      (node (ref "IC8") (pin "3") (pinfunction "SW_3") (pintype "bidirectional"))
      (node (ref "L9") (pin "1") (pinfunction "1_1") (pintype "passive"))
    )
    (net (code "159") (name "Net-(IC10-OUT)") (class "Default")
      (node (ref "IC10") (pin "3") (pinfunction "OUT_3") (pintype "output"))
      (node (ref "R102") (pin "1") (pinfunction "1_1") (pintype "passive"))
    )
    (net (code "160") (name "Net-(IC10-VIN+)") (class "Default")
      (node (ref "C29") (pin "1") (pinfunction "1_1") (pintype "passive"))
      (node (ref "F1") (pin "1") (pinfunction "1_1") (pintype "passive"))
      (node (ref "IC10") (pin "5") (pinfunction "VIN+_5") (pintype "input"))
      (node (ref "R39") (pin "2") (pinfunction "2_2") (pintype "passive"))
    )
    (net (code "161") (name "Net-(IC11-WP)") (class "Default")
      (node (ref "IC11") (pin "7") (pinfunction "WP_7") (pintype "input"))
      (node (ref "R18") (pin "2") (pinfunction "2_2") (pintype "passive"))
      (node (ref "TP1") (pin "P$1") (pinfunction "TP_P$1") (pintype "passive"))
    )
    (net (code "162") (name "Net-(IC13-VIN)") (class "Default")
      (node (ref "C58") (pin "1") (pinfunction "1_1") (pintype "passive"))
      (node (ref "C59") (pin "1") (pinfunction "1_1") (pintype "passive"))
      (node (ref "IC13") (pin "1") (pinfunction "VIN_1") (pintype "bidirectional"))
      (node (ref "R93") (pin "2") (pinfunction "2_2") (pintype "passive"))
    )
    (net (code "163") (name "Net-(IC16A-+IN)") (class "Default")
      (node (ref "C62") (pin "1") (pinfunction "1_1") (pintype "passive"))
      (node (ref "IC16") (pin "3") (pinfunction "+IN_3") (pintype "input"))
      (node (ref "R95") (pin "2") (pinfunction "2_2") (pintype "passive"))
      (node (ref "R96") (pin "1") (pinfunction "1_1") (pintype "passive"))
    )
    (net (code "164") (name "Net-(IC16A--IN)") (class "Default")
      (node (ref "IC16") (pin "1") (pinfunction "OUT_1") (pintype "output"))
      (node (ref "IC16") (pin "2") (pinfunction "-IN_2") (pintype "input"))
      (node (ref "R101") (pin "2") (pinfunction "2_2") (pintype "passive"))
    )
    (net (code "165") (name "Net-(IC16B-+IN)") (class "Default")
      (node (ref "C63") (pin "1") (pinfunction "1_1") (pintype "passive"))
      (node (ref "IC16") (pin "5") (pinfunction "+IN_5") (pintype "input"))
      (node (ref "R98") (pin "2") (pinfunction "2_2") (pintype "passive"))
      (node (ref "R99") (pin "1") (pinfunction "1_1") (pintype "passive"))
    )
    (net (code "166") (name "Net-(IC16B--IN)") (class "Default")
      (node (ref "IC16") (pin "6") (pinfunction "-IN_6") (pintype "input"))
      (node (ref "IC16") (pin "7") (pinfunction "OUT_7") (pintype "output"))
      (node (ref "R100") (pin "2") (pinfunction "2_2") (pintype "passive"))
    )
    (net (code "167") (name "Net-(IC16C-V+)") (class "Default")
      (node (ref "C67") (pin "1") (pinfunction "1_1") (pintype "passive"))
      (node (ref "IC16") (pin "8") (pinfunction "V+_8") (pintype "input"))
      (node (ref "R103") (pin "1") (pinfunction "1_1") (pintype "passive"))
    )
    (net (code "168") (name "Net-(J5-Pad4)") (class "Default")
      (node (ref "J5") (pin "4") (pinfunction "4_4") (pintype "bidirectional"))
      (node (ref "R62") (pin "1") (pinfunction "1_1") (pintype "passive"))
    )
    (net (code "169") (name "Net-(J6-Pad4)") (class "Default")
      (node (ref "J6") (pin "4") (pinfunction "4_4") (pintype "bidirectional"))
      (node (ref "R78") (pin "1") (pinfunction "1_1") (pintype "passive"))
    )
    (net (code "170") (name "Net-(J7-Pad2)") (class "Default")
      (node (ref "J7") (pin "2") (pinfunction "2_2") (pintype "passive"))
      (node (ref "R68") (pin "1") (pinfunction "1_1") (pintype "passive"))
    )
    (net (code "171") (name "Net-(J8-Pad2)") (class "Default")
      (node (ref "J8") (pin "2") (pinfunction "2_2") (pintype "passive"))
      (node (ref "R84") (pin "1") (pinfunction "1_1") (pintype "passive"))
    )
    (net (code "172") (name "Net-(J9-Pad2)") (class "Default")
      (node (ref "J9") (pin "2") (pinfunction "2_2") (pintype "passive"))
      (node (ref "R110") (pin "1") (pinfunction "1_1") (pintype "passive"))
      (node (ref "R114") (pin "1") (pinfunction "1_1") (pintype "passive"))
    )
    (net (code "173") (name "Net-(J10-Pad2)") (class "Default")
      (node (ref "J10") (pin "2") (pinfunction "2_2") (pintype "passive"))
      (node (ref "R116") (pin "1") (pinfunction "1_1") (pintype "passive"))
      (node (ref "R122") (pin "1") (pinfunction "1_1") (pintype "passive"))
    )
    (net (code "174") (name "Net-(J12-+5V)") (class "Default")
      (node (ref "C85") (pin "1") (pinfunction "1_1") (pintype "passive"))
      (node (ref "D6") (pin "A") (pinfunction "A_A") (pintype "passive"))
      (node (ref "IC15") (pin "4") (pinfunction "4_4") (pintype "input"))
      (node (ref "J12") (pin "1_+5V") (pinfunction "+5V_1_+5V") (pintype "bidirectional"))
      (node (ref "R128") (pin "1") (pinfunction "1_1") (pintype "passive"))
    )
    (net (code "175") (name "Net-(JP1-Pad1)") (class "Default")
      (node (ref "JP1") (pin "1") (pinfunction "1_1") (pintype "bidirectional"))
      (node (ref "R21") (pin "1") (pinfunction "1_1") (pintype "passive"))
    )
    (net (code "176") (name "Net-(L7-Pad1)") (class "Default")
      (node (ref "L7") (pin "1") (pinfunction "1_1") (pintype "passive"))
      (node (ref "R108") (pin "1") (pinfunction "1_1") (pintype "passive"))
    )
    (net (code "177") (name "Net-(L8-Pad1)") (class "Default")
      (node (ref "L8") (pin "1") (pinfunction "1_1") (pintype "passive"))
      (node (ref "R109") (pin "1") (pinfunction "1_1") (pintype "passive"))
    )
    (net (code "178") (name "Net-(L13-Pad2)") (class "Default")
      (node (ref "L13") (pin "2") (pinfunction "2_2") (pintype "passive"))
      (node (ref "R92") (pin "1") (pinfunction "1_1") (pintype "passive"))
    )
    (net (code "179") (name "Net-(Q1A-G)") (class "Default")
      (node (ref "C21") (pin "2") (pinfunction "2_2") (pintype "passive"))
      (node (ref "Q1") (pin "2") (pinfunction "G_2") (pintype "passive"))
      (node (ref "R10") (pin "2") (pinfunction "2_2") (pintype "passive"))
      (node (ref "R9") (pin "1") (pinfunction "1_1") (pintype "passive"))
    )
    (net (code "180") (name "Net-(Q1A-S)") (class "Default")
      (node (ref "Q1") (pin "1") (pinfunction "S_1") (pintype "passive"))
      (node (ref "R8") (pin "1") (pinfunction "1_1") (pintype "passive"))
    )
    (net (code "181") (name "Net-(Q1B-G)") (class "Default")
      (node (ref "C70") (pin "2") (pinfunction "2_2") (pintype "passive"))
      (node (ref "Q1") (pin "5") (pinfunction "G_5") (pintype "passive"))
      (node (ref "R75") (pin "1") (pinfunction "1_1") (pintype "passive"))
      (node (ref "R82") (pin "2") (pinfunction "2_2") (pintype "passive"))
    )
    (net (code "182") (name "Net-(Q1B-S)") (class "Default")
      (node (ref "Q1") (pin "4") (pinfunction "S_4") (pintype "passive"))
      (node (ref "R106") (pin "1") (pinfunction "1_1") (pintype "passive"))
    )
    (net (code "183") (name "Net-(Q2A-G)") (class "Default")
      (node (ref "C68") (pin "2") (pinfunction "2_2") (pintype "passive"))
      (node (ref "Q2") (pin "2") (pinfunction "G_2") (pintype "passive"))
      (node (ref "R107") (pin "1") (pinfunction "1_1") (pintype "passive"))
      (node (ref "R87") (pin "2") (pinfunction "2_2") (pintype "passive"))
    )
    (net (code "184") (name "Net-(Q2A-S)") (class "Default")
      (node (ref "Q2") (pin "1") (pinfunction "S_1") (pintype "passive"))
      (node (ref "R104") (pin "1") (pinfunction "1_1") (pintype "passive"))
    )
    (net (code "185") (name "Net-(Q2B-G)") (class "Default")
      (node (ref "C69") (pin "2") (pinfunction "2_2") (pintype "passive"))
      (node (ref "Q2") (pin "5") (pinfunction "G_5") (pintype "passive"))
      (node (ref "R24") (pin "1") (pinfunction "1_1") (pintype "passive"))
      (node (ref "R65") (pin "2") (pinfunction "2_2") (pintype "passive"))
    )
    (net (code "186") (name "Net-(Q2B-S)") (class "Default")
      (node (ref "Q2") (pin "4") (pinfunction "S_4") (pintype "passive"))
      (node (ref "R105") (pin "1") (pinfunction "1_1") (pintype "passive"))
    )
    (net (code "187") (name "Net-(Q3A-D)") (class "Default")
      (node (ref "Q3") (pin "6") (pinfunction "D_6") (pintype "passive"))
      (node (ref "R111") (pin "2") (pinfunction "2_2") (pintype "passive"))
      (node (ref "R115") (pin "2") (pinfunction "2_2") (pintype "passive"))
    )
    (net (code "188") (name "Net-(Q3A-G)") (class "Default")
      (node (ref "Q3") (pin "2") (pinfunction "G_2") (pintype "passive"))
      (node (ref "R112") (pin "1") (pinfunction "1_1") (pintype "passive"))
      (node (ref "R113") (pin "1") (pinfunction "1_1") (pintype "passive"))
    )
    (net (code "189") (name "Net-(Q4A-D)") (class "Default")
      (node (ref "C33") (pin "2") (pinfunction "2_2") (pintype "passive"))
      (node (ref "Q4") (pin "6") (pinfunction "D_6") (pintype "passive"))
      (node (ref "Q5") (pin "1") (pinfunction "G_1") (pintype "passive"))
      (node (ref "R42") (pin "2") (pinfunction "2_2") (pintype "passive"))
    )
    (net (code "190") (name "Net-(Q4A-S)") (class "Default")
      (node (ref "Q4") (pin "1") (pinfunction "S_1") (pintype "passive"))
      (node (ref "R40") (pin "2") (pinfunction "2_2") (pintype "passive"))
    )
    (net (code "191") (name "Net-(Q4B-D)") (class "Default")
      (node (ref "C34") (pin "2") (pinfunction "2_2") (pintype "passive"))
      (node (ref "Q4") (pin "3") (pinfunction "D_3") (pintype "passive"))
      (node (ref "Q5") (pin "3") (pinfunction "G_3") (pintype "passive"))
      (node (ref "R45") (pin "2") (pinfunction "2_2") (pintype "passive"))
    )
    (net (code "192") (name "Net-(Q4B-S)") (class "Default")
      (node (ref "Q4") (pin "4") (pinfunction "S_4") (pintype "passive"))
      (node (ref "R43") (pin "2") (pinfunction "2_2") (pintype "passive"))
    )
    (net (code "193") (name "Net-(Q5A-D)") (class "Default")
      (node (ref "F1") (pin "2") (pinfunction "2_2") (pintype "passive"))
      (node (ref "Q5") (pin "6") (pinfunction "D_6") (pintype "passive"))
      (node (ref "R35") (pin "1") (pinfunction "1_1") (pintype "passive"))
      (node (ref "R37") (pin "1") (pinfunction "1_1") (pintype "passive"))
      (node (ref "R97") (pin "1") (pinfunction "1_1") (pintype "passive"))
    )
    (net (code "194") (name "Net-(Q6A-G)") (class "Default")
      (node (ref "C42") (pin "2") (pinfunction "2_2") (pintype "passive"))
      (node (ref "Q6") (pin "1") (pinfunction "G_1") (pintype "passive"))
      (node (ref "Q7") (pin "6") (pinfunction "D_6") (pintype "passive"))
      (node (ref "R50") (pin "2") (pinfunction "2_2") (pintype "passive"))
    )
    (net (code "195") (name "Net-(Q6B-G)") (class "Default")
      (node (ref "C43") (pin "2") (pinfunction "2_2") (pintype "passive"))
      (node (ref "Q6") (pin "3") (pinfunction "G_3") (pintype "passive"))
      (node (ref "Q7") (pin "3") (pinfunction "D_3") (pintype "passive"))
      (node (ref "R55") (pin "2") (pinfunction "2_2") (pintype "passive"))
    )
    (net (code "196") (name "Net-(Q7A-S)") (class "Default")
      (node (ref "Q7") (pin "1") (pinfunction "S_1") (pintype "passive"))
      (node (ref "R51") (pin "2") (pinfunction "2_2") (pintype "passive"))
    )
    (net (code "197") (name "Net-(Q7B-S)") (class "Default")
      (node (ref "Q7") (pin "4") (pinfunction "S_4") (pintype "passive"))
      (node (ref "R53") (pin "1") (pinfunction "1_1") (pintype "passive"))
    )
    (net (code "198") (name "Net-(Q8A-G)") (class "Default")
      (node (ref "C44") (pin "2") (pinfunction "2_2") (pintype "passive"))
      (node (ref "Q8") (pin "1") (pinfunction "G_1") (pintype "passive"))
      (node (ref "Q9") (pin "6") (pinfunction "D_6") (pintype "passive"))
      (node (ref "R56") (pin "2") (pinfunction "2_2") (pintype "passive"))
    )
    (net (code "199") (name "Net-(Q8B-G)") (class "Default")
      (node (ref "C45") (pin "2") (pinfunction "2_2") (pintype "passive"))
      (node (ref "Q8") (pin "3") (pinfunction "G_3") (pintype "passive"))
      (node (ref "Q9") (pin "3") (pinfunction "D_3") (pintype "passive"))
      (node (ref "R61") (pin "2") (pinfunction "2_2") (pintype "passive"))
    )
    (net (code "200") (name "Net-(Q9A-S)") (class "Default")
      (node (ref "Q9") (pin "1") (pinfunction "S_1") (pintype "passive"))
      (node (ref "R57") (pin "2") (pinfunction "2_2") (pintype "passive"))
    )
    (net (code "201") (name "Net-(Q9B-S)") (class "Default")
      (node (ref "Q9") (pin "4") (pinfunction "S_4") (pintype "passive"))
      (node (ref "R59") (pin "1") (pinfunction "1_1") (pintype "passive"))
    )
    (net (code "202") (name "Net-(Q10A-D)") (class "Default")
      (node (ref "Q10") (pin "6") (pinfunction "D_6") (pintype "passive"))
      (node (ref "R79") (pin "2") (pinfunction "2_2") (pintype "passive"))
    )
    (net (code "203") (name "Net-(Q10A-S)") (class "Default")
      (node (ref "Q10") (pin "1") (pinfunction "S_1") (pintype "passive"))
      (node (ref "Q10") (pin "5") (pinfunction "G_5") (pintype "passive"))
      (node (ref "R80") (pin "1") (pinfunction "1_1") (pintype "passive"))
    )
    (net (code "204") (name "Net-(Q11A-D)") (class "Default")
      (node (ref "Q11") (pin "6") (pinfunction "D_6") (pintype "passive"))
      (node (ref "R63") (pin "2") (pinfunction "2_2") (pintype "passive"))
    )
    (net (code "205") (name "Net-(Q11A-S)") (class "Default")
      (node (ref "Q11") (pin "1") (pinfunction "S_1") (pintype "passive"))
      (node (ref "Q11") (pin "5") (pinfunction "G_5") (pintype "passive"))
      (node (ref "R64") (pin "1") (pinfunction "1_1") (pintype "passive"))
    )
    (net (code "206") (name "Net-(Q12A-D)") (class "Default")
      (node (ref "Q12") (pin "6") (pinfunction "D_6") (pintype "passive"))
      (node (ref "R85") (pin "2") (pinfunction "2_2") (pintype "passive"))
    )
    (net (code "207") (name "Net-(Q12A-S)") (class "Default")
      (node (ref "Q12") (pin "1") (pinfunction "S_1") (pintype "passive"))
      (node (ref "Q12") (pin "5") (pinfunction "G_5") (pintype "passive"))
      (node (ref "R86") (pin "1") (pinfunction "1_1") (pintype "passive"))
    )
    (net (code "208") (name "Net-(Q13A-D)") (class "Default")
      (node (ref "Q13") (pin "6") (pinfunction "D_6") (pintype "passive"))
      (node (ref "R69") (pin "2") (pinfunction "2_2") (pintype "passive"))
    )
    (net (code "209") (name "Net-(Q13A-S)") (class "Default")
      (node (ref "Q13") (pin "1") (pinfunction "S_1") (pintype "passive"))
      (node (ref "Q13") (pin "5") (pinfunction "G_5") (pintype "passive"))
      (node (ref "R70") (pin "1") (pinfunction "1_1") (pintype "passive"))
    )
    (net (code "210") (name "Net-(Q14A-D)") (class "Default")
      (node (ref "Q14") (pin "6") (pinfunction "D_6") (pintype "passive"))
      (node (ref "R117") (pin "2") (pinfunction "2_2") (pintype "passive"))
      (node (ref "R123") (pin "2") (pinfunction "2_2") (pintype "passive"))
    )
    (net (code "211") (name "Net-(Q14A-G)") (class "Default")
      (node (ref "Q14") (pin "2") (pinfunction "G_2") (pintype "passive"))
      (node (ref "R118") (pin "1") (pinfunction "1_1") (pintype "passive"))
      (node (ref "R119") (pin "1") (pinfunction "1_1") (pintype "passive"))
    )
    (net (code "212") (name "Net-(R23-Pad1)") (class "Default")
      (node (ref "R23") (pin "1") (pinfunction "1_1") (pintype "passive"))
      (node (ref "R49") (pin "2") (pinfunction "2_2") (pintype "passive"))
    )
    (net (code "213") (name "Net-(R35-Pad2)") (class "Default")
      (node (ref "R35") (pin "2") (pinfunction "2_2") (pintype "passive"))
      (node (ref "R36") (pin "1") (pinfunction "1_1") (pintype "passive"))
      (node (ref "R37") (pin "2") (pinfunction "2_2") (pintype "passive"))
      (node (ref "R38") (pin "1") (pinfunction "1_1") (pintype "passive"))
    )
    (net (code "214") (name "Net-(R94-Pad2)") (class "Default")
      (node (ref "R94") (pin "2") (pinfunction "2_2") (pintype "passive"))
      (node (ref "R95") (pin "1") (pinfunction "1_1") (pintype "passive"))
    )
    (net (code "215") (name "Net-(R97-Pad2)") (class "Default")
      (node (ref "R97") (pin "2") (pinfunction "2_2") (pintype "passive"))
      (node (ref "R98") (pin "1") (pinfunction "1_1") (pintype "passive"))
    )
    (net (code "216") (name "VBAT") (class "Default")
      (node (ref "C22") (pin "1") (pinfunction "1_1") (pintype "passive"))
      (node (ref "C23") (pin "1") (pinfunction "1_1") (pintype "passive"))
      (node (ref "C42") (pin "1") (pinfunction "1_1") (pintype "passive"))
      (node (ref "C43") (pin "1") (pinfunction "1_1") (pintype "passive"))
      (node (ref "C44") (pin "1") (pinfunction "1_1") (pintype "passive"))
      (node (ref "C45") (pin "1") (pinfunction "1_1") (pintype "passive"))
      (node (ref "C83") (pin "1") (pinfunction "1_1") (pintype "passive"))
      (node (ref "C84") (pin "1") (pinfunction "1_1") (pintype "passive"))
      (node (ref "IC10") (pin "4") (pinfunction "VIN-_4") (pintype "input"))
      (node (ref "IC8") (pin "4") (pinfunction "VIN_4") (pintype "bidirectional"))
      (node (ref "J5") (pin "5") (pinfunction "5_5") (pintype "bidirectional"))
      (node (ref "J6") (pin "5") (pinfunction "5_5") (pintype "bidirectional"))
      (node (ref "J7") (pin "1") (pinfunction "1_1") (pintype "passive"))
      (node (ref "J8") (pin "1") (pinfunction "1_1") (pintype "passive"))
      (node (ref "JP1") (pin "3") (pinfunction "3_3") (pintype "bidirectional"))
      (node (ref "Q6") (pin "2") (pinfunction "S_2") (pintype "passive"))
      (node (ref "Q6") (pin "5") (pinfunction "S_5") (pintype "passive"))
      (node (ref "Q8") (pin "2") (pinfunction "S_2") (pintype "passive"))
      (node (ref "Q8") (pin "5") (pinfunction "S_5") (pintype "passive"))
      (node (ref "R124") (pin "1") (pinfunction "1_1") (pintype "passive"))
      (node (ref "R125") (pin "1") (pinfunction "1_1") (pintype "passive"))
      (node (ref "R22") (pin "1") (pinfunction "1_1") (pintype "passive"))
      (node (ref "R33") (pin "2") (pinfunction "2_2") (pintype "passive"))
      (node (ref "R39") (pin "1") (pinfunction "1_1") (pintype "passive"))
      (node (ref "R50") (pin "1") (pinfunction "1_1") (pintype "passive"))
      (node (ref "R55") (pin "1") (pinfunction "1_1") (pintype "passive"))
      (node (ref "R56") (pin "1") (pinfunction "1_1") (pintype "passive"))
      (node (ref "R61") (pin "1") (pinfunction "1_1") (pintype "passive"))
    )
    (net (code "217") (name "unconnected-(IC2-D8-Pad30)") (class "Default")
      (node (ref "IC2") (pin "30") (pinfunction "D8_30") (pintype "tri_state"))
    )
    (net (code "218") (name "unconnected-(IC2-D9-Pad32)") (class "Default")
      (node (ref "IC2") (pin "32") (pinfunction "D9_32") (pintype "tri_state"))
    )
    (net (code "219") (name "unconnected-(IC2-D10-Pad34)") (class "Default")
      (node (ref "IC2") (pin "34") (pinfunction "D10_34") (pintype "tri_state"))
    )
    (net (code "220") (name "unconnected-(IC2-D11-Pad36)") (class "Default")
      (node (ref "IC2") (pin "36") (pinfunction "D11_36") (pintype "tri_state"))
    )
    (net (code "221") (name "unconnected-(IC2-D12-Pad39)") (class "Default")
      (node (ref "IC2") (pin "39") (pinfunction "D12_39") (pintype "tri_state"))
    )
    (net (code "222") (name "unconnected-(IC2-D13-Pad41)") (class "Default")
      (node (ref "IC2") (pin "41") (pinfunction "D13_41") (pintype "tri_state"))
    )
    (net (code "223") (name "unconnected-(IC2-D14-Pad43)") (class "Default")
      (node (ref "IC2") (pin "43") (pinfunction "D14_43") (pintype "tri_state"))
    )
    (net (code "224") (name "unconnected-(IC2-NC-Pad10)") (class "Default")
      (node (ref "IC2") (pin "10") (pinfunction "NC_10") (pintype "no_connect"))
    )
    (net (code "225") (name "unconnected-(IC2-NC1-Pad13)") (class "Default")
      (node (ref "IC2") (pin "13") (pinfunction "NC1_13") (pintype "no_connect"))
    )
    (net (code "226") (name "unconnected-(IC8-PG-Pad9)") (class "Default")
      (node (ref "IC8") (pin "9") (pinfunction "PG_9") (pintype "bidirectional"))
    )
    (net (code "227") (name "unconnected-(J1-Pad1)") (class "Default")
      (node (ref "J1") (pin "1") (pinfunction "1_1") (pintype "passive"))
    )
    (net (code "228") (name "unconnected-(J1-Pad23)") (class "Default")
      (node (ref "J1") (pin "23") (pinfunction "23_23") (pintype "passive"))
    )
    (net (code "229") (name "unconnected-(J1-Pad24)") (class "Default")
      (node (ref "J1") (pin "24") (pinfunction "24_24") (pintype "passive"))
    )
    (net (code "230") (name "unconnected-(J2-Pad1)") (class "Default")
      (node (ref "J2") (pin "1") (pinfunction "1_1") (pintype "passive"))
    )
    (net (code "231") (name "unconnected-(J2-Pad23)") (class "Default")
      (node (ref "J2") (pin "23") (pinfunction "23_23") (pintype "passive"))
    )
    (net (code "232") (name "unconnected-(J2-Pad24)") (class "Default")
      (node (ref "J2") (pin "24") (pinfunction "24_24") (pintype "passive"))
    )
    (net (code "233") (name "unconnected-(J5-Pad6)") (class "Default")
      (node (ref "J5") (pin "6") (pinfunction "6_6") (pintype "bidirectional"))
    )
    (net (code "234") (name "unconnected-(J6-Pad6)") (class "Default")
      (node (ref "J6") (pin "6") (pinfunction "6_6") (pintype "bidirectional"))
    )
    (net (code "235") (name "unconnected-(J14-Pad8)") (class "Default")
      (node (ref "J14") (pin "8") (pinfunction "8_8") (pintype "passive"))
    )
    (net (code "236") (name "unconnected-(Q3B-D-Pad3)") (class "Default")
      (node (ref "Q3") (pin "3") (pinfunction "D_3") (pintype "passive"))
    )
    (net (code "237") (name "unconnected-(Q3B-G-Pad5)") (class "Default")
      (node (ref "Q3") (pin "5") (pinfunction "G_5") (pintype "passive"))
    )
    (net (code "238") (name "unconnected-(Q3B-S-Pad4)") (class "Default")
      (node (ref "Q3") (pin "4") (pinfunction "S_4") (pintype "passive"))
    )
    (net (code "239") (name "unconnected-(Q14B-D-Pad3)") (class "Default")
      (node (ref "Q14") (pin "3") (pinfunction "D_3") (pintype "passive"))
    )
    (net (code "240") (name "unconnected-(Q14B-G-Pad5)") (class "Default")
      (node (ref "Q14") (pin "5") (pinfunction "G_5") (pintype "passive"))
    )
    (net (code "241") (name "unconnected-(Q14B-S-Pad4)") (class "Default")
      (node (ref "Q14") (pin "4") (pinfunction "S_4") (pintype "passive"))
    )
  )
)
